# PulseRain_M10.net
KiCad netlist of a schematic drawn in EAGLE
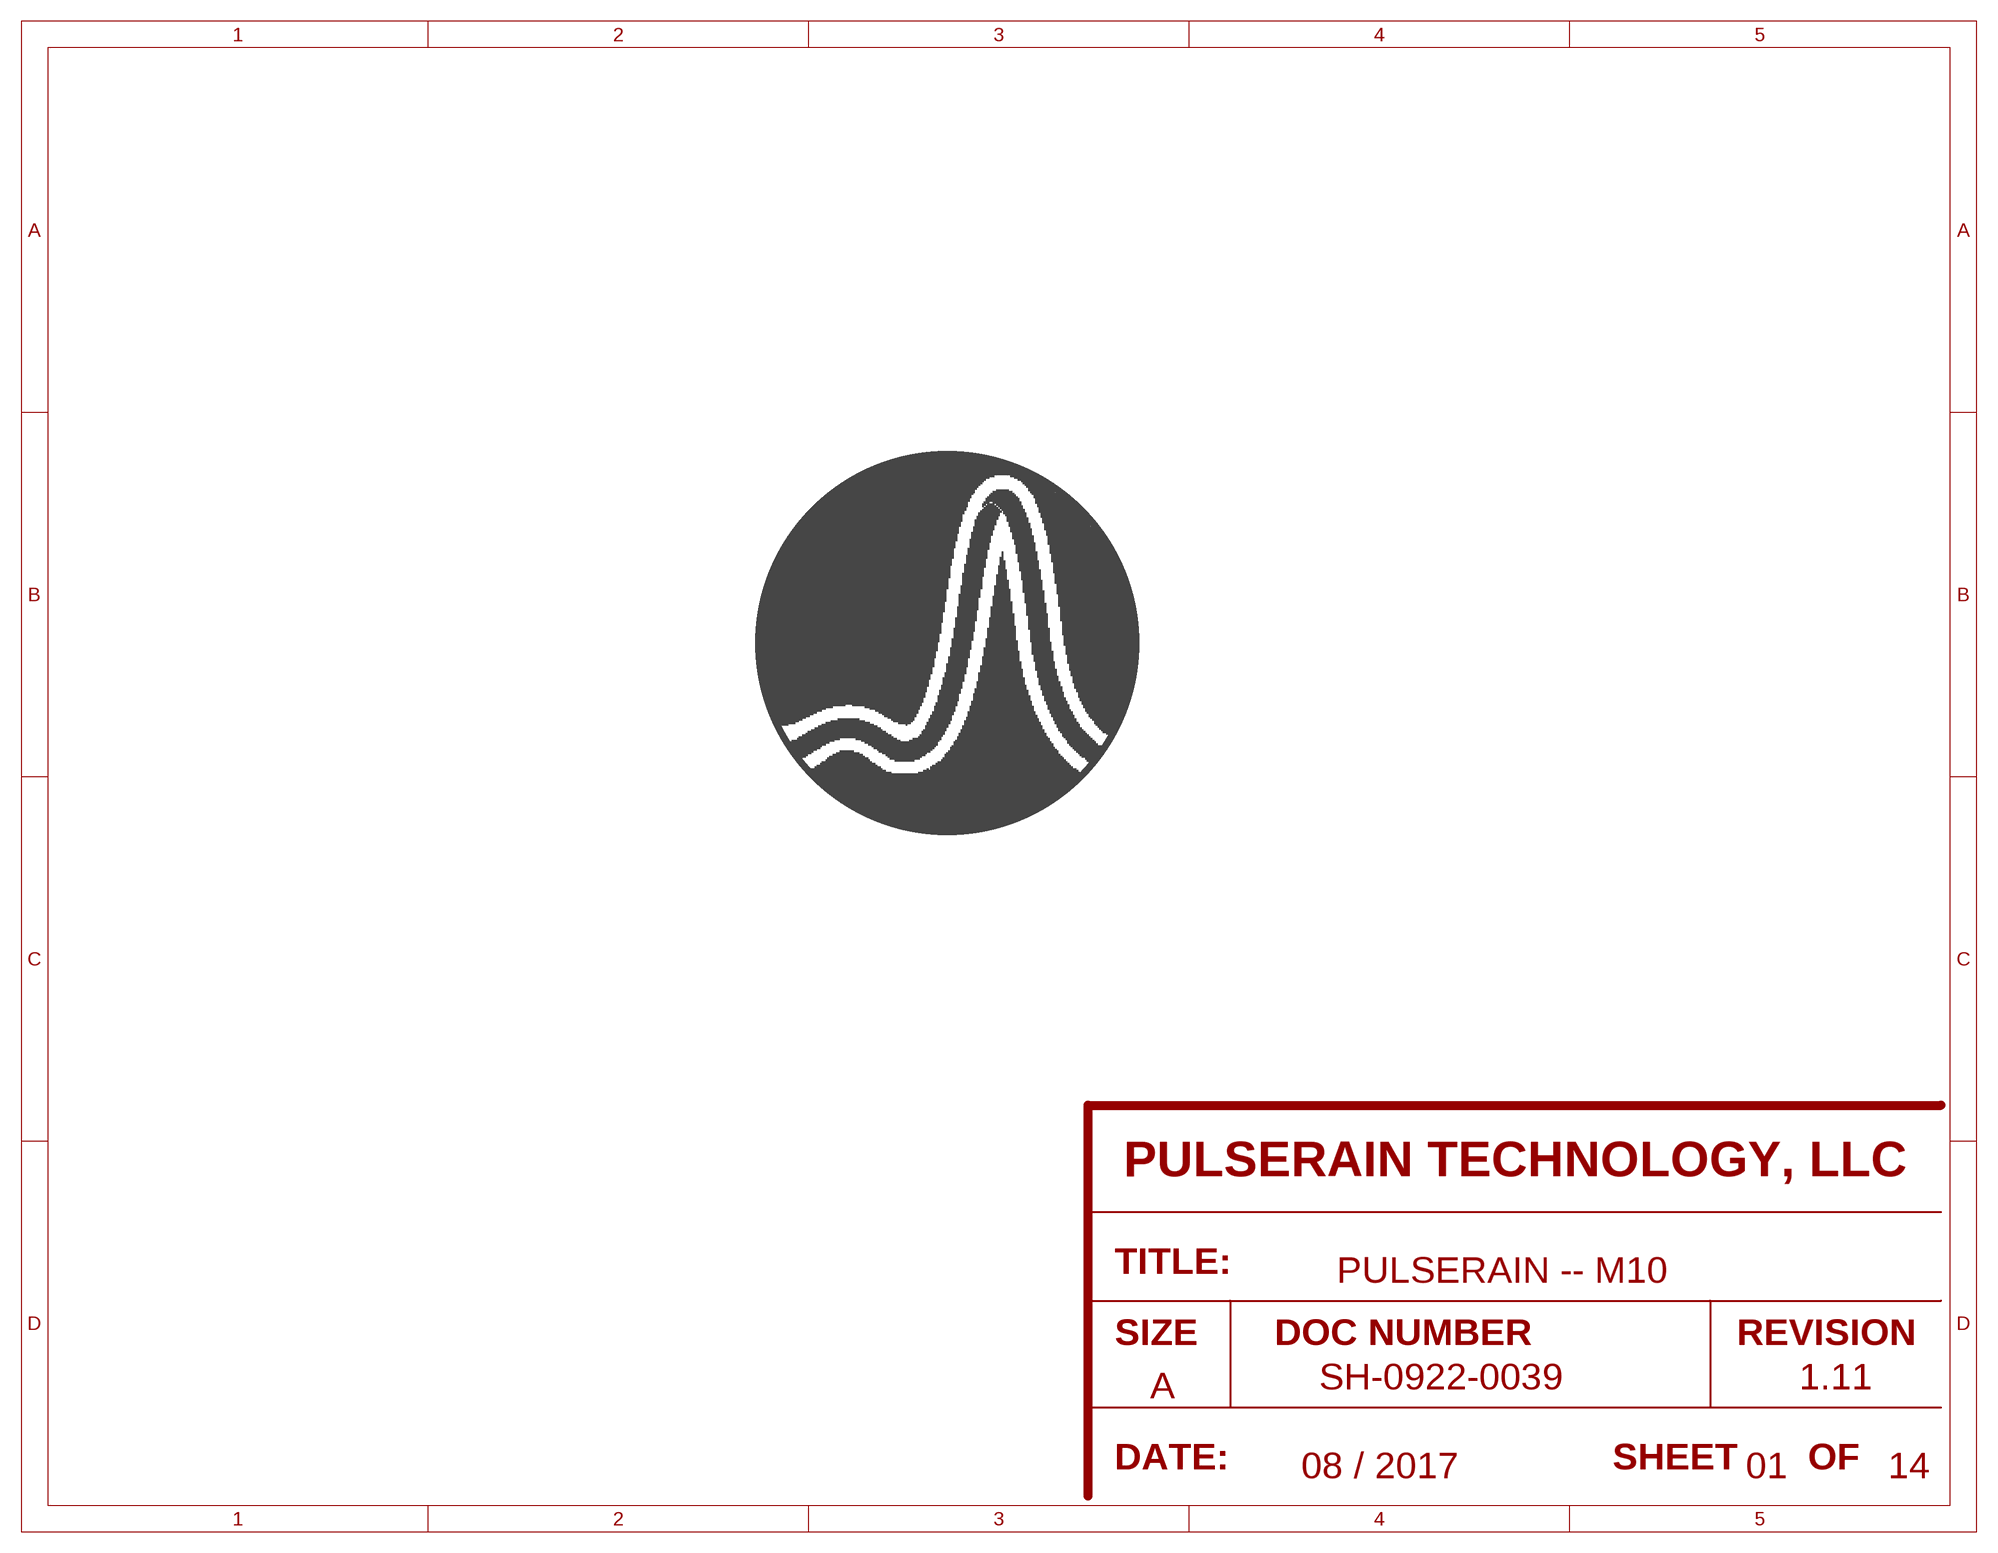
[diagram p0: schematic, sheet 1]
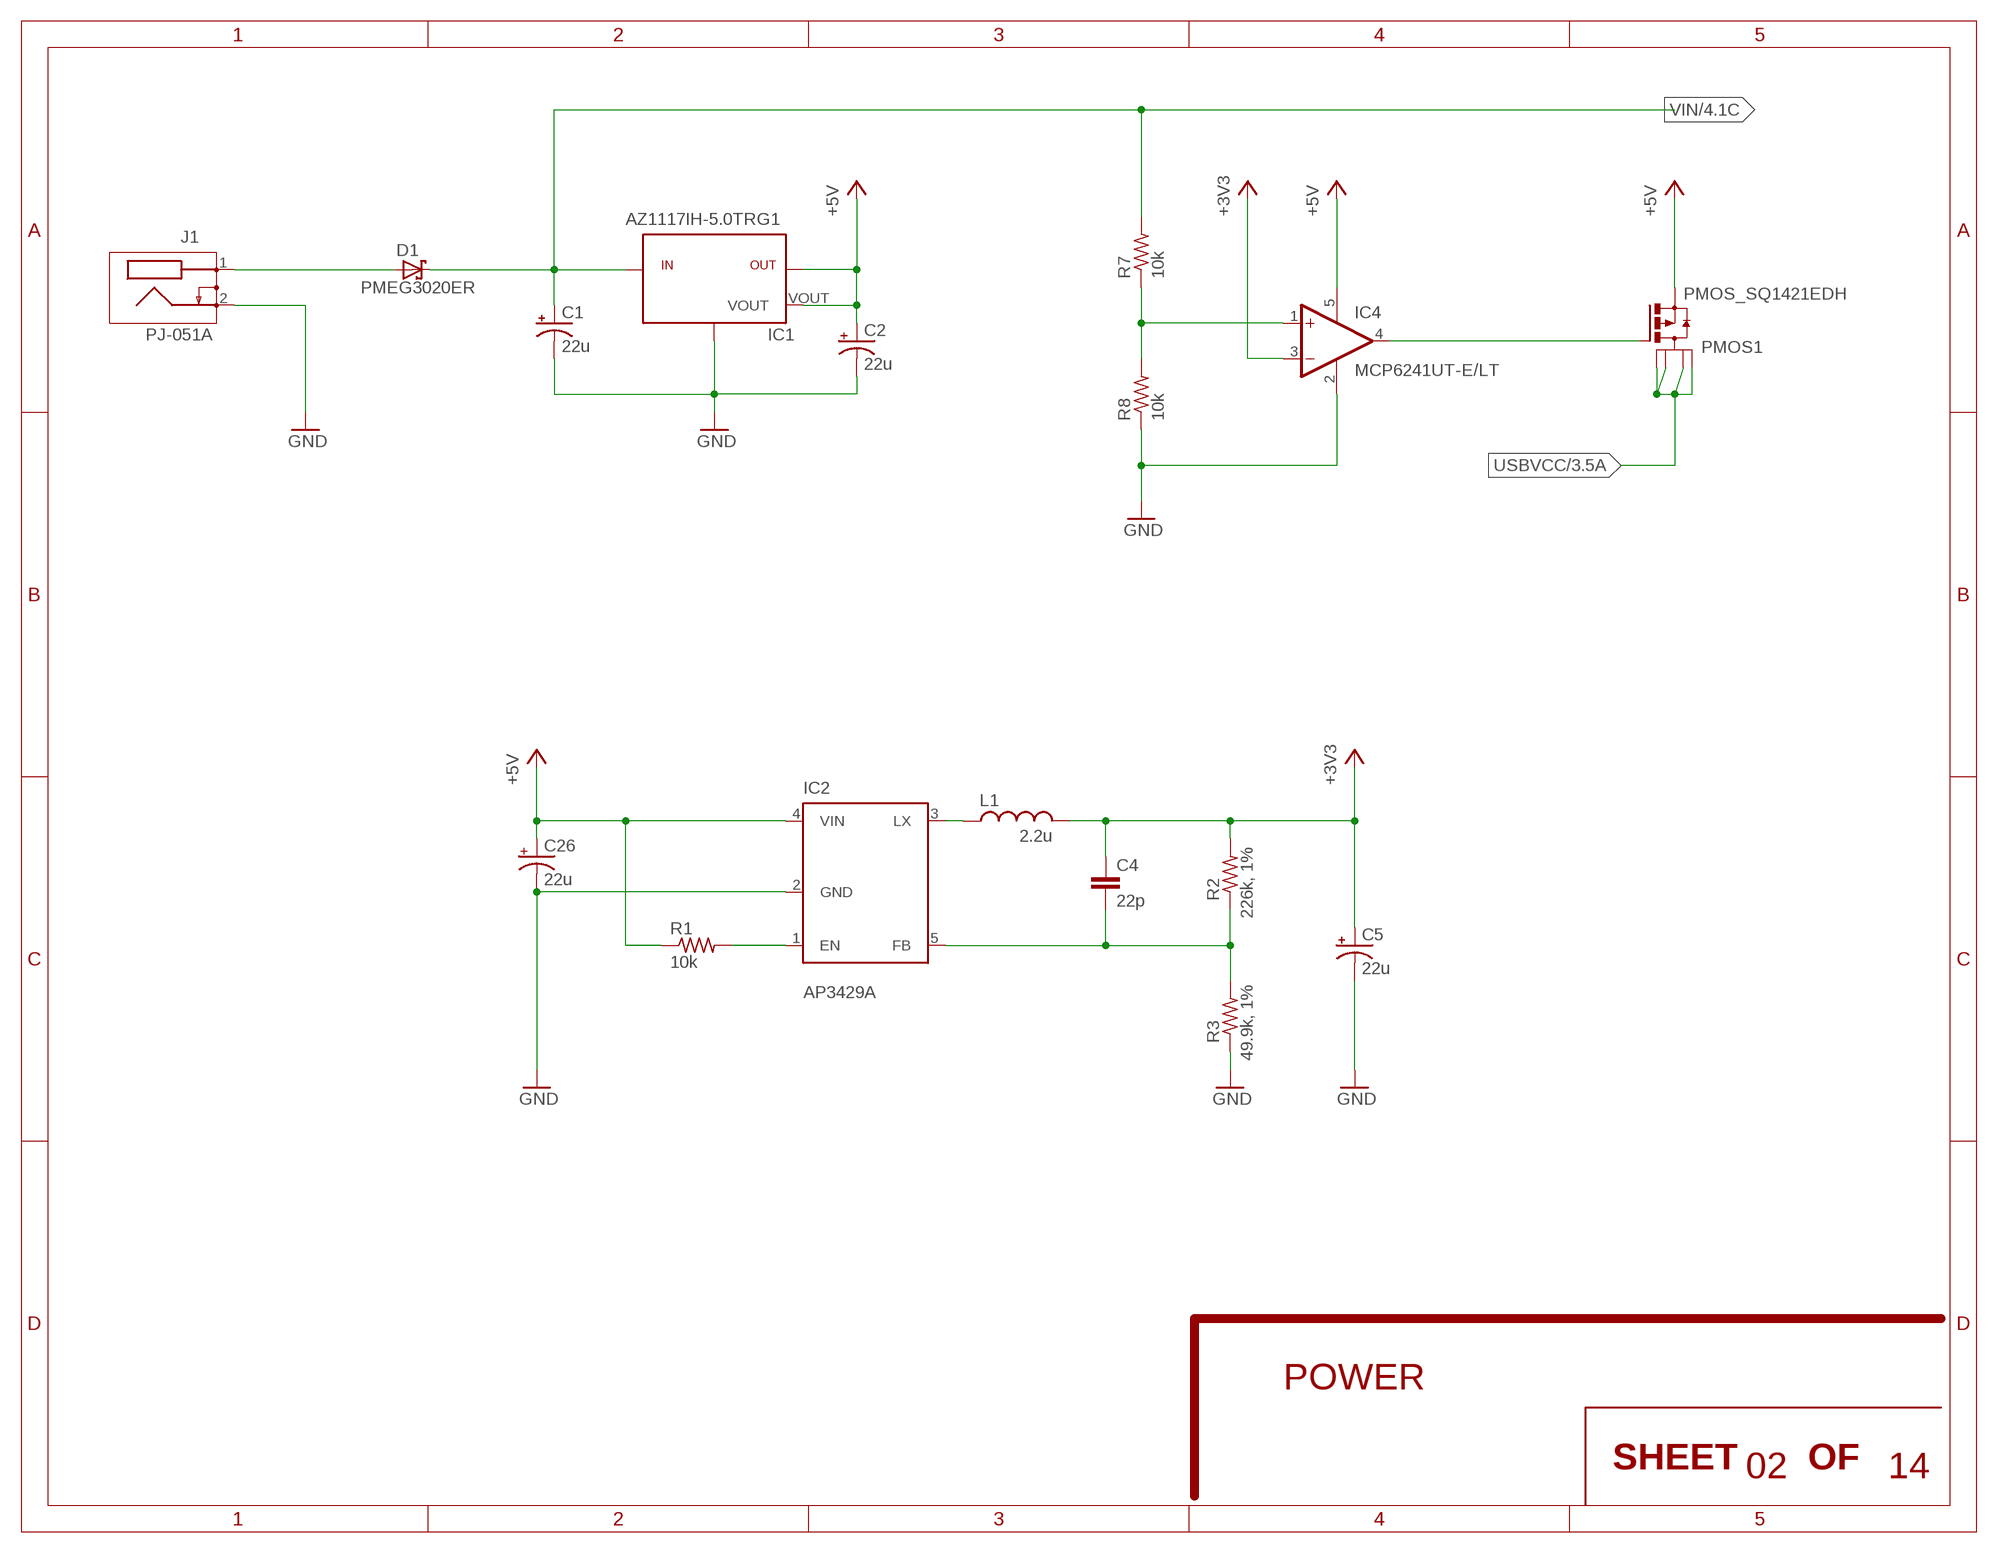
[diagram p1: schematic, sheet 2]
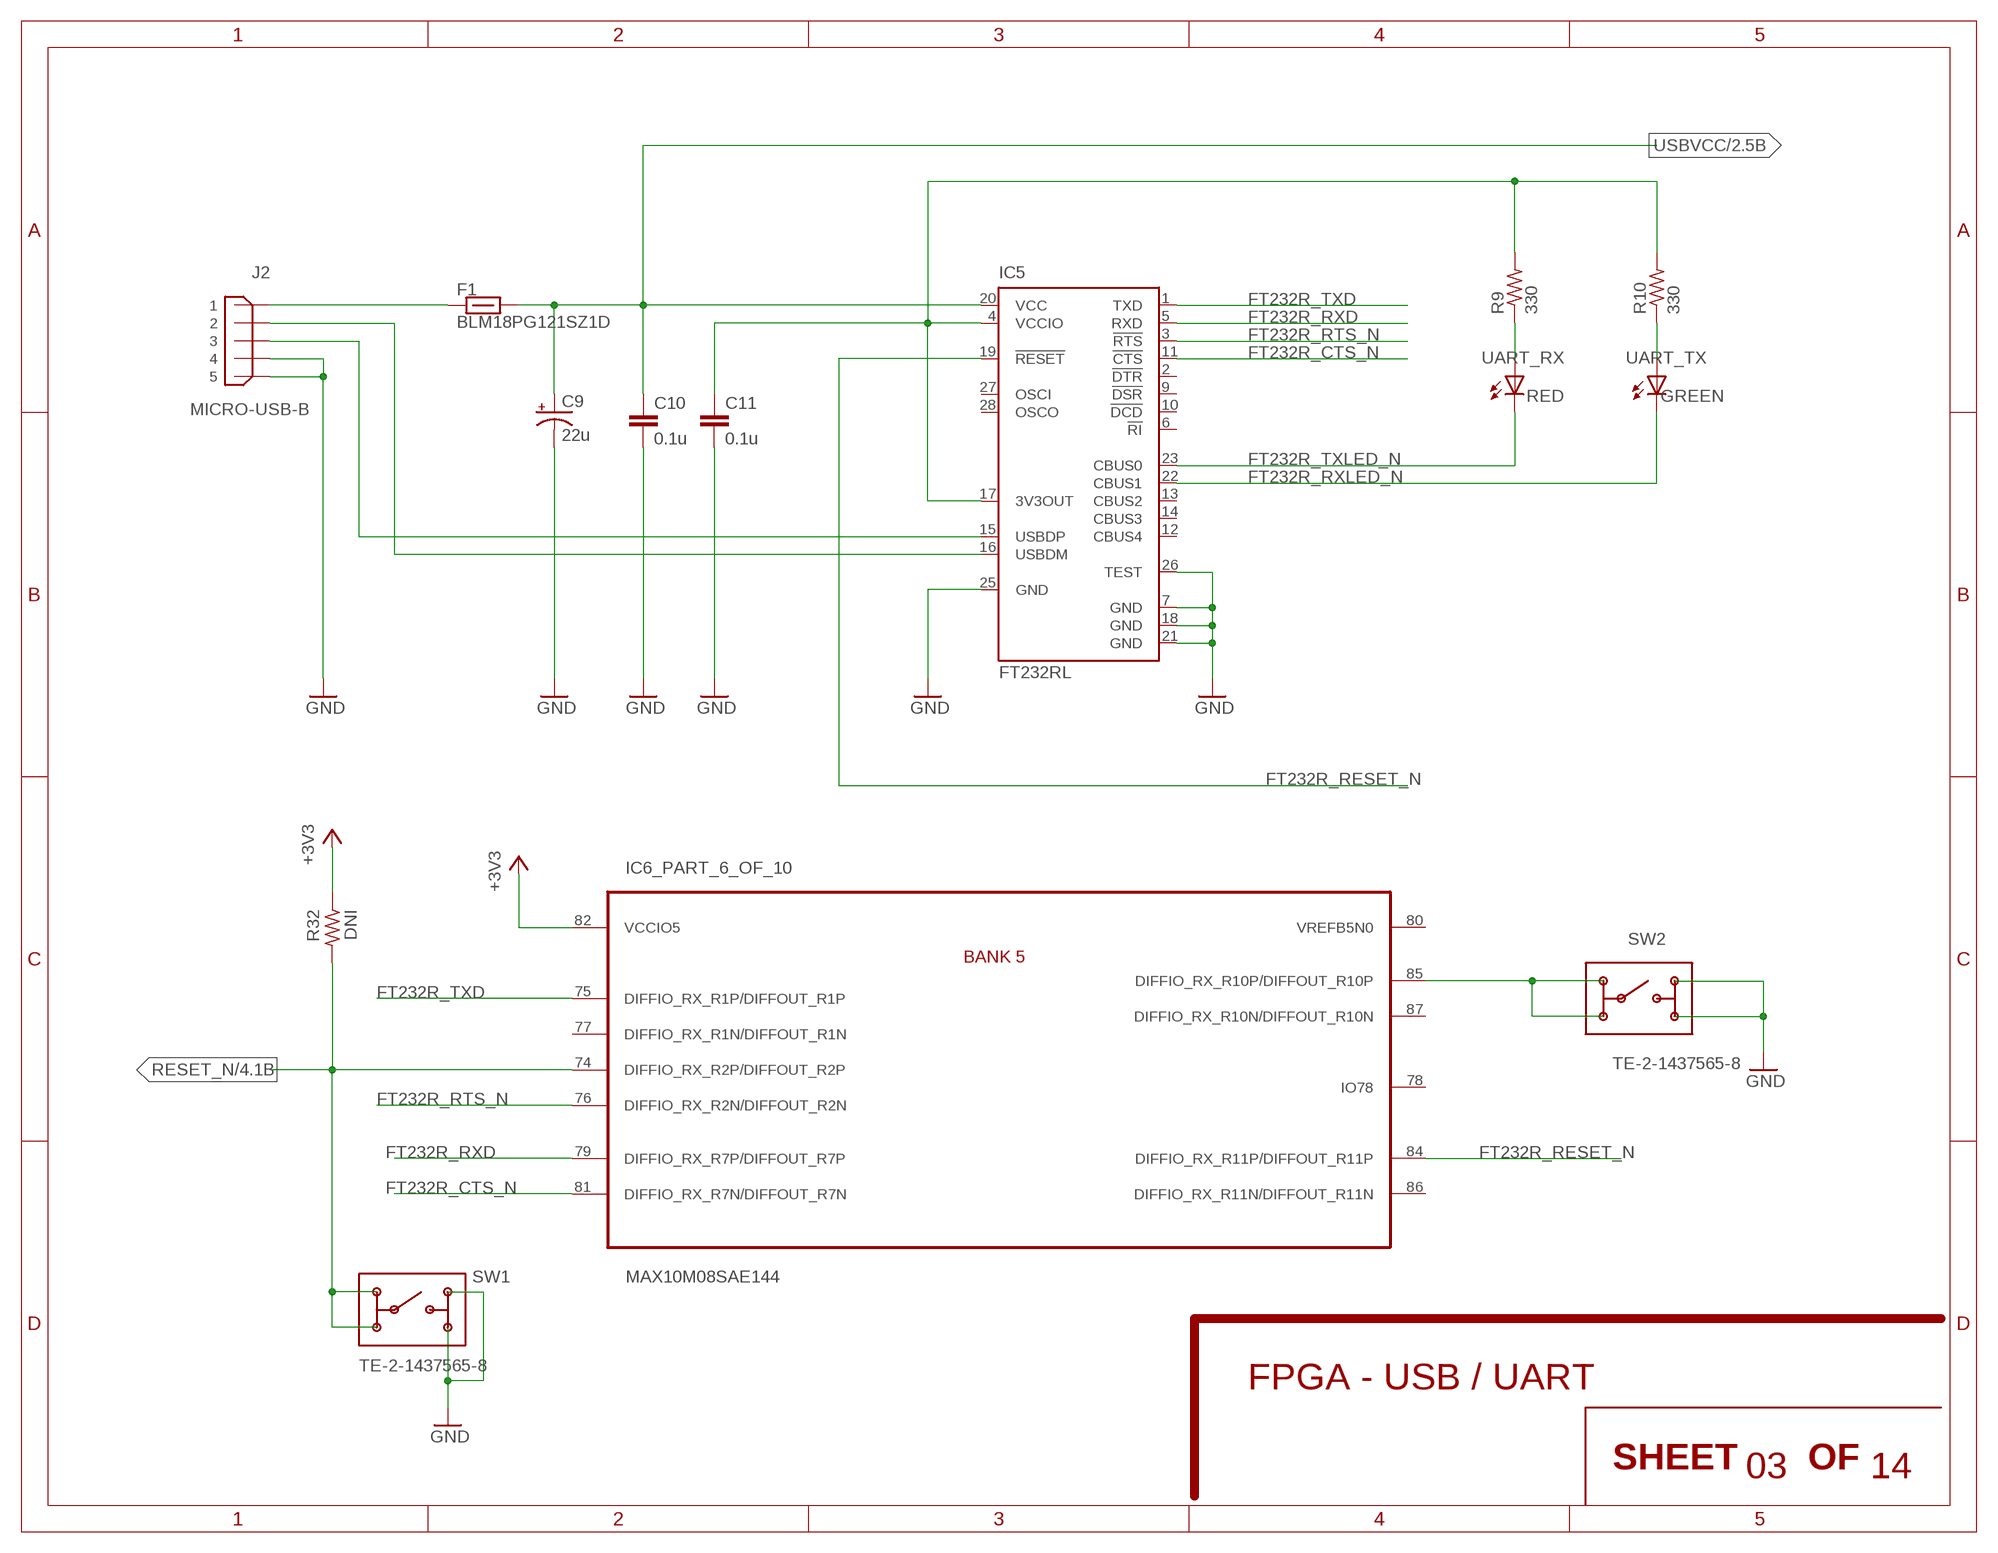
[diagram p2: schematic, sheet 3]
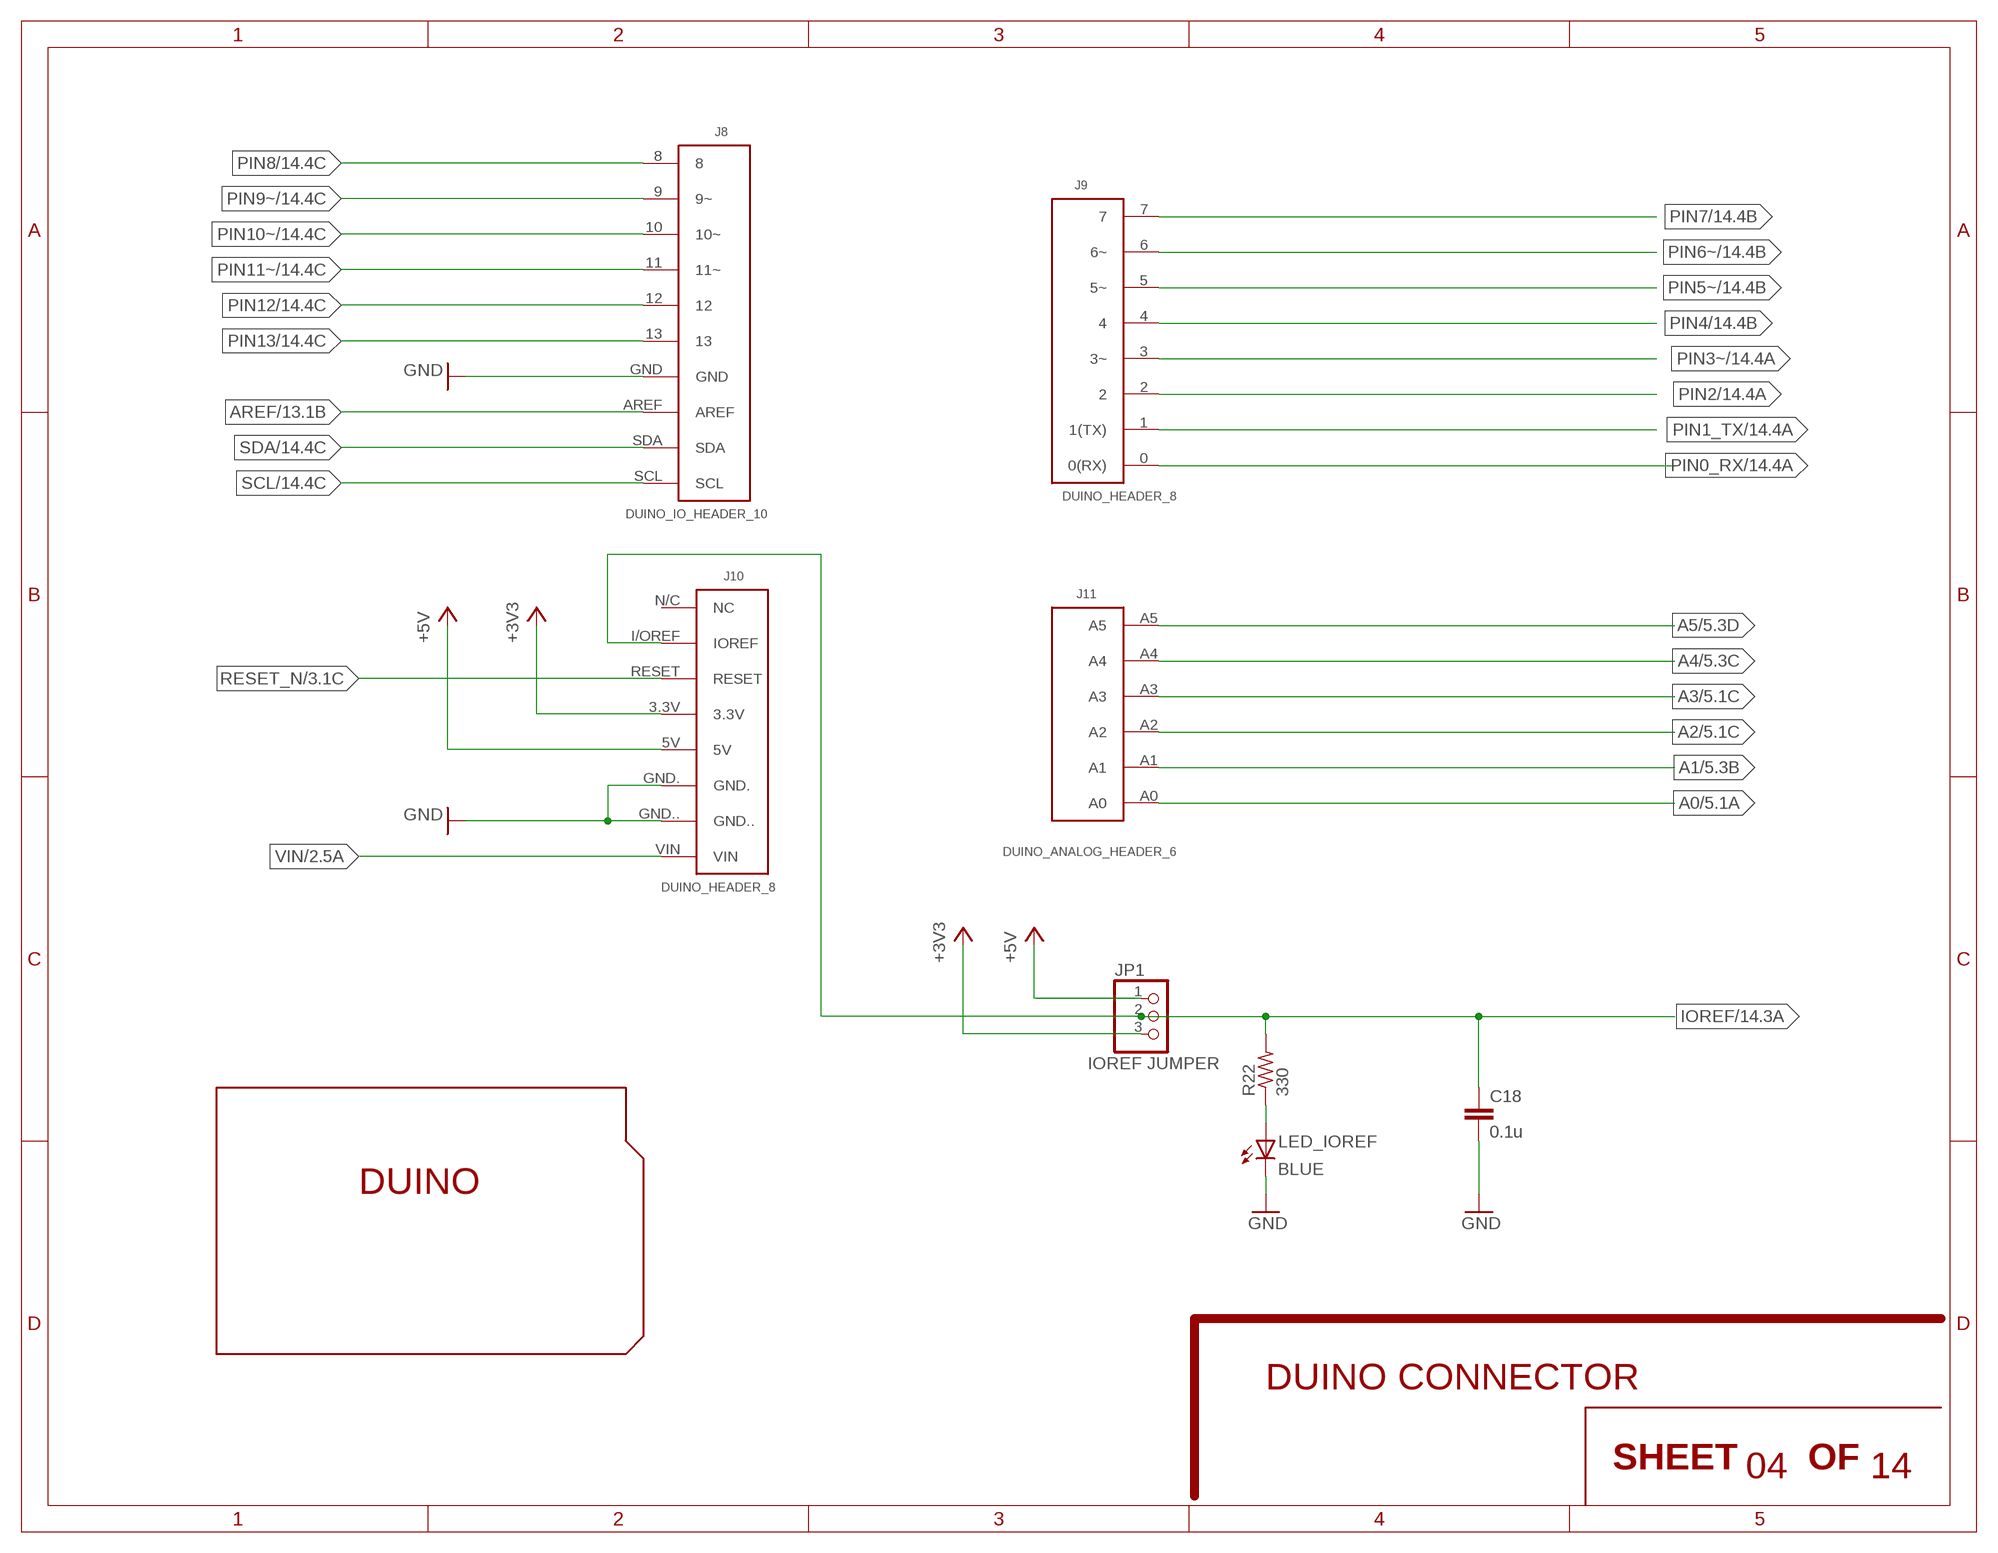
[diagram p3: schematic, sheet 4]
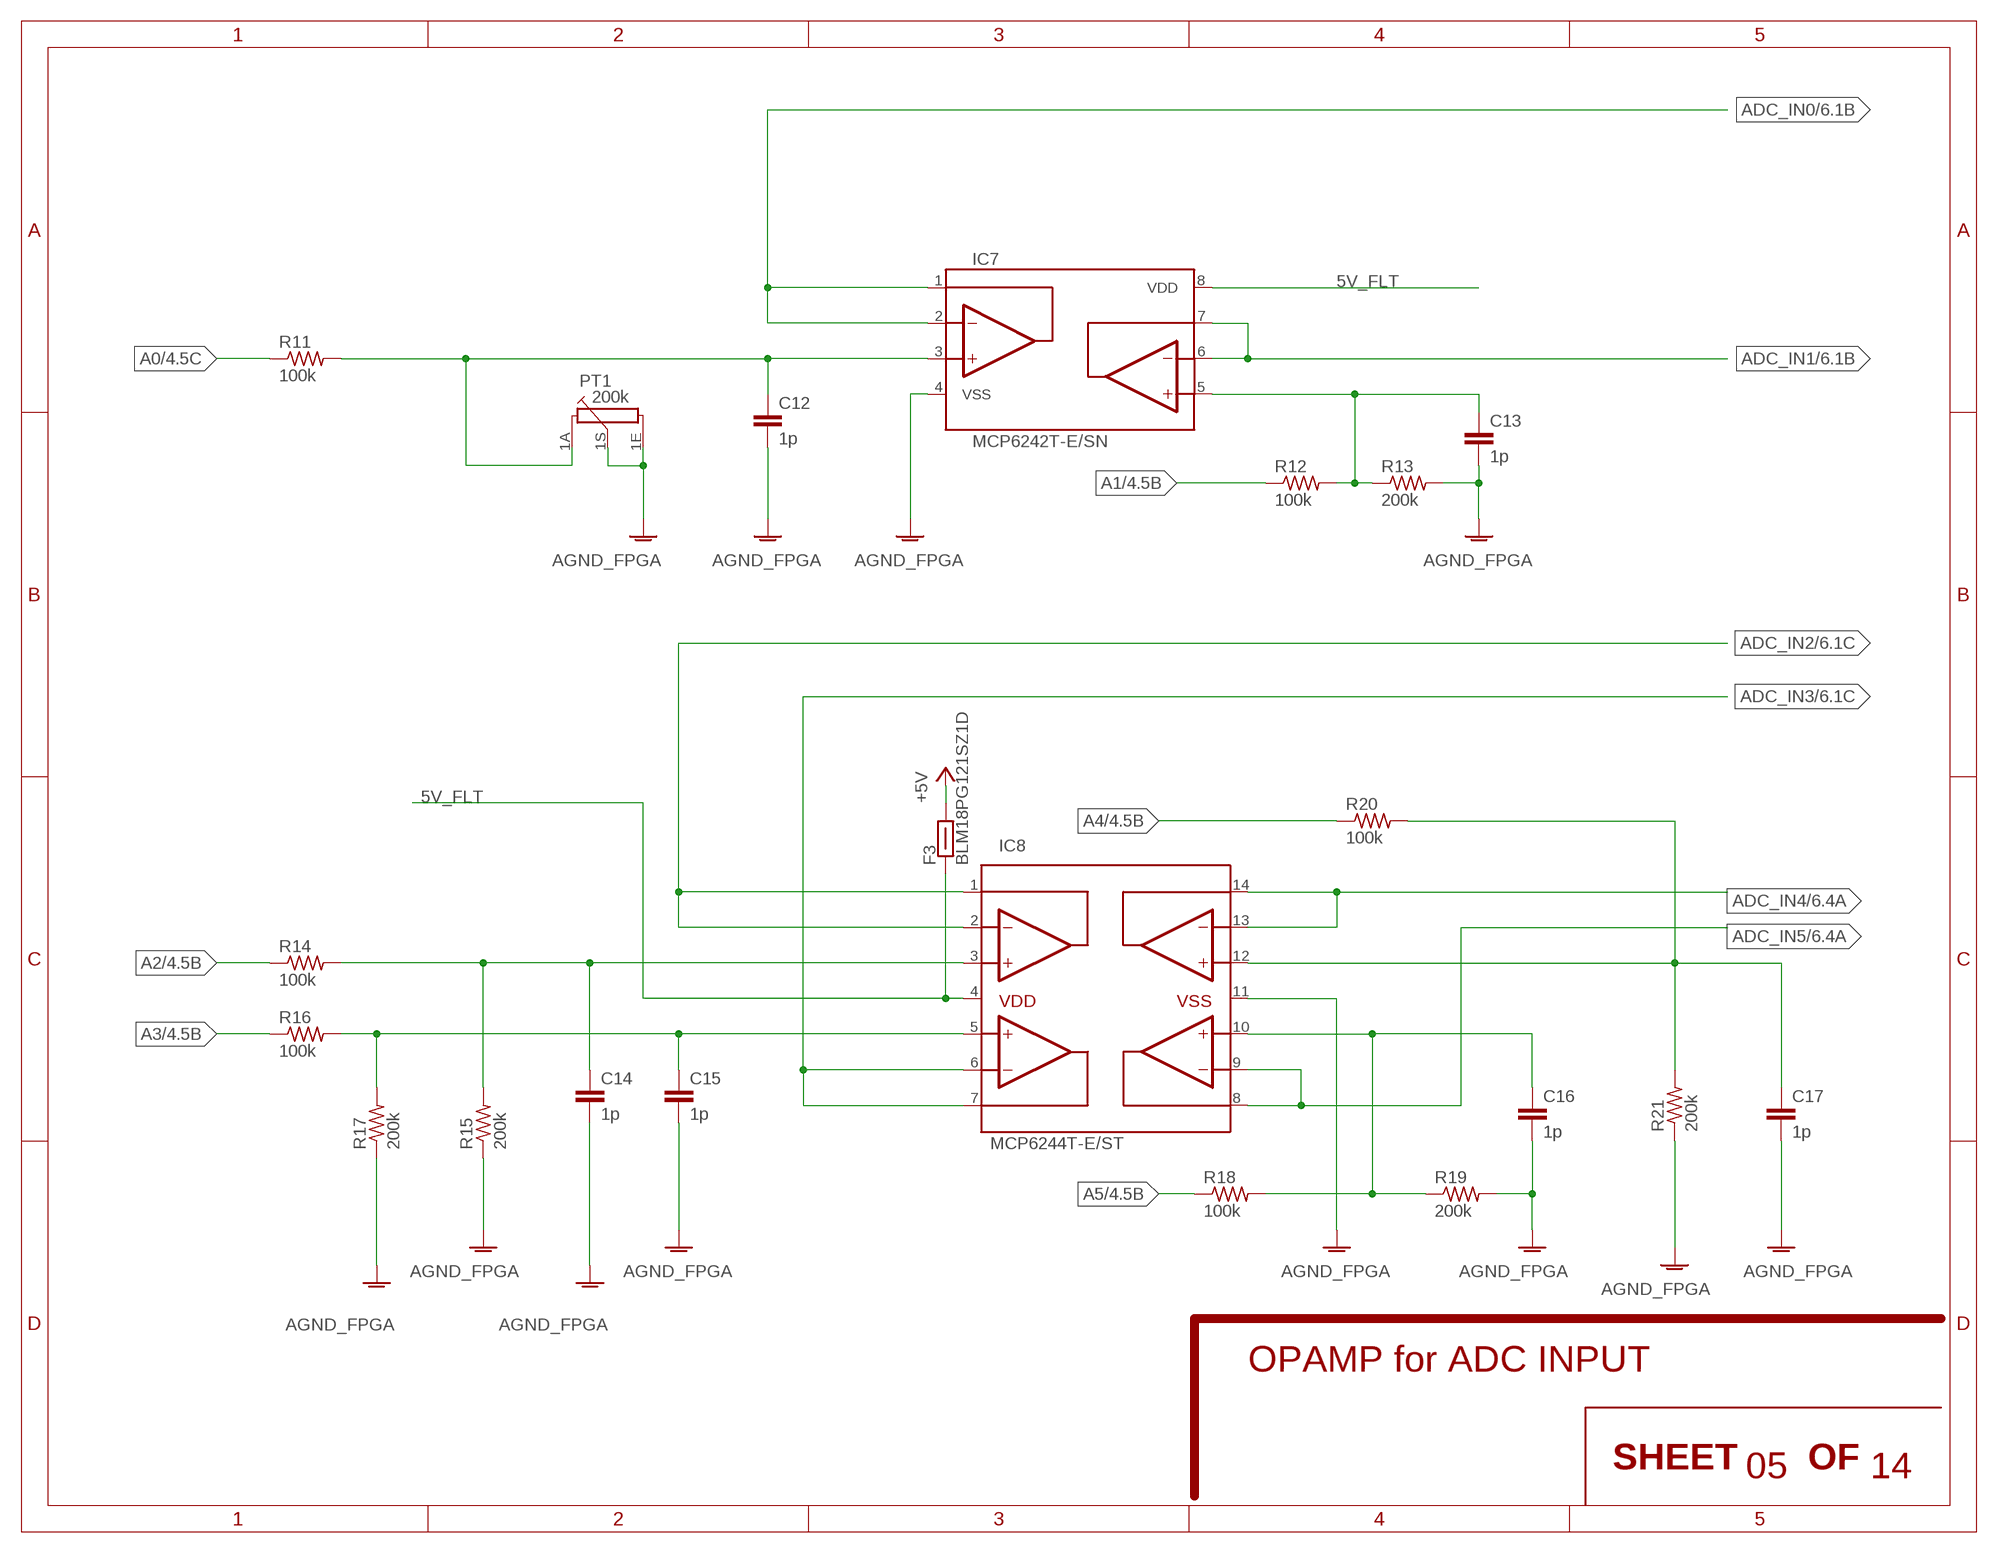
[diagram p4: schematic, sheet 5]
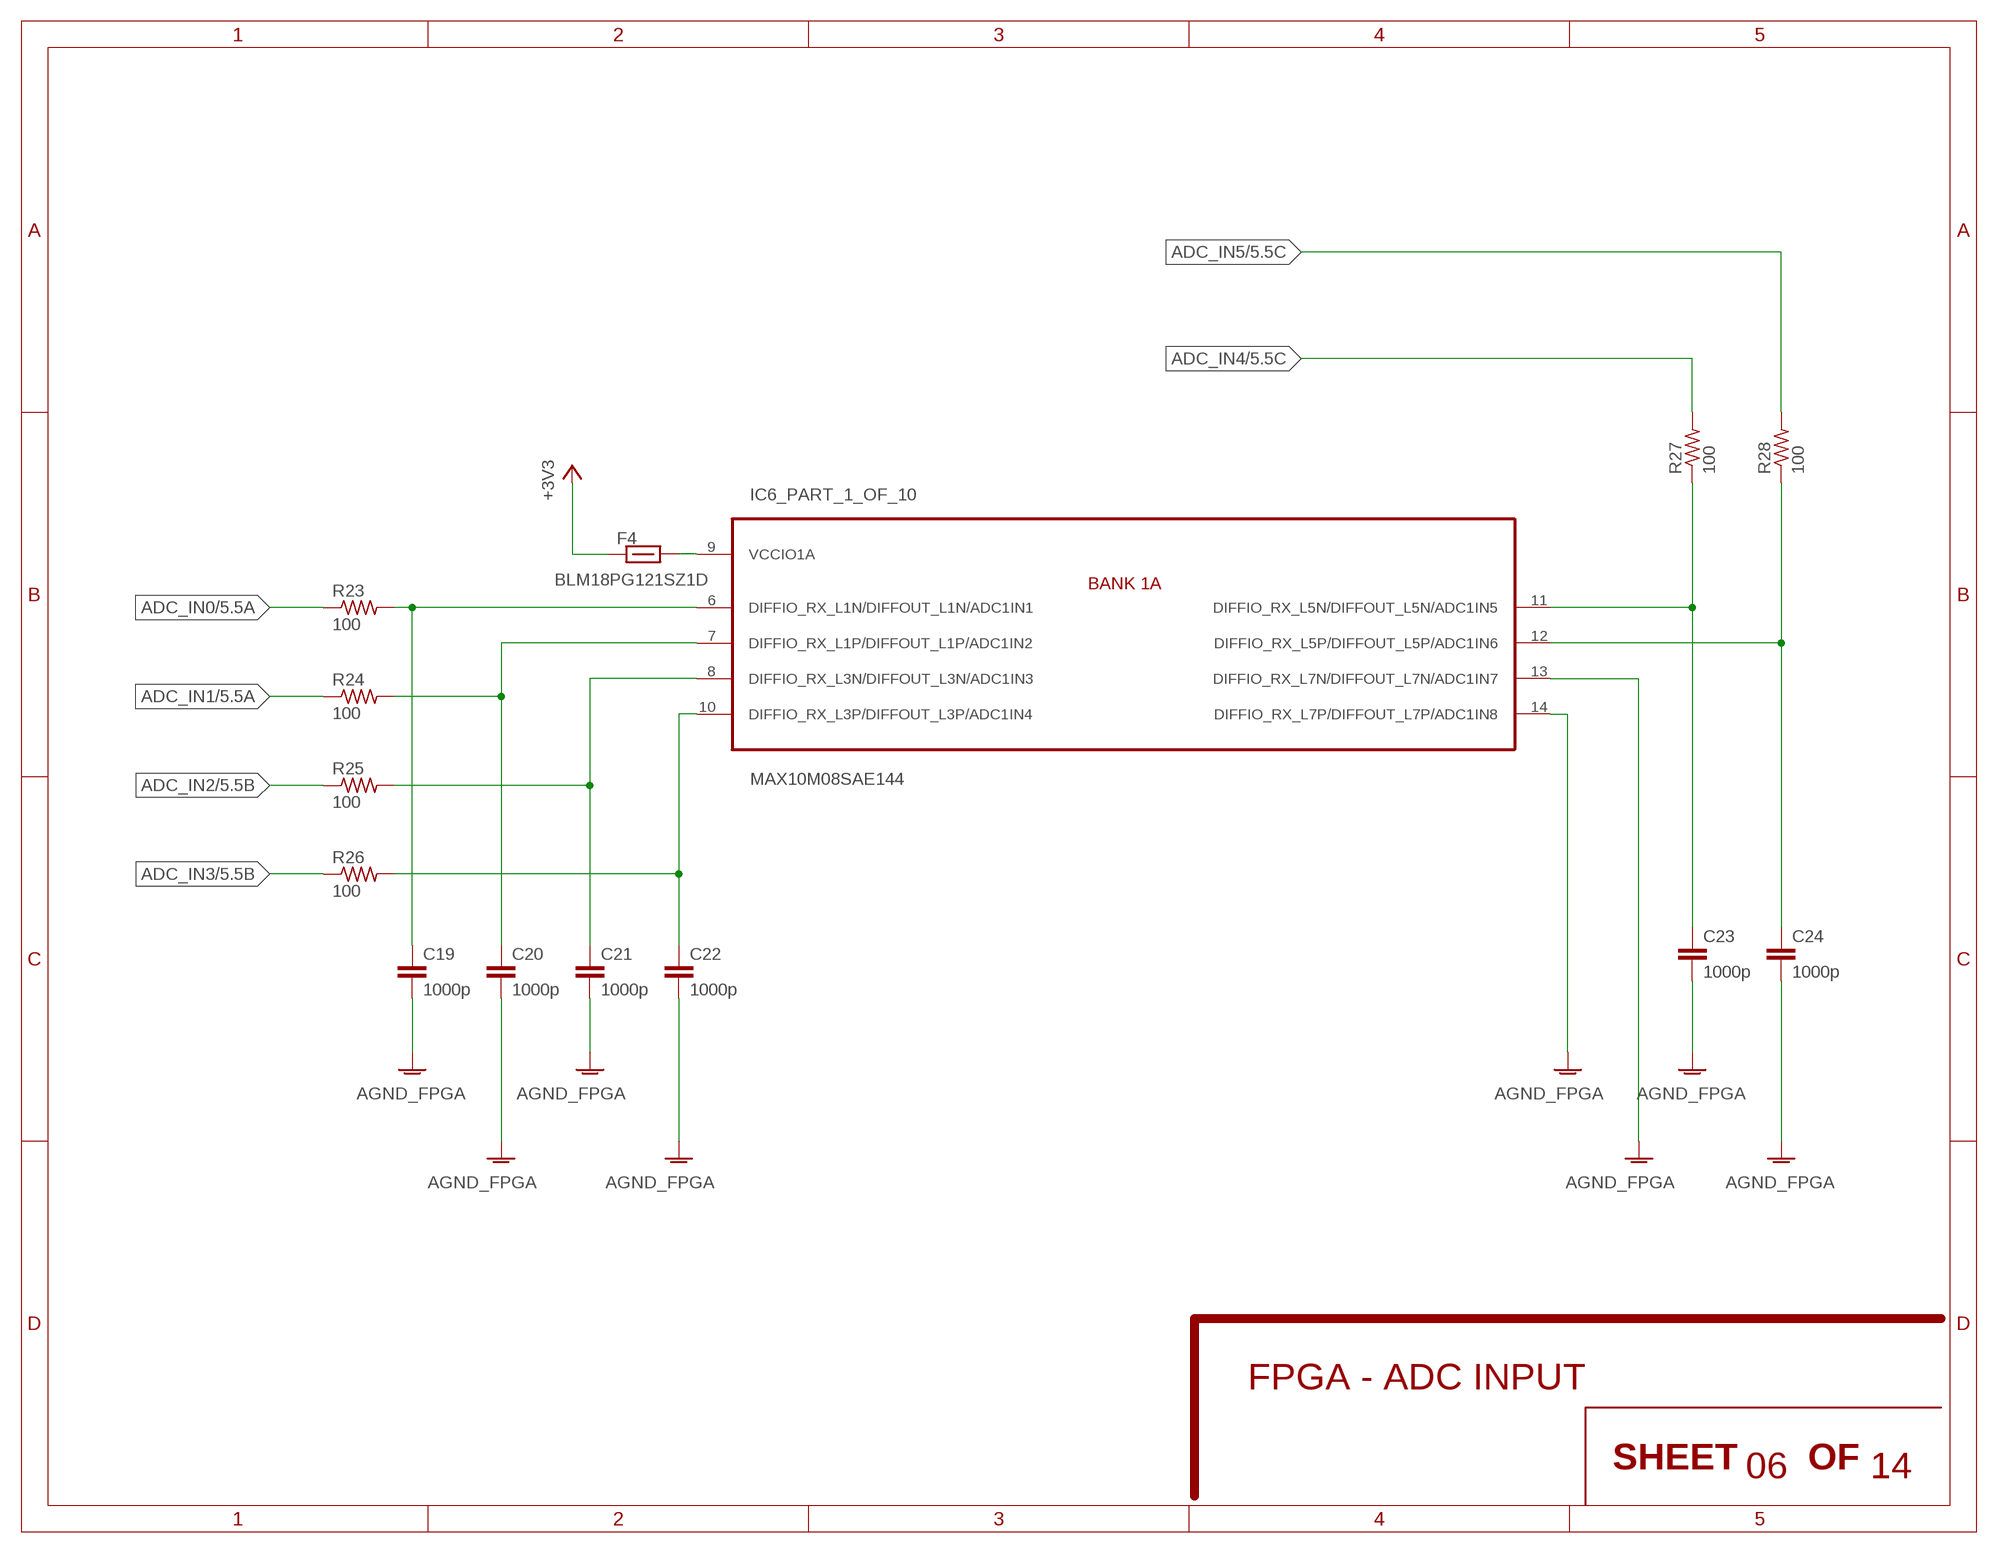
[diagram p5: schematic, sheet 6]
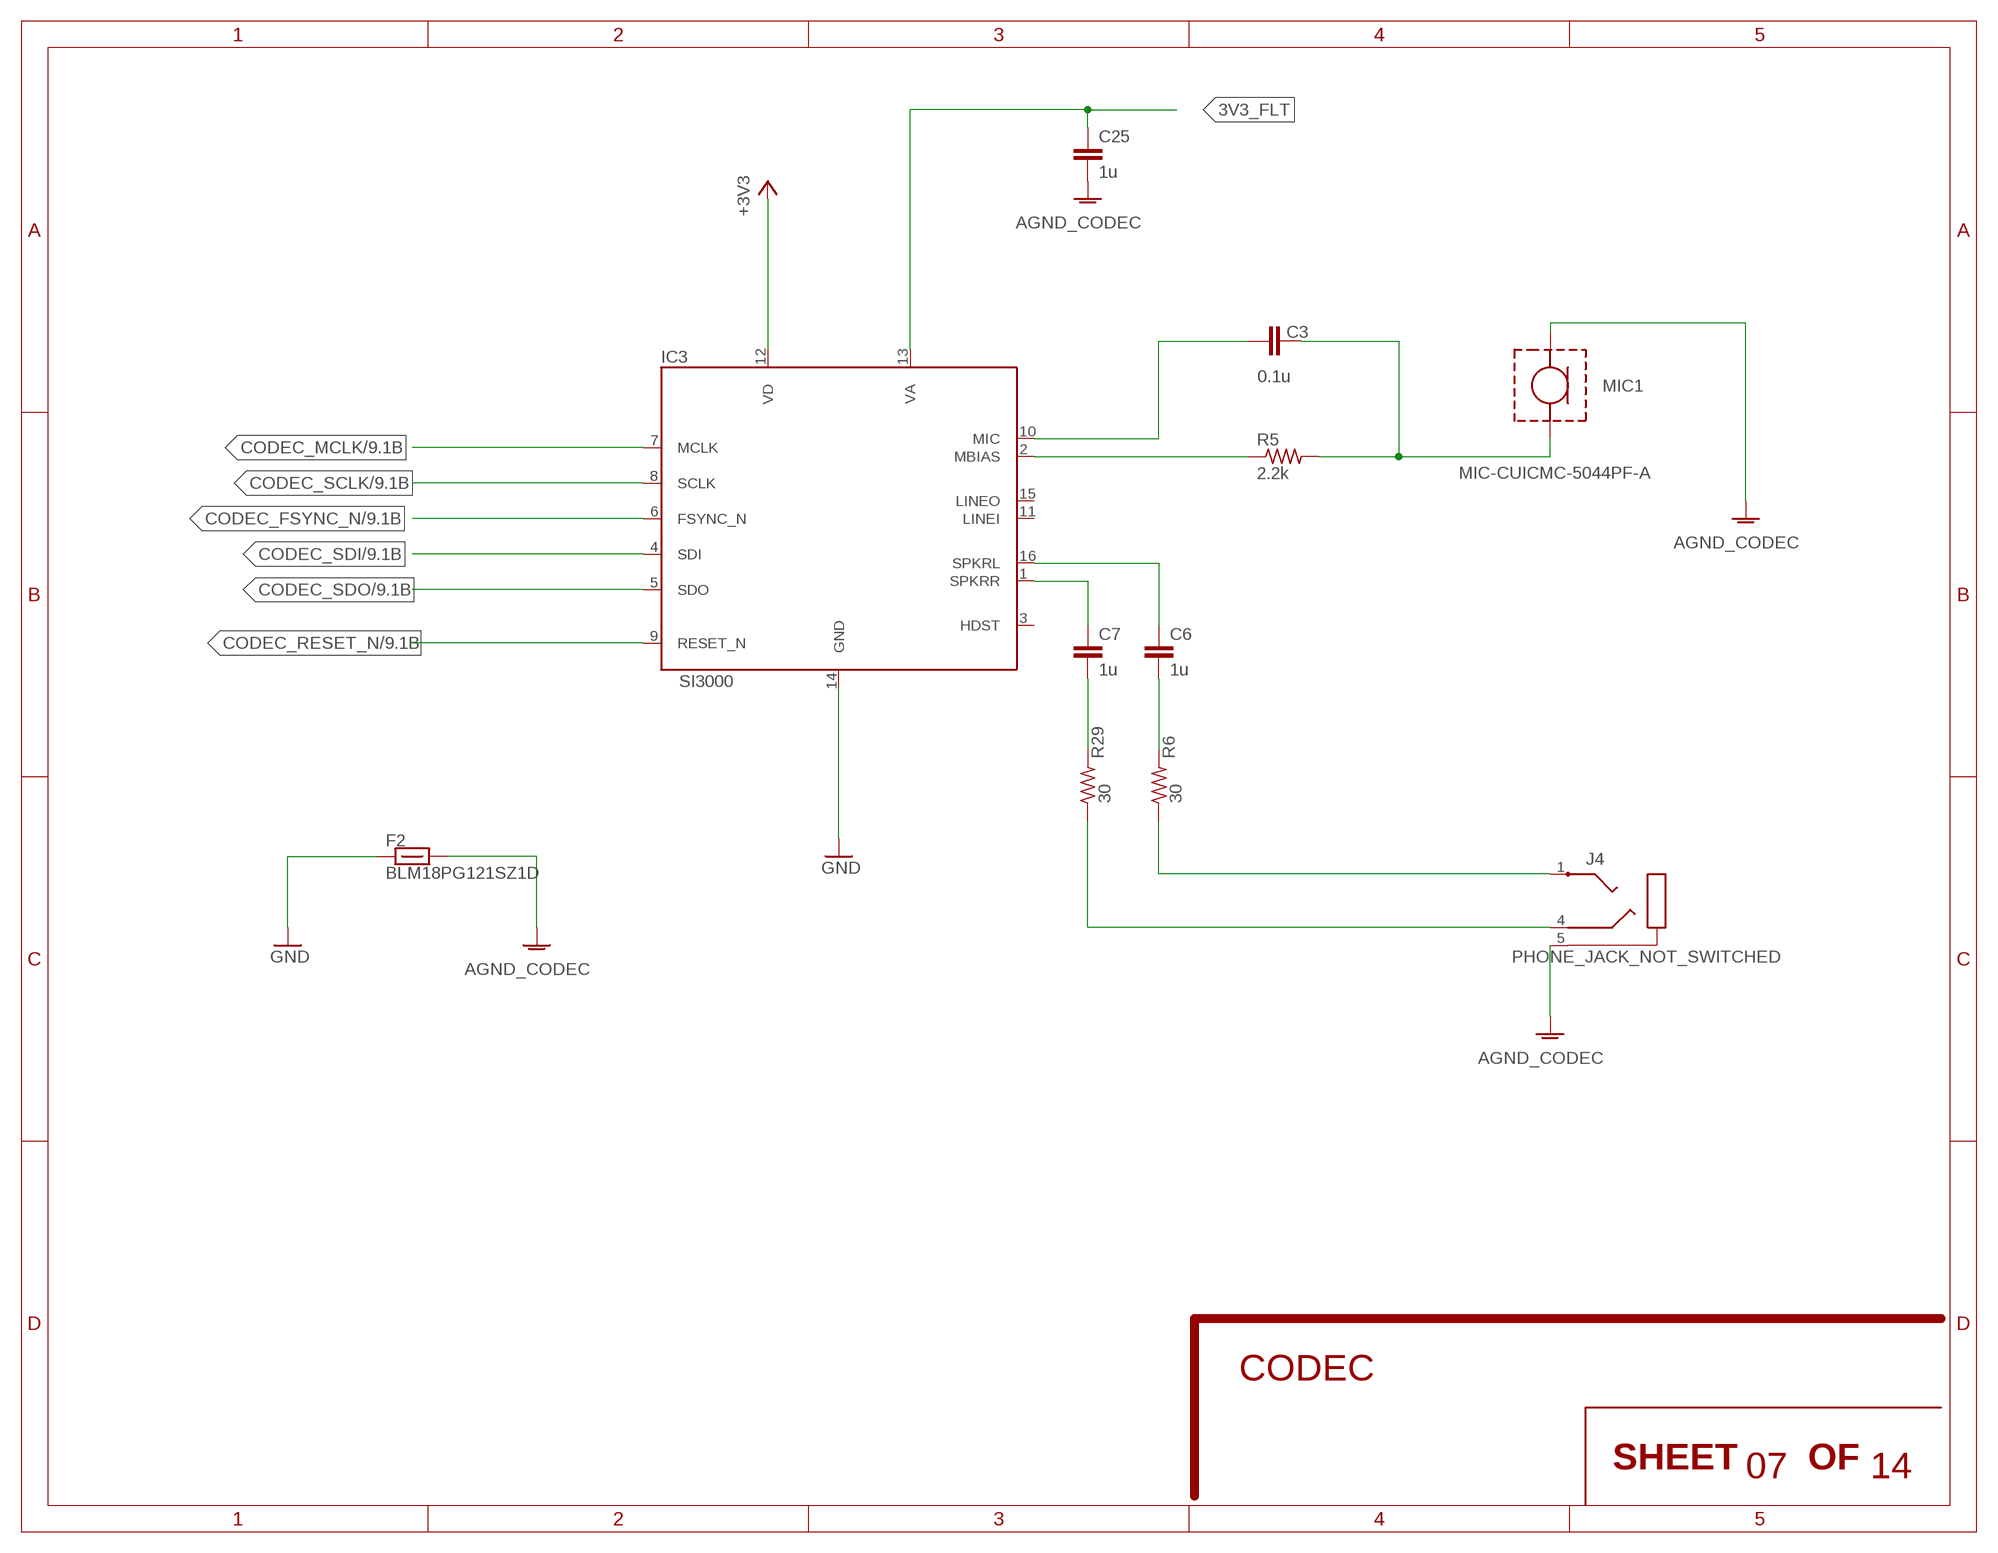
[diagram p6: schematic, sheet 7]
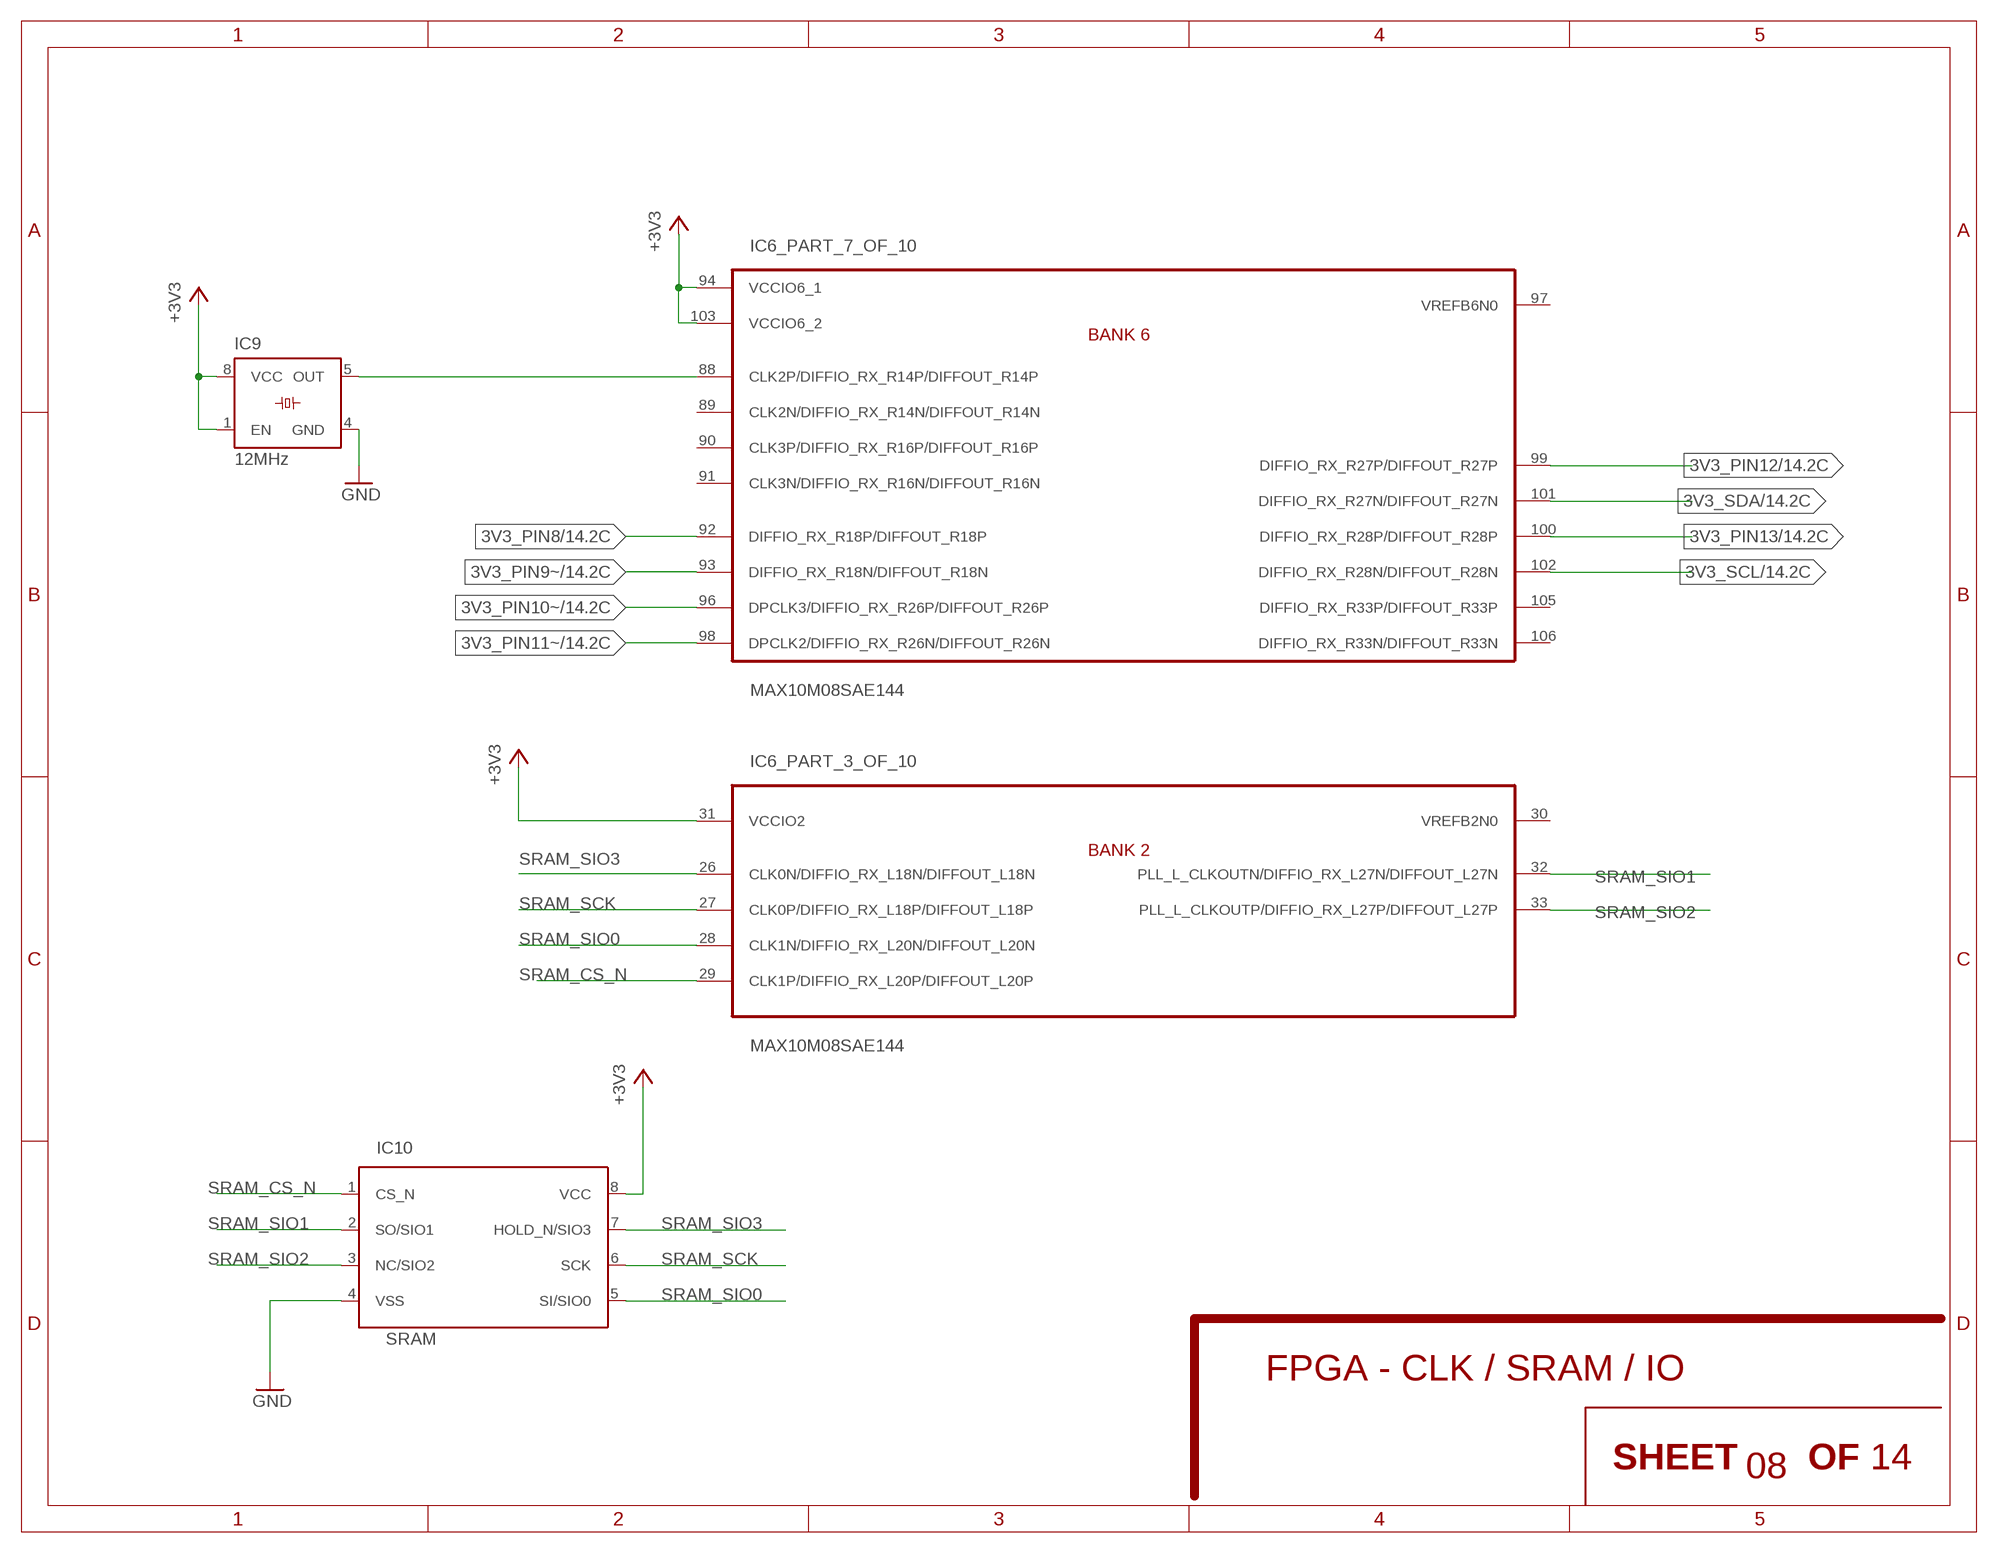
[diagram p7: schematic, sheet 8]
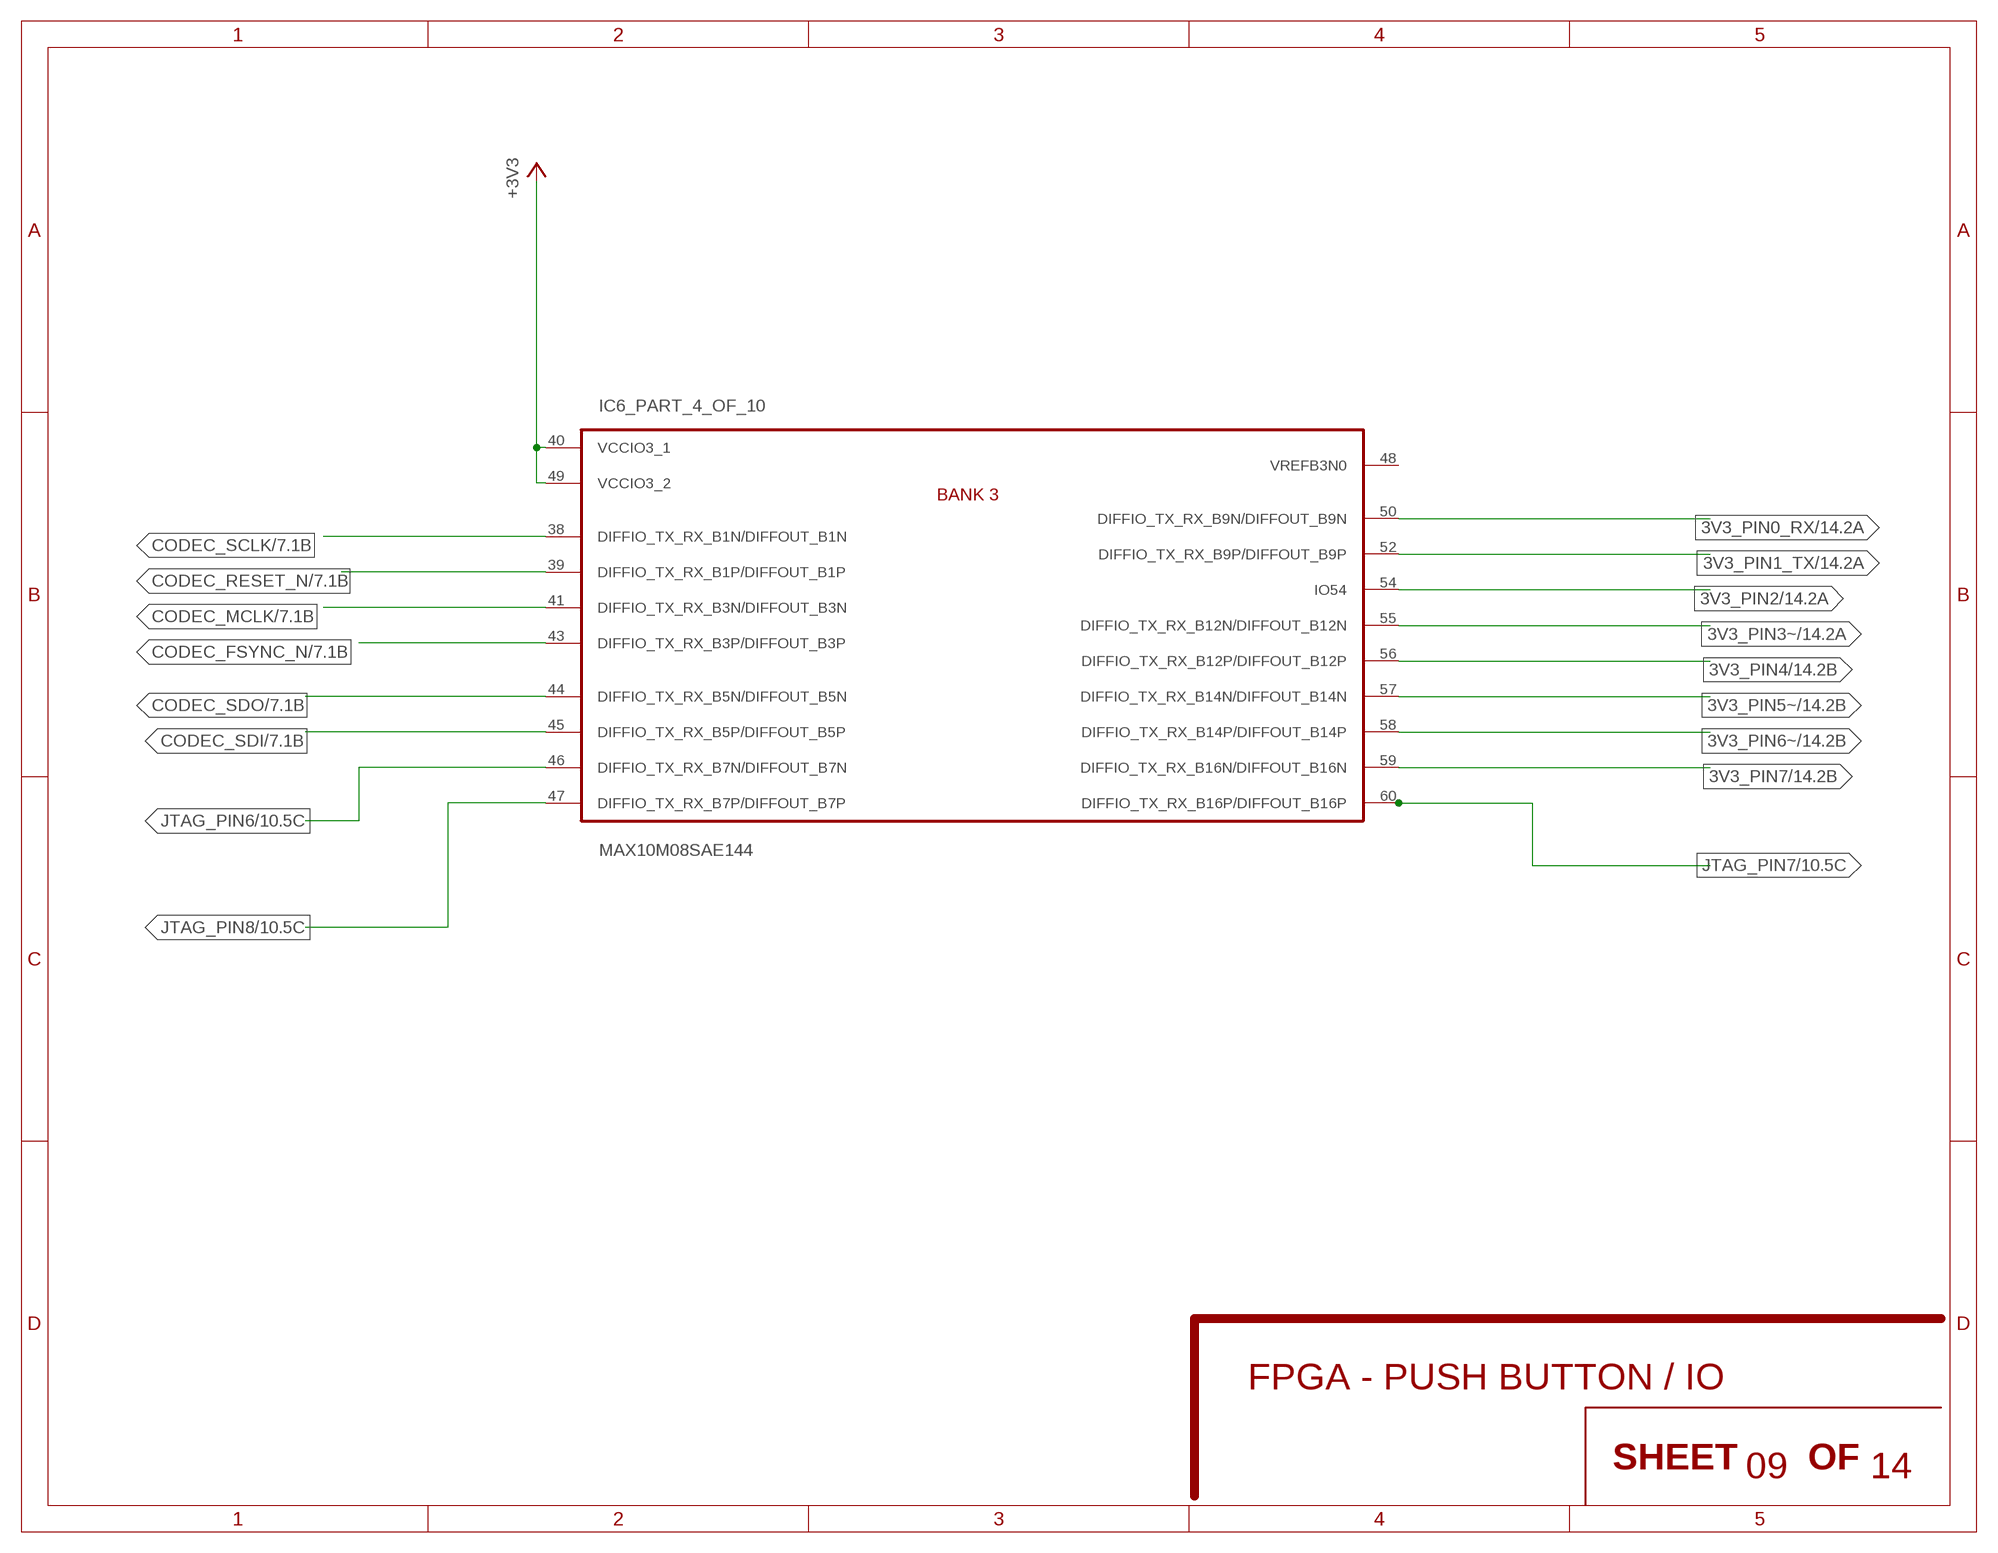
[diagram p8: schematic, sheet 9]
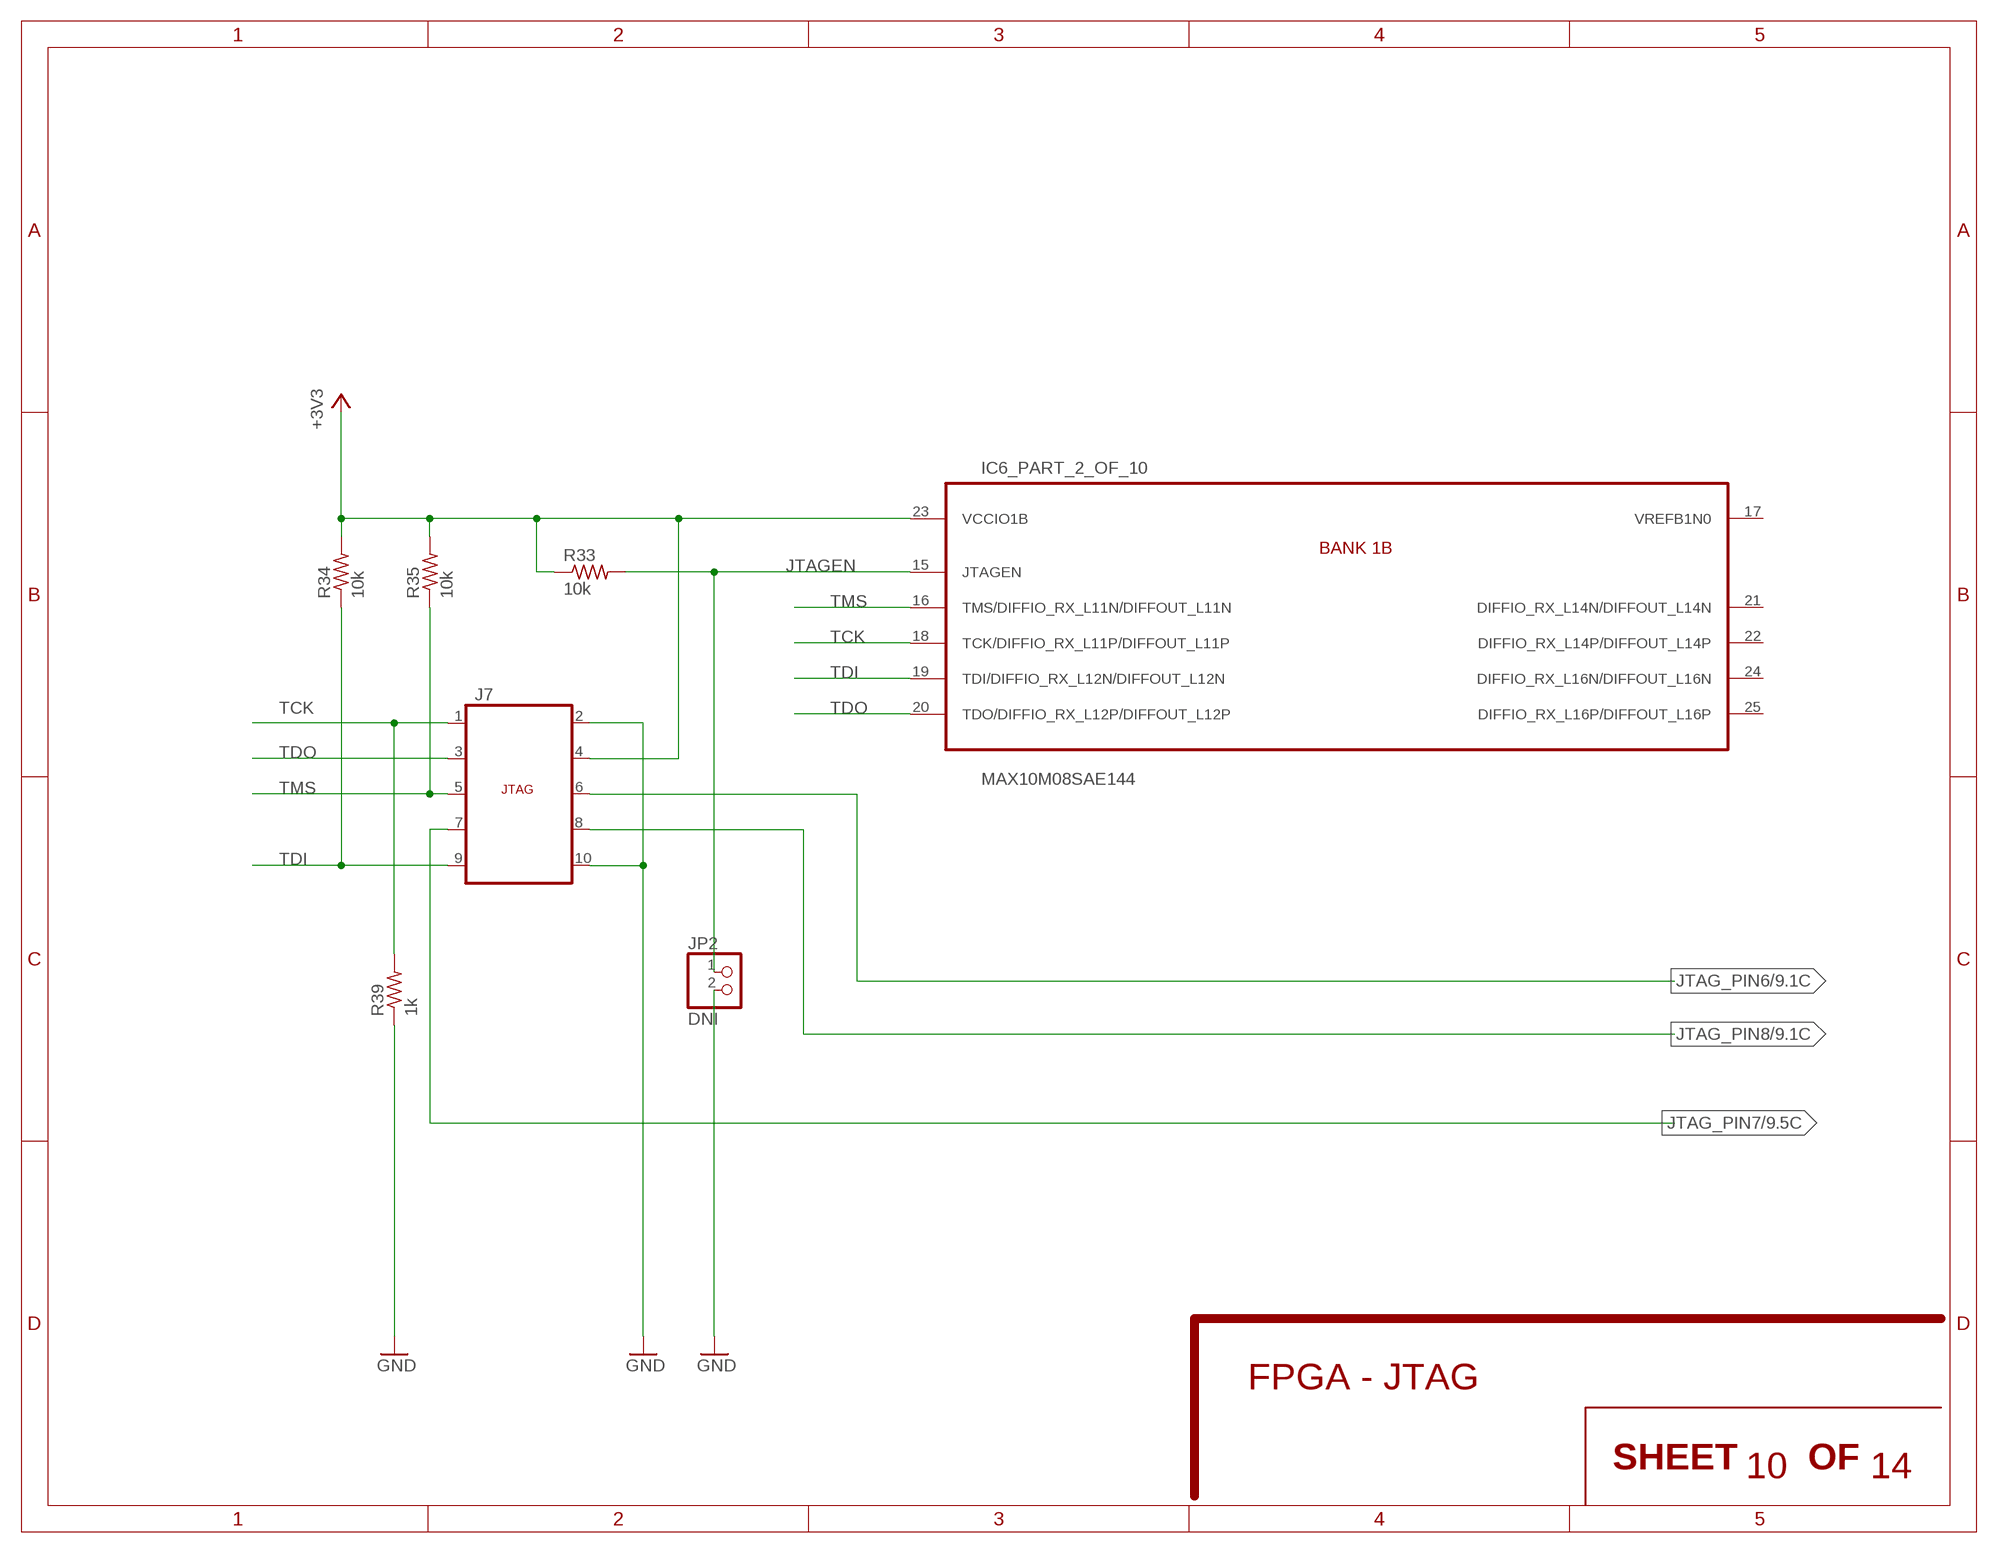
[diagram p9: schematic, sheet 10]
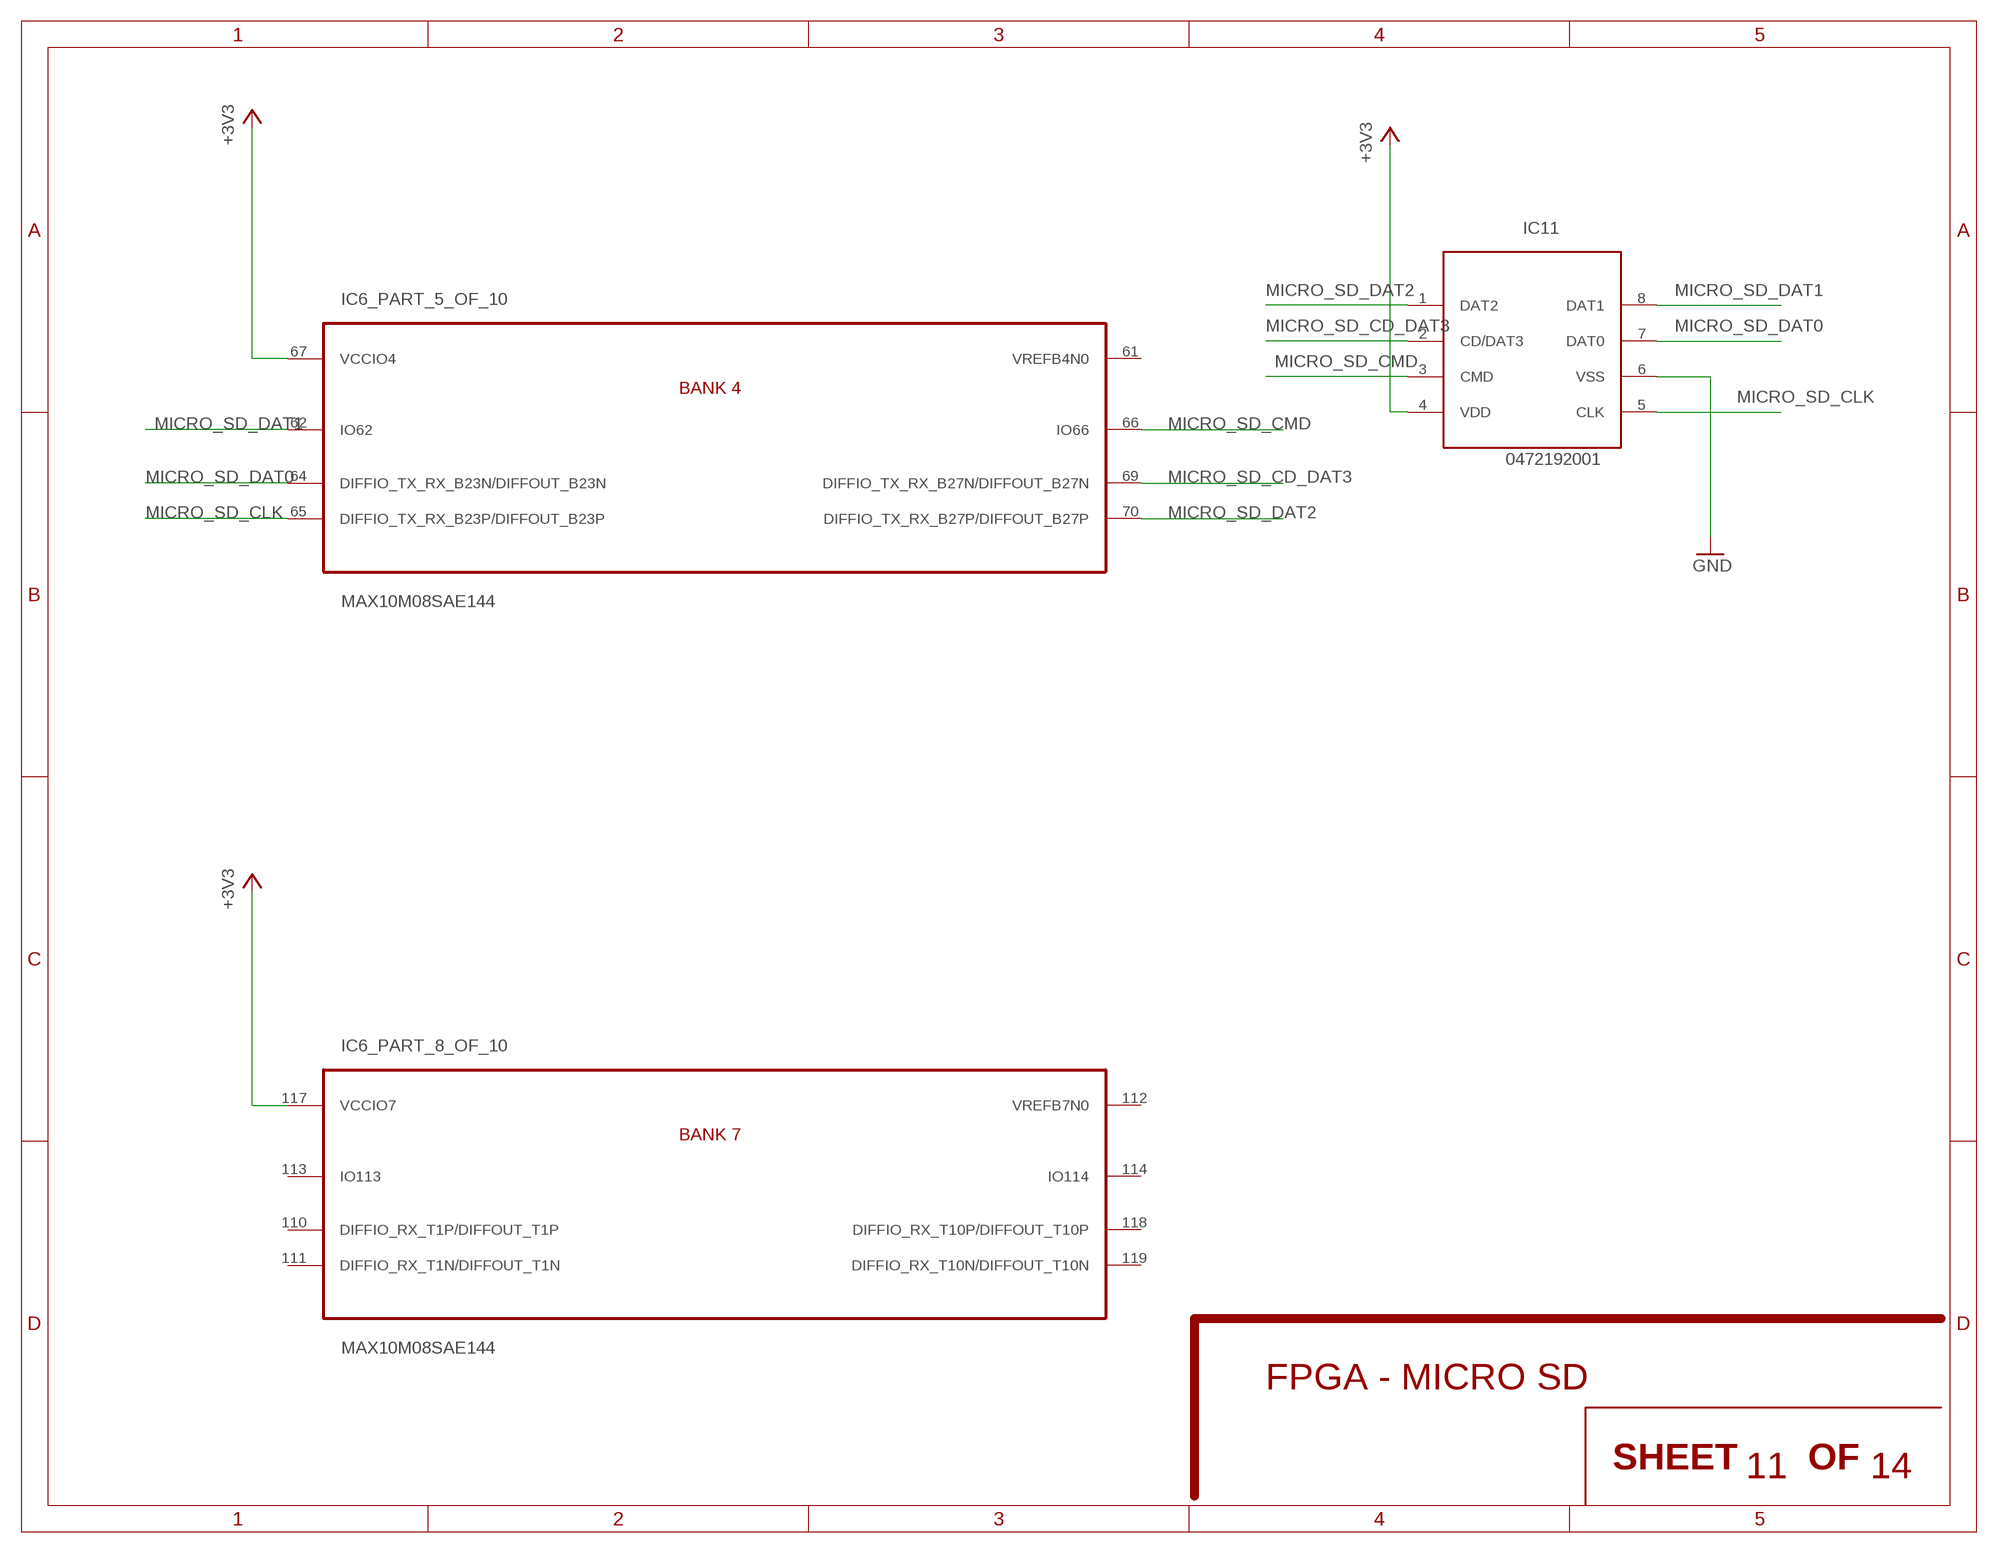
[diagram p10: schematic, sheet 11]
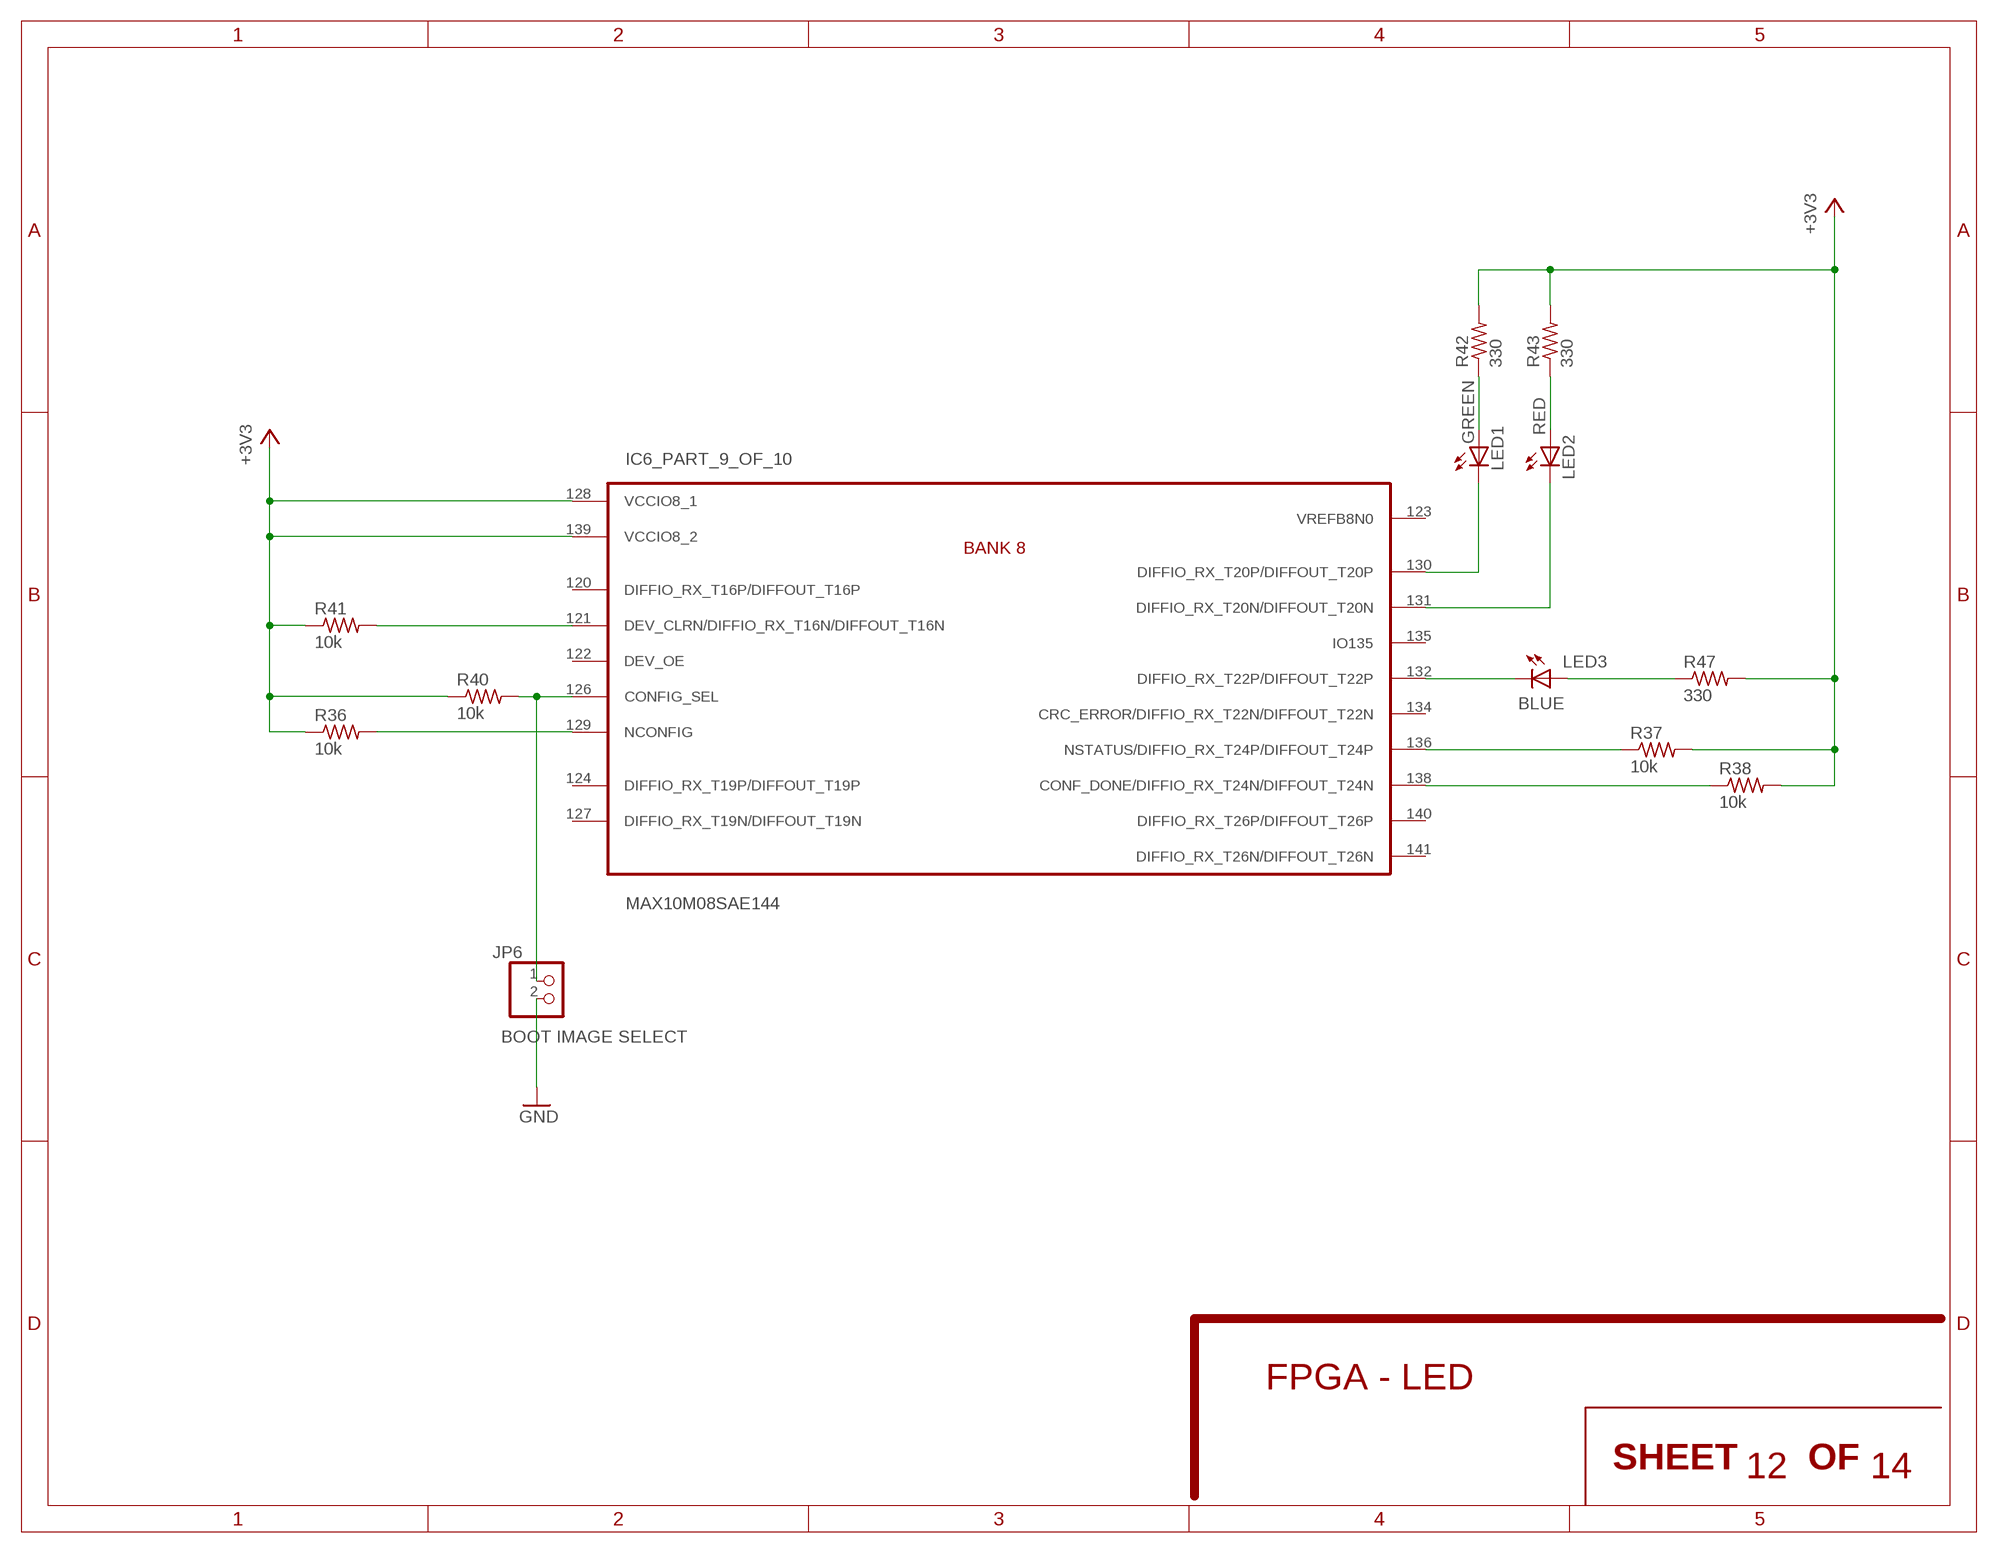
[diagram p11: schematic, sheet 12]
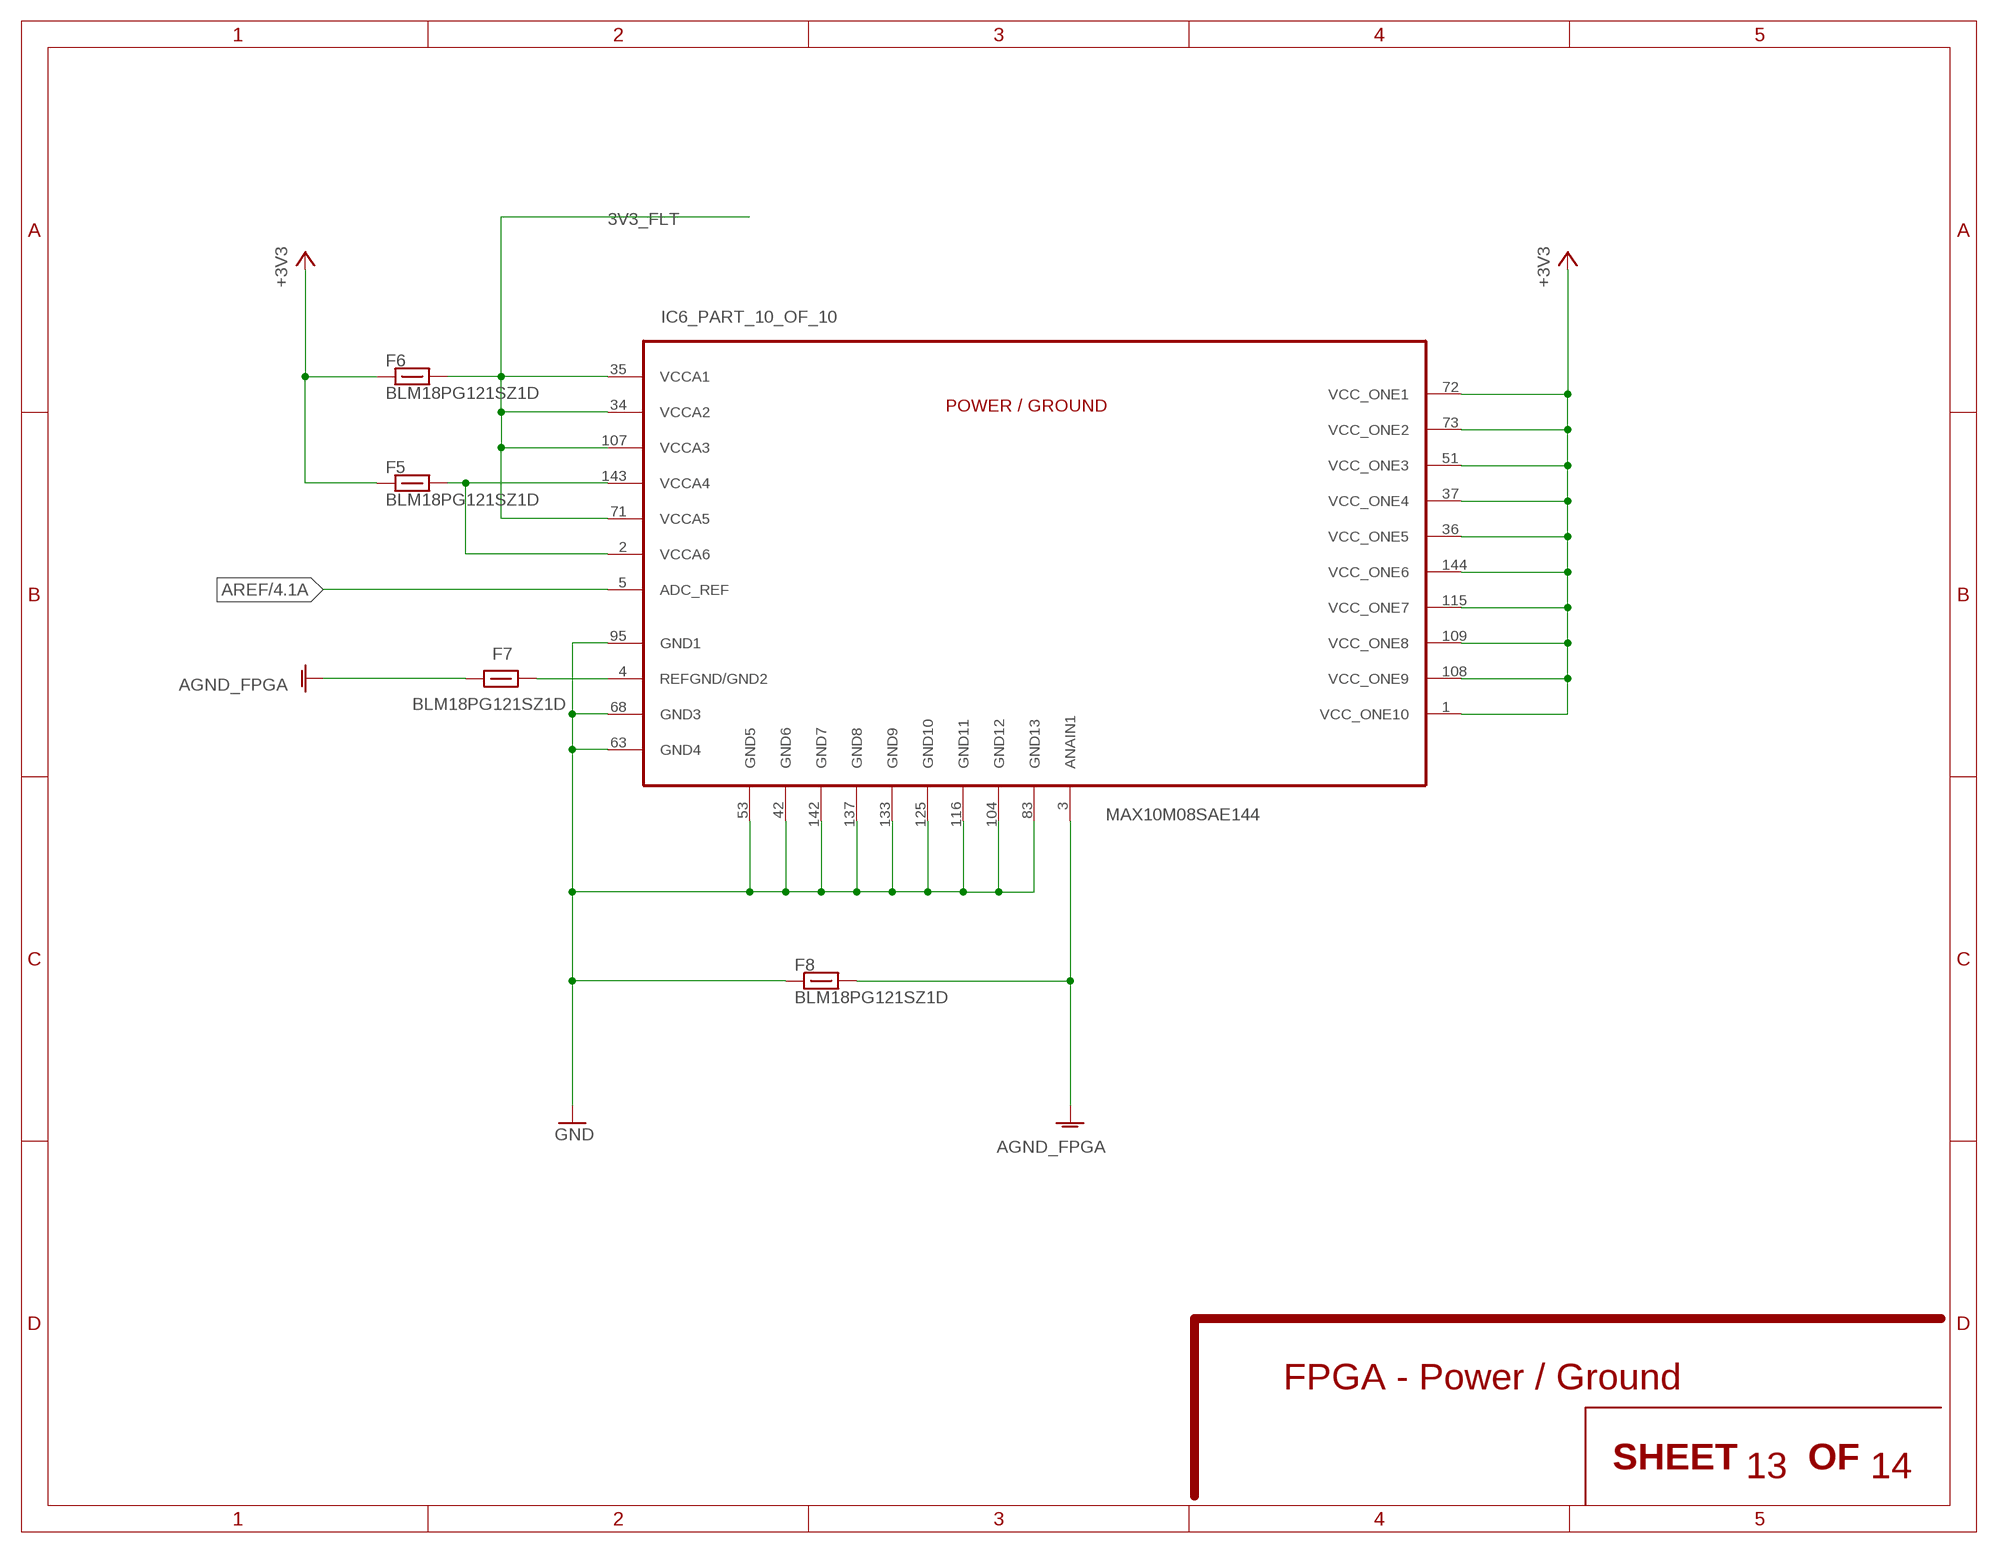
[diagram p12: schematic, sheet 13]
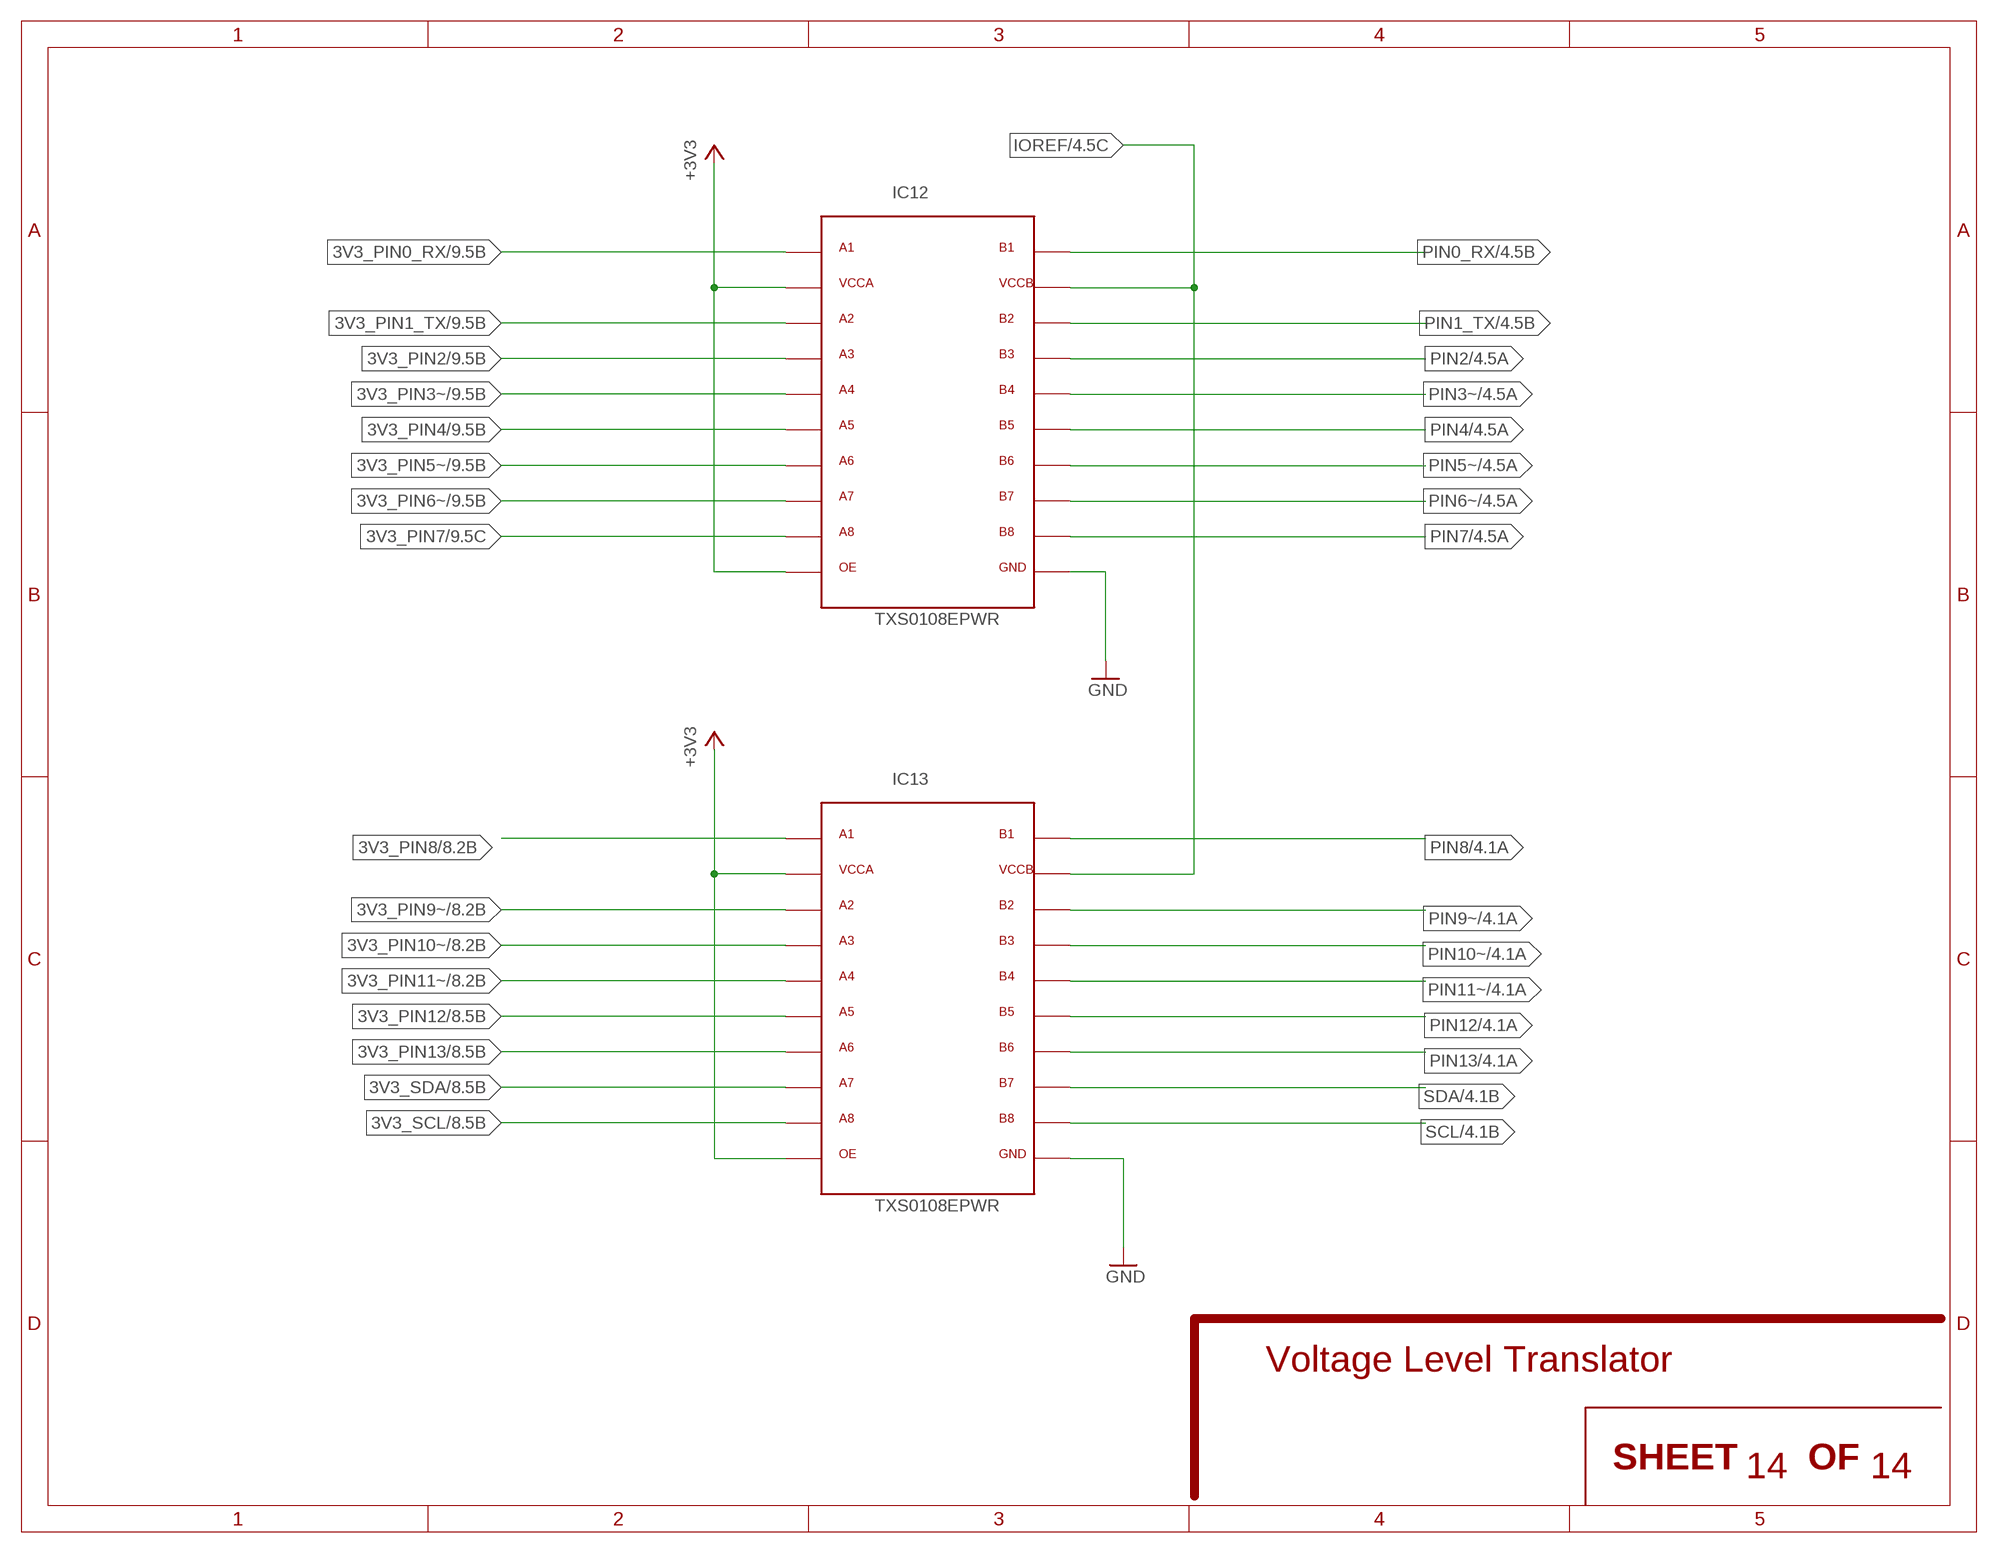
[diagram p13: schematic, sheet 14]

(export (version "E")
  (design (tool "Eeschema 10.0.6"))
  (components
    (comp (ref "GND")
      (value "PULSERAIN_LOGO_BIGGER")
      (footprint "eagle-import:PULSERAIN_LOGO_BIGGER")
      (libsource (lib "eagle-import") (part "PULSERAIN_LOGO_BIGGER"))
    )
    (comp (ref "C18")
      (value "0.1u")
      (footprint "eagle-import:0603-CAP")
      (fields (field (name "MF") "Vishay") (field (name "MPN") "VJ0603Y104JXJPW1BC"))
      (libsource (lib "eagle-import") (part "C-US_0.1U"))
    )
    (comp (ref "J8")
      (value "DUINO_IO_HEADER_10")
      (footprint "eagle-import:DUINO_IO_HEADER_10")
      (fields (field (name "MF") "Sullins Connector Solutions") (field (name "MPN") "PPTC101LFBN-RC"))
      (libsource (lib "eagle-import") (part "DUINO_IO_HEADER_10"))
    )
    (comp (ref "J9")
      (value "DUINO_HEADER_8")
      (footprint "eagle-import:DUINO_IO_HEADER_8")
      (fields (field (name "MF") "Sullins Connector Solutions") (field (name "MPN") "PPTC081LFBN-RC"))
      (libsource (lib "eagle-import") (part "DUINO_IO_HEADER_8"))
    )
    (comp (ref "J10")
      (value "DUINO_HEADER_8")
      (footprint "eagle-import:DUINO_PWR_HEADER_8")
      (fields (field (name "MF") "Sullins Connector Solutions") (field (name "MPN") "PPTC081LFBN-RC"))
      (libsource (lib "eagle-import") (part "DUINO_PWR_HEADER_8"))
    )
    (comp (ref "J11")
      (value "DUINO_ANALOG_HEADER_6")
      (footprint "eagle-import:DUINO_ANALOG_HEADER_6")
      (fields (field (name "MF") "Sullins Connector Solutions") (field (name "MPN") "PPTC061LFBN-RC"))
      (libsource (lib "eagle-import") (part "DUINO_ANALOG_HEADER_6"))
    )
    (comp (ref "JP1")
      (value "IOREF JUMPER")
      (footprint "eagle-import:1X03")
      (fields (field (name "MF") "Harwin") (field (name "MPN") "M20-9990346"))
      (libsource (lib "eagle-import") (part "PINHD-1X3"))
    )
    (comp (ref "LED_IOREF")
      (value "BLUE")
      (footprint "eagle-import:HARVATEK_0603")
      (fields (field (name "MF") "Inolux / Harvatek") (field (name "MPN") "HT-193NB-5589"))
      (libsource (lib "eagle-import") (part "HT--193NB-5589-BLUE"))
    )
    (comp (ref "R22")
      (value "330")
      (footprint "eagle-import:VISHAY-R-0603")
      (fields (field (name "MF") "YAGEO") (field (name "MPN") "RC0603FR-07330RL"))
      (libsource (lib "eagle-import") (part "R-US_330_YAGEO"))
    )
    (comp (ref "U$8")
      (value "DUINO")
      (footprint "eagle-import:DUINO")
      (libsource (lib "eagle-import") (part "DUINO"))
    )
    (comp (ref "C9")
      (value "22u")
      (footprint "eagle-import:PANASONIC_B")
      (fields (field (name "MF") "Panasonic") (field (name "MPN") "EEE-FK1A220AR"))
      (libsource (lib "eagle-import") (part "CPOL_USB22U"))
    )
    (comp (ref "C10")
      (value "0.1u")
      (footprint "eagle-import:0603-CAP")
      (fields (field (name "MF") "Vishay") (field (name "MPN") "VJ0603Y104JXJPW1BC"))
      (libsource (lib "eagle-import") (part "C-US_0.1U"))
    )
    (comp (ref "C11")
      (value "0.1u")
      (footprint "eagle-import:0603-CAP")
      (fields (field (name "MF") "Vishay") (field (name "MPN") "VJ0603Y104JXJPW1BC"))
      (libsource (lib "eagle-import") (part "C-US_0.1U"))
    )
    (comp (ref "F1")
      (value "BLM18PG121SZ1D")
      (footprint "eagle-import:0603-BEAD")
      (fields (field (name "MF") "muRata"))
      (libsource (lib "eagle-import") (part "BLM18PG"))
    )
    (comp (ref "IC5")
      (value "FT232RL")
      (footprint "eagle-import:SSOP28")
      (fields (field (name "MF") "FTDI"))
      (libsource (lib "eagle-import") (part "FT232RL"))
    )
    (comp (ref "IC6")
      (value "MAX10M08SAE144")
      (footprint "eagle-import:EQFP144")
      (fields (field (name "MF") "Altera") (field (name "MPN") "10M08SAE144C8G"))
      (libsource (lib "eagle-import") (part "MAX10M08SAE144"))
    )
    (comp (ref "J2")
      (value "MICRO-USB-B")
      (footprint "eagle-import:SD-47346-001")
      (fields (field (name "MF") "Molex") (field (name "MPN") "47346-1001"))
      (libsource (lib "eagle-import") (part "MICRO-USB-B-REC-47346-001"))
    )
    (comp (ref "R9")
      (value "330")
      (footprint "eagle-import:VISHAY-R-0603")
      (fields (field (name "MF") "YAGEO") (field (name "MPN") "RC0603FR-07330RL"))
      (libsource (lib "eagle-import") (part "R-US_330_YAGEO"))
    )
    (comp (ref "R10")
      (value "330")
      (footprint "eagle-import:VISHAY-R-0603")
      (fields (field (name "MF") "YAGEO") (field (name "MPN") "RC0603FR-07330RL"))
      (libsource (lib "eagle-import") (part "R-US_330_YAGEO"))
    )
    (comp (ref "R32")
      (value "DNI")
      (footprint "eagle-import:VISHAY-R-0603")
      (fields (field (name "MF") "Vishay") (field (name "MPN") "CRCW060310K0FKEA"))
      (libsource (lib "eagle-import") (part "R-US_10K"))
    )
    (comp (ref "SW1")
      (value "TE-2-1437565-8")
      (footprint "eagle-import:TE-2-1437565-8")
      (fields (field (name "MF") "TE Connectivity") (field (name "MPN") "2-1437565-8"))
      (libsource (lib "eagle-import") (part "PUSH_BUTTON"))
    )
    (comp (ref "SW2")
      (value "TE-2-1437565-8")
      (footprint "eagle-import:TE-2-1437565-8")
      (fields (field (name "MF") "TE Connectivity") (field (name "MPN") "2-1437565-8"))
      (libsource (lib "eagle-import") (part "PUSH_BUTTON"))
    )
    (comp (ref "UART_RX")
      (value "RED")
      (footprint "eagle-import:HARVATEK_0603")
      (fields (field (name "MF") "Inolux / Harvatek") (field (name "MPN") "HT-191URO-5502"))
      (libsource (lib "eagle-import") (part "HT--191URO-5502-RED"))
    )
    (comp (ref "UART_TX")
      (value "GREEN")
      (footprint "eagle-import:HARVATEK_0603")
      (fields (field (name "MF") "Inolux / Harvatek") (field (name "MPN") "HT-193UYG-5592"))
      (libsource (lib "eagle-import") (part "HT--193UYG-5592-GREEN"))
    )
    (comp (ref "IC9")
      (value "12MHz")
      (footprint "eagle-import:ACHL-DIP")
      (fields (field (name "MF") "ABRACON") (field (name "MPN") "ACHL-12.000MHZ-EK"))
      (libsource (lib "eagle-import") (part "ACHL-DIPACHL-12.000MHZ-EK"))
    )
    (comp (ref "IC10")
      (value "SRAM")
      (footprint "eagle-import:TSSOP-ST-8")
      (fields (field (name "MF") "Microchip Technology") (field (name "MPN") "23LC1024-I/ST"))
      (libsource (lib "eagle-import") (part "23LC1024"))
    )
    (comp (ref "C1")
      (value "22u")
      (footprint "eagle-import:PANASONIC_B")
      (fields (field (name "MF") "Panasonic") (field (name "MPN") "EEE-FK1A220AR"))
      (libsource (lib "eagle-import") (part "CPOL_USB22U"))
    )
    (comp (ref "C2")
      (value "22u")
      (footprint "eagle-import:PANASONIC_B")
      (fields (field (name "MF") "Panasonic") (field (name "MPN") "EEE-FK1A220AR"))
      (libsource (lib "eagle-import") (part "CPOL_USB22U"))
    )
    (comp (ref "C4")
      (value "22p")
      (footprint "eagle-import:0603-CAP")
      (fields (field (name "MF") "Vishay") (field (name "MPN") "VJ0603A220JXACW1BC"))
      (libsource (lib "eagle-import") (part "C-US_22P"))
    )
    (comp (ref "C5")
      (value "22u")
      (footprint "eagle-import:PANASONIC_B")
      (fields (field (name "MF") "Panasonic") (field (name "MPN") "EEE-FK1A220AR"))
      (libsource (lib "eagle-import") (part "CPOL_USB22U"))
    )
    (comp (ref "C26")
      (value "22u")
      (footprint "eagle-import:PANASONIC_B")
      (fields (field (name "MF") "Panasonic") (field (name "MPN") "EEE-FK1A220AR"))
      (libsource (lib "eagle-import") (part "CPOL_USB22U"))
    )
    (comp (ref "D1")
      (value "PMEG3020ER")
      (footprint "eagle-import:SOD123W")
      (fields (field (name "MF") "NXP"))
      (libsource (lib "eagle-import") (part "PMEG3020ER"))
    )
    (comp (ref "IC1")
      (value "AZ1117IH-5.0TRG1")
      (footprint "eagle-import:SOT223")
      (fields (field (name "MF") "Diodes Incorporated"))
      (libsource (lib "eagle-import") (part "AZ1117IH-5.0TRG1"))
    )
    (comp (ref "IC2")
      (value "AP3429A")
      (footprint "eagle-import:TSOT25")
      (fields (field (name "MF") "Diodes Incorporated") (field (name "MPN") "AP3429AKTTR-G1"))
      (libsource (lib "eagle-import") (part "AP3429A"))
    )
    (comp (ref "IC4")
      (value "MCP6241UT-E/LT")
      (footprint "eagle-import:SC-70-5")
      (fields (field (name "MF") "Microchip Technology"))
      (libsource (lib "eagle-import") (part "MCP6241UT-E/LT"))
    )
    (comp (ref "J1")
      (value "PJ-051A")
      (footprint "eagle-import:PJ-051A")
      (fields (field (name "MF") "CUI"))
      (libsource (lib "eagle-import") (part "PJ-051A"))
    )
    (comp (ref "L1")
      (value "2.2u")
      (footprint "eagle-import:DFE252012C")
      (fields (field (name "MF") "muRata") (field (name "MPN") "1239AS-H-2R2M=P2"))
      (libsource (lib "eagle-import") (part "L-US_2.2U"))
    )
    (comp (ref "PMOS1")
      (value "PMOS_SQ1421EDH")
      (footprint "eagle-import:SC70-6L")
      (fields (field (name "MF") "Vishay") (field (name "MPN") " SQ1421EDH-T1_GE3 "))
      (libsource (lib "eagle-import") (part "PMOS_SQ1421EDH"))
    )
    (comp (ref "R1")
      (value "10k")
      (footprint "eagle-import:VISHAY-R-0603")
      (fields (field (name "MF") "YAGEO") (field (name "MPN") "RC0603FR-0710KL"))
      (libsource (lib "eagle-import") (part "R-US_10K_YAGEO"))
    )
    (comp (ref "R2")
      (value "226k, 1%")
      (footprint "eagle-import:VISHAY-R-0603")
      (fields (field (name "MF") "Vishay") (field (name "MPN") "CRCW0603226KFKEA"))
      (libsource (lib "eagle-import") (part "R-US_226K"))
    )
    (comp (ref "R3")
      (value "49.9k, 1%")
      (footprint "eagle-import:VISHAY-R-0603")
      (fields (field (name "MF") "Vishay") (field (name "MPN") "CRCW060349K9FKEA"))
      (libsource (lib "eagle-import") (part "R-US_49K9"))
    )
    (comp (ref "R7")
      (value "10k")
      (footprint "eagle-import:VISHAY-R-0603")
      (fields (field (name "MF") "YAGEO") (field (name "MPN") "RC0603FR-0710KL"))
      (libsource (lib "eagle-import") (part "R-US_10K_YAGEO"))
    )
    (comp (ref "R8")
      (value "10k")
      (footprint "eagle-import:VISHAY-R-0603")
      (fields (field (name "MF") "YAGEO") (field (name "MPN") "RC0603FR-0710KL"))
      (libsource (lib "eagle-import") (part "R-US_10K_YAGEO"))
    )
    (comp (ref "JP6")
      (value "BOOT IMAGE SELECT")
      (footprint "eagle-import:1X02")
      (fields (field (name "MF") "Harwin") (field (name "MPN") "M20-9990246"))
      (libsource (lib "eagle-import") (part "PINHD-1X2"))
    )
    (comp (ref "LED1")
      (value "GREEN")
      (footprint "eagle-import:HARVATEK_0603")
      (fields (field (name "MF") "Inolux / Harvatek") (field (name "MPN") "HT-193UYG-5592"))
      (libsource (lib "eagle-import") (part "HT--193UYG-5592-GREEN"))
    )
    (comp (ref "LED2")
      (value "RED")
      (footprint "eagle-import:HARVATEK_0603")
      (fields (field (name "MF") "Inolux / Harvatek") (field (name "MPN") "HT-191URO-5502"))
      (libsource (lib "eagle-import") (part "HT--191URO-5502-RED"))
    )
    (comp (ref "LED3")
      (value "BLUE")
      (footprint "eagle-import:HARVATEK_0603")
      (fields (field (name "MF") "Inolux / Harvatek") (field (name "MPN") "HT-193NB-5589"))
      (libsource (lib "eagle-import") (part "HT--193NB-5589-BLUE"))
    )
    (comp (ref "R36")
      (value "10k")
      (footprint "eagle-import:VISHAY-R-0603")
      (fields (field (name "MF") "YAGEO") (field (name "MPN") "RC0603FR-0710KL"))
      (libsource (lib "eagle-import") (part "R-US_10K_YAGEO"))
    )
    (comp (ref "R37")
      (value "10k")
      (footprint "eagle-import:VISHAY-R-0603")
      (fields (field (name "MF") "YAGEO") (field (name "MPN") "RC0603FR-0710KL"))
      (libsource (lib "eagle-import") (part "R-US_10K_YAGEO"))
    )
    (comp (ref "R38")
      (value "10k")
      (footprint "eagle-import:VISHAY-R-0603")
      (fields (field (name "MF") "YAGEO") (field (name "MPN") "RC0603FR-0710KL"))
      (libsource (lib "eagle-import") (part "R-US_10K_YAGEO"))
    )
    (comp (ref "R40")
      (value "10k")
      (footprint "eagle-import:VISHAY-R-0603")
      (fields (field (name "MF") "YAGEO") (field (name "MPN") "RC0603FR-0710KL"))
      (libsource (lib "eagle-import") (part "R-US_10K_YAGEO"))
    )
    (comp (ref "R41")
      (value "10k")
      (footprint "eagle-import:VISHAY-R-0603")
      (fields (field (name "MF") "YAGEO") (field (name "MPN") "RC0603FR-0710KL"))
      (libsource (lib "eagle-import") (part "R-US_10K_YAGEO"))
    )
    (comp (ref "R42")
      (value "330")
      (footprint "eagle-import:VISHAY-R-0603")
      (fields (field (name "MF") "YAGEO") (field (name "MPN") "RC0603FR-07330RL"))
      (libsource (lib "eagle-import") (part "R-US_330_YAGEO"))
    )
    (comp (ref "R43")
      (value "330")
      (footprint "eagle-import:VISHAY-R-0603")
      (fields (field (name "MF") "YAGEO") (field (name "MPN") "RC0603FR-07330RL"))
      (libsource (lib "eagle-import") (part "R-US_330_YAGEO"))
    )
    (comp (ref "R47")
      (value "330")
      (footprint "eagle-import:VISHAY-R-0603")
      (fields (field (name "MF") "YAGEO") (field (name "MPN") "RC0603FR-07330RL"))
      (libsource (lib "eagle-import") (part "R-US_330_YAGEO"))
    )
    (comp (ref "IC12")
      (value "TXS0108EPWR")
      (footprint "eagle-import:TSSOP8")
      (fields (field (name "MF") "Texas Instruments"))
      (libsource (lib "eagle-import") (part "TXS0108E"))
    )
    (comp (ref "IC13")
      (value "TXS0108EPWR")
      (footprint "eagle-import:TSSOP8")
      (fields (field (name "MF") "Texas Instruments"))
      (libsource (lib "eagle-import") (part "TXS0108E"))
    )
    (comp (ref "J7")
      (value "ALTERA_JTAG")
      (footprint "eagle-import:2X05")
      (fields (field (name "MF") "Harwin") (field (name "MPN") "M20-9760546 "))
      (libsource (lib "eagle-import") (part "ALTERA_JTAG"))
    )
    (comp (ref "JP2")
      (value "DNI")
      (footprint "eagle-import:1X02")
      (fields (field (name "MF") "Harwin") (field (name "MPN") "M20-9990246"))
      (libsource (lib "eagle-import") (part "PINHD-1X2"))
    )
    (comp (ref "R33")
      (value "10k")
      (footprint "eagle-import:VISHAY-R-0603")
      (fields (field (name "MF") "YAGEO") (field (name "MPN") "RC0603FR-0710KL"))
      (libsource (lib "eagle-import") (part "R-US_10K_YAGEO"))
    )
    (comp (ref "R34")
      (value "10k")
      (footprint "eagle-import:VISHAY-R-0603")
      (fields (field (name "MF") "YAGEO") (field (name "MPN") "RC0603FR-0710KL"))
      (libsource (lib "eagle-import") (part "R-US_10K_YAGEO"))
    )
    (comp (ref "R35")
      (value "10k")
      (footprint "eagle-import:VISHAY-R-0603")
      (fields (field (name "MF") "YAGEO") (field (name "MPN") "RC0603FR-0710KL"))
      (libsource (lib "eagle-import") (part "R-US_10K_YAGEO"))
    )
    (comp (ref "R39")
      (value "1k")
      (footprint "eagle-import:VISHAY-R-0603")
      (fields (field (name "MF") "Vishay") (field (name "MPN") "CRCW06031K00FKEA"))
      (libsource (lib "eagle-import") (part "R-US_1K"))
    )
    (comp (ref "C19")
      (value "1000p")
      (footprint "eagle-import:VISHAY-R-0603")
      (fields (field (name "MF") "Vishay") (field (name "MPN") "VJ0603Y102JXJPW1BC"))
      (libsource (lib "eagle-import") (part "C-US_1000P"))
    )
    (comp (ref "C20")
      (value "1000p")
      (footprint "eagle-import:VISHAY-R-0603")
      (fields (field (name "MF") "Vishay") (field (name "MPN") "VJ0603Y102JXJPW1BC"))
      (libsource (lib "eagle-import") (part "C-US_1000P"))
    )
    (comp (ref "C21")
      (value "1000p")
      (footprint "eagle-import:VISHAY-R-0603")
      (fields (field (name "MF") "Vishay") (field (name "MPN") "VJ0603Y102JXJPW1BC"))
      (libsource (lib "eagle-import") (part "C-US_1000P"))
    )
    (comp (ref "C22")
      (value "1000p")
      (footprint "eagle-import:VISHAY-R-0603")
      (fields (field (name "MF") "Vishay") (field (name "MPN") "VJ0603Y102JXJPW1BC"))
      (libsource (lib "eagle-import") (part "C-US_1000P"))
    )
    (comp (ref "C23")
      (value "1000p")
      (footprint "eagle-import:VISHAY-R-0603")
      (fields (field (name "MF") "Vishay") (field (name "MPN") "VJ0603Y102JXJPW1BC"))
      (libsource (lib "eagle-import") (part "C-US_1000P"))
    )
    (comp (ref "C24")
      (value "1000p")
      (footprint "eagle-import:VISHAY-R-0603")
      (fields (field (name "MF") "Vishay") (field (name "MPN") "VJ0603Y102JXJPW1BC"))
      (libsource (lib "eagle-import") (part "C-US_1000P"))
    )
    (comp (ref "F4")
      (value "BLM18PG121SZ1D")
      (footprint "eagle-import:0603-BEAD")
      (fields (field (name "MF") "muRata"))
      (libsource (lib "eagle-import") (part "BLM18PG"))
    )
    (comp (ref "R23")
      (value "100")
      (footprint "eagle-import:VISHAY-R-0603")
      (fields (field (name "MF") "Vishay") (field (name "MPN") "CRCW0603100RFKEA"))
      (libsource (lib "eagle-import") (part "R-US_100"))
    )
    (comp (ref "R24")
      (value "100")
      (footprint "eagle-import:VISHAY-R-0603")
      (fields (field (name "MF") "Vishay") (field (name "MPN") "CRCW0603100RFKEA"))
      (libsource (lib "eagle-import") (part "R-US_100"))
    )
    (comp (ref "R25")
      (value "100")
      (footprint "eagle-import:VISHAY-R-0603")
      (fields (field (name "MF") "Vishay") (field (name "MPN") "CRCW0603100RFKEA"))
      (libsource (lib "eagle-import") (part "R-US_100"))
    )
    (comp (ref "R26")
      (value "100")
      (footprint "eagle-import:VISHAY-R-0603")
      (fields (field (name "MF") "Vishay") (field (name "MPN") "CRCW0603100RFKEA"))
      (libsource (lib "eagle-import") (part "R-US_100"))
    )
    (comp (ref "R27")
      (value "100")
      (footprint "eagle-import:VISHAY-R-0603")
      (fields (field (name "MF") "Vishay") (field (name "MPN") "CRCW0603100RFKEA"))
      (libsource (lib "eagle-import") (part "R-US_100"))
    )
    (comp (ref "R28")
      (value "100")
      (footprint "eagle-import:VISHAY-R-0603")
      (fields (field (name "MF") "Vishay") (field (name "MPN") "CRCW0603100RFKEA"))
      (libsource (lib "eagle-import") (part "R-US_100"))
    )
    (comp (ref "C3")
      (value "0.1u")
      (footprint "eagle-import:0603-CAP")
      (fields (field (name "MF") "Vishay") (field (name "MPN") "VJ0603Y104JXJPW1BC"))
      (libsource (lib "eagle-import") (part "C-US_0.1U"))
    )
    (comp (ref "C6")
      (value "1u")
      (footprint "eagle-import:VISHAY-R-0603")
      (fields (field (name "MF") "Vishay") (field (name "MPN") "VJ0603V105MXQPW1BC"))
      (libsource (lib "eagle-import") (part "C-US_1U"))
    )
    (comp (ref "C7")
      (value "1u")
      (footprint "eagle-import:VISHAY-R-0603")
      (fields (field (name "MF") "Vishay") (field (name "MPN") "VJ0603V105MXQPW1BC"))
      (libsource (lib "eagle-import") (part "C-US_1U"))
    )
    (comp (ref "C25")
      (value "1u")
      (footprint "eagle-import:VISHAY-R-0603")
      (fields (field (name "MF") "Vishay") (field (name "MPN") "VJ0603V105MXQPW1BC"))
      (libsource (lib "eagle-import") (part "C-US_1U"))
    )
    (comp (ref "F2")
      (value "BLM18PG121SZ1D")
      (footprint "eagle-import:0603-BEAD")
      (fields (field (name "MF") "muRata"))
      (libsource (lib "eagle-import") (part "BLM18PG"))
    )
    (comp (ref "IC3")
      (value "SI3000")
      (footprint "eagle-import:SOIC-16")
      (fields (field (name "MF") "Silicon Labs") (field (name "MPN") "Si3000-C-FS"))
      (libsource (lib "eagle-import") (part "SI3000-C-FS"))
    )
    (comp (ref "J4")
      (value "PHONE_JACK_NOT_SWITCHED")
      (footprint "eagle-import:PHONE_JACK_NOT_SWITCHED")
      (fields (field (name "MF") "Switchcraft") (field (name "MPN") "35RASMT2BHNTRX"))
      (libsource (lib "eagle-import") (part "PHONE_JACK_NOT_SWITCHED"))
    )
    (comp (ref "MIC1")
      (value "MIC-CUICMC-5044PF-A")
      (footprint "eagle-import:CMC-5044PF-A")
      (fields (field (name "MF") "CUI") (field (name "MPN") "CMC-5044PF-A"))
      (libsource (lib "eagle-import") (part "MIC-CUICMC-5044PF-A"))
    )
    (comp (ref "R5")
      (value "2.2k")
      (footprint "eagle-import:VISHAY-R-0603")
      (fields (field (name "MF") "Vishay") (field (name "MPN") "CRCW06032K20FKEA"))
      (libsource (lib "eagle-import") (part "R-US_2.2K"))
    )
    (comp (ref "R6")
      (value "30")
      (footprint "eagle-import:VISHAY-R-0603")
      (fields (field (name "MF") "Vishay") (field (name "MPN") "CRCW060330R0FKEA"))
      (libsource (lib "eagle-import") (part "R-US_30"))
    )
    (comp (ref "R29")
      (value "30")
      (footprint "eagle-import:VISHAY-R-0603")
      (fields (field (name "MF") "Vishay") (field (name "MPN") "CRCW060330R0FKEA"))
      (libsource (lib "eagle-import") (part "R-US_30"))
    )
    (comp (ref "IC11")
      (value "0472192001")
      (footprint "eagle-import:MOLEX-0472192001")
      (fields (field (name "MF") "Molex"))
      (libsource (lib "eagle-import") (part "MOLEX-0472192001"))
    )
    (comp (ref "C12")
      (value "1p")
      (footprint "eagle-import:0603-CAP")
      (fields (field (name "MF") "Vishay") (field (name "MPN") "VJ0603A1R0BXACW1BC"))
      (libsource (lib "eagle-import") (part "C-US_1P"))
    )
    (comp (ref "C13")
      (value "1p")
      (footprint "eagle-import:0603-CAP")
      (fields (field (name "MF") "Vishay") (field (name "MPN") "VJ0603A1R0BXACW1BC"))
      (libsource (lib "eagle-import") (part "C-US_1P"))
    )
    (comp (ref "C14")
      (value "1p")
      (footprint "eagle-import:0603-CAP")
      (fields (field (name "MF") "Vishay") (field (name "MPN") "VJ0603A1R0BXACW1BC"))
      (libsource (lib "eagle-import") (part "C-US_1P"))
    )
    (comp (ref "C15")
      (value "1p")
      (footprint "eagle-import:0603-CAP")
      (fields (field (name "MF") "Vishay") (field (name "MPN") "VJ0603A1R0BXACW1BC"))
      (libsource (lib "eagle-import") (part "C-US_1P"))
    )
    (comp (ref "C16")
      (value "1p")
      (footprint "eagle-import:0603-CAP")
      (fields (field (name "MF") "Vishay") (field (name "MPN") "VJ0603A1R0BXACW1BC"))
      (libsource (lib "eagle-import") (part "C-US_1P"))
    )
    (comp (ref "C17")
      (value "1p")
      (footprint "eagle-import:0603-CAP")
      (fields (field (name "MF") "Vishay") (field (name "MPN") "VJ0603A1R0BXACW1BC"))
      (libsource (lib "eagle-import") (part "C-US_1P"))
    )
    (comp (ref "F3")
      (value "BLM18PG121SZ1D")
      (footprint "eagle-import:0603-BEAD")
      (fields (field (name "MF") "muRata"))
      (libsource (lib "eagle-import") (part "BLM18PG"))
    )
    (comp (ref "IC7")
      (value "MCP6242T-E/SN")
      (footprint "eagle-import:SOIC-SN-8")
      (fields (field (name "MF") "Microchip Technology"))
      (libsource (lib "eagle-import") (part "MCP6242T-E/SN"))
    )
    (comp (ref "IC8")
      (value "MCP6244T-E/ST")
      (footprint "eagle-import:TSSOP-ST-14")
      (fields (field (name "MF") "Microchip Technology"))
      (libsource (lib "eagle-import") (part "MCP6244T-E/ST"))
    )
    (comp (ref "PT1")
      (value "200k")
      (footprint "eagle-import:PT10LV10")
      (fields (field (name "MF") "Piher") (field (name "MPN") "PT10LV10-204A2020"))
      (libsource (lib "eagle-import") (part "PT10LV10"))
    )
    (comp (ref "R11")
      (value "100k")
      (footprint "eagle-import:VISHAY-R-0603")
      (fields (field (name "MF") "YAGEO") (field (name "MPN") "RC0603FR-07100KL"))
      (libsource (lib "eagle-import") (part "R-US_100K_YAGEO"))
    )
    (comp (ref "R12")
      (value "100k")
      (footprint "eagle-import:VISHAY-R-0603")
      (fields (field (name "MF") "YAGEO") (field (name "MPN") "RC0603FR-07100KL"))
      (libsource (lib "eagle-import") (part "R-US_100K_YAGEO"))
    )
    (comp (ref "R13")
      (value "200k")
      (footprint "eagle-import:VISHAY-R-0603")
      (fields (field (name "MF") "Vishay") (field (name "MPN") "CRCW0603200KFKEA"))
      (libsource (lib "eagle-import") (part "R-US_200K"))
    )
    (comp (ref "R14")
      (value "100k")
      (footprint "eagle-import:VISHAY-R-0603")
      (fields (field (name "MF") "YAGEO") (field (name "MPN") "RC0603FR-07100KL"))
      (libsource (lib "eagle-import") (part "R-US_100K_YAGEO"))
    )
    (comp (ref "R15")
      (value "200k")
      (footprint "eagle-import:VISHAY-R-0603")
      (fields (field (name "MF") "Vishay") (field (name "MPN") "CRCW0603200KFKEA"))
      (libsource (lib "eagle-import") (part "R-US_200K"))
    )
    (comp (ref "R16")
      (value "100k")
      (footprint "eagle-import:VISHAY-R-0603")
      (fields (field (name "MF") "YAGEO") (field (name "MPN") "RC0603FR-07100KL"))
      (libsource (lib "eagle-import") (part "R-US_100K_YAGEO"))
    )
    (comp (ref "R17")
      (value "200k")
      (footprint "eagle-import:VISHAY-R-0603")
      (fields (field (name "MF") "Vishay") (field (name "MPN") "CRCW0603200KFKEA"))
      (libsource (lib "eagle-import") (part "R-US_200K"))
    )
    (comp (ref "R18")
      (value "100k")
      (footprint "eagle-import:VISHAY-R-0603")
      (fields (field (name "MF") "YAGEO") (field (name "MPN") "RC0603FR-07100KL"))
      (libsource (lib "eagle-import") (part "R-US_100K_YAGEO"))
    )
    (comp (ref "R19")
      (value "200k")
      (footprint "eagle-import:VISHAY-R-0603")
      (fields (field (name "MF") "Vishay") (field (name "MPN") "CRCW0603200KFKEA"))
      (libsource (lib "eagle-import") (part "R-US_200K"))
    )
    (comp (ref "R20")
      (value "100k")
      (footprint "eagle-import:VISHAY-R-0603")
      (fields (field (name "MF") "YAGEO") (field (name "MPN") "RC0603FR-07100KL"))
      (libsource (lib "eagle-import") (part "R-US_100K_YAGEO"))
    )
    (comp (ref "R21")
      (value "200k")
      (footprint "eagle-import:VISHAY-R-0603")
      (fields (field (name "MF") "Vishay") (field (name "MPN") "CRCW0603200KFKEA"))
      (libsource (lib "eagle-import") (part "R-US_200K"))
    )
    (comp (ref "F5")
      (value "BLM18PG121SZ1D")
      (footprint "eagle-import:0603-BEAD")
      (fields (field (name "MF") "muRata"))
      (libsource (lib "eagle-import") (part "BLM18PG"))
    )
    (comp (ref "F6")
      (value "BLM18PG121SZ1D")
      (footprint "eagle-import:0603-BEAD")
      (fields (field (name "MF") "muRata"))
      (libsource (lib "eagle-import") (part "BLM18PG"))
    )
    (comp (ref "F7")
      (value "BLM18PG121SZ1D")
      (footprint "eagle-import:0603-BEAD")
      (fields (field (name "MF") "muRata"))
      (libsource (lib "eagle-import") (part "BLM18PG"))
    )
    (comp (ref "F8")
      (value "BLM18PG121SZ1D")
      (footprint "eagle-import:0603-BEAD")
      (fields (field (name "MF") "muRata"))
      (libsource (lib "eagle-import") (part "BLM18PG"))
    )
  )
  (nets
    (net (code "1") (name "+3V3") (class "Default")
      (node (ref "C4") (pin "1") (pinfunction "1_1") (pintype "passive"))
      (node (ref "C5") (pin "+") (pinfunction "+_+") (pintype "passive"))
      (node (ref "F4") (pin "1") (pinfunction "1_1") (pintype "passive"))
      (node (ref "F5") (pin "1") (pinfunction "1_1") (pintype "passive"))
      (node (ref "F6") (pin "1") (pinfunction "1_1") (pintype "passive"))
      (node (ref "IC10") (pin "8") (pinfunction "VCC_8") (pintype "input"))
      (node (ref "IC11") (pin "4") (pinfunction "VDD_4") (pintype "input"))
      (node (ref "IC12") (pin "10") (pinfunction "10_10") (pintype "bidirectional"))
      (node (ref "IC12") (pin "2") (pinfunction "2_2") (pintype "input"))
      (node (ref "IC13") (pin "10") (pinfunction "10_10") (pintype "bidirectional"))
      (node (ref "IC13") (pin "2") (pinfunction "2_2") (pintype "input"))
      (node (ref "IC3") (pin "12") (pinfunction "VD_12") (pintype "input"))
      (node (ref "IC4") (pin "3") (pinfunction "-IN_3") (pintype "input"))
      (node (ref "IC6") (pin "1") (pinfunction "VCC_ONE10_1") (pintype "input"))
      (node (ref "IC6") (pin "103") (pinfunction "VCCIO6_2_103") (pintype "input"))
      (node (ref "IC6") (pin "108") (pinfunction "VCC_ONE9_108") (pintype "input"))
      (node (ref "IC6") (pin "109") (pinfunction "VCC_ONE8_109") (pintype "input"))
      (node (ref "IC6") (pin "115") (pinfunction "VCC_ONE7_115") (pintype "input"))
      (node (ref "IC6") (pin "117") (pinfunction "VCCIO7_117") (pintype "input"))
      (node (ref "IC6") (pin "128") (pinfunction "VCCIO8_1_128") (pintype "input"))
      (node (ref "IC6") (pin "139") (pinfunction "VCCIO8_2_139") (pintype "input"))
      (node (ref "IC6") (pin "144") (pinfunction "VCC_ONE6_144") (pintype "input"))
      (node (ref "IC6") (pin "23") (pinfunction "VCCIO1B_23") (pintype "input"))
      (node (ref "IC6") (pin "31") (pinfunction "VCCIO2_31") (pintype "input"))
      (node (ref "IC6") (pin "36") (pinfunction "VCC_ONE5_36") (pintype "input"))
      (node (ref "IC6") (pin "37") (pinfunction "VCC_ONE4_37") (pintype "input"))
      (node (ref "IC6") (pin "40") (pinfunction "VCCIO3_1_40") (pintype "input"))
      (node (ref "IC6") (pin "49") (pinfunction "VCCIO3_2_49") (pintype "input"))
      (node (ref "IC6") (pin "51") (pinfunction "VCC_ONE3_51") (pintype "input"))
      (node (ref "IC6") (pin "67") (pinfunction "VCCIO4_67") (pintype "input"))
      (node (ref "IC6") (pin "72") (pinfunction "VCC_ONE1_72") (pintype "input"))
      (node (ref "IC6") (pin "73") (pinfunction "VCC_ONE2_73") (pintype "input"))
      (node (ref "IC6") (pin "82") (pinfunction "VCCIO5_82") (pintype "input"))
      (node (ref "IC6") (pin "94") (pinfunction "VCCIO6_1_94") (pintype "input"))
      (node (ref "IC9") (pin "1") (pinfunction "EN_1") (pintype "input"))
      (node (ref "IC9") (pin "8") (pinfunction "VCC_8") (pintype "input"))
      (node (ref "J10") (pin "3.3V") (pinfunction "3.3V_3.3V") (pintype "bidirectional"))
      (node (ref "J7") (pin "4") (pinfunction "4_4") (pintype "passive"))
      (node (ref "JP1") (pin "3") (pinfunction "3_3") (pintype "passive"))
      (node (ref "L1") (pin "2") (pinfunction "2_2") (pintype "passive"))
      (node (ref "R2") (pin "P$2") (pinfunction "2_P$2") (pintype "passive"))
      (node (ref "R32") (pin "P$1") (pinfunction "1_P$1") (pintype "passive"))
      (node (ref "R33") (pin "P$1") (pinfunction "1_P$1") (pintype "passive"))
      (node (ref "R34") (pin "P$2") (pinfunction "2_P$2") (pintype "passive"))
      (node (ref "R35") (pin "P$2") (pinfunction "2_P$2") (pintype "passive"))
      (node (ref "R36") (pin "P$1") (pinfunction "1_P$1") (pintype "passive"))
      (node (ref "R37") (pin "P$2") (pinfunction "2_P$2") (pintype "passive"))
      (node (ref "R38") (pin "P$2") (pinfunction "2_P$2") (pintype "passive"))
      (node (ref "R40") (pin "P$1") (pinfunction "1_P$1") (pintype "passive"))
      (node (ref "R41") (pin "P$1") (pinfunction "1_P$1") (pintype "passive"))
      (node (ref "R42") (pin "P$2") (pinfunction "2_P$2") (pintype "passive"))
      (node (ref "R43") (pin "P$2") (pinfunction "2_P$2") (pintype "passive"))
      (node (ref "R47") (pin "P$2") (pinfunction "2_P$2") (pintype "passive"))
    )
    (net (code "2") (name "+5V") (class "Default")
      (node (ref "C2") (pin "+") (pinfunction "+_+") (pintype "passive"))
      (node (ref "C26") (pin "+") (pinfunction "+_+") (pintype "passive"))
      (node (ref "F3") (pin "2") (pinfunction "2_2") (pintype "passive"))
      (node (ref "IC1") (pin "2") (pinfunction "2_2") (pintype "input"))
      (node (ref "IC1") (pin "VOUT") (pinfunction "VOUT_VOUT") (pintype "input"))
      (node (ref "IC2") (pin "4") (pinfunction "VIN_4") (pintype "input"))
      (node (ref "IC4") (pin "5") (pinfunction "V+_5") (pintype "input"))
      (node (ref "J10") (pin "5V") (pinfunction "5V_5V") (pintype "bidirectional"))
      (node (ref "JP1") (pin "1") (pinfunction "1_1") (pintype "passive"))
      (node (ref "PMOS1") (pin "4") (pinfunction "S_4") (pintype "passive"))
      (node (ref "R1") (pin "P$1") (pinfunction "1_P$1") (pintype "passive"))
    )
    (net (code "3") (name "3V3_FLT") (class "Default")
      (node (ref "C25") (pin "P$1") (pinfunction "1_P$1") (pintype "passive"))
      (node (ref "F6") (pin "2") (pinfunction "2_2") (pintype "passive"))
      (node (ref "IC3") (pin "13") (pinfunction "VA_13") (pintype "input"))
      (node (ref "IC6") (pin "107") (pinfunction "VCCA3_107") (pintype "input"))
      (node (ref "IC6") (pin "34") (pinfunction "VCCA2_34") (pintype "input"))
      (node (ref "IC6") (pin "35") (pinfunction "VCCA1_35") (pintype "input"))
      (node (ref "IC6") (pin "71") (pinfunction "VCCA5_71") (pintype "input"))
    )
    (net (code "4") (name "3V3_PIN0_RX") (class "Default")
      (node (ref "IC12") (pin "1") (pinfunction "1_1") (pintype "bidirectional"))
      (node (ref "IC6") (pin "50") (pinfunction "DIFFIO_TX_RX_B9N/DIFFOUT_B9N_50") (pintype "bidirectional"))
    )
    (net (code "5") (name "3V3_PIN1_TX") (class "Default")
      (node (ref "IC12") (pin "3") (pinfunction "3_3") (pintype "bidirectional"))
      (node (ref "IC6") (pin "52") (pinfunction "DIFFIO_TX_RX_B9P/DIFFOUT_B9P_52") (pintype "bidirectional"))
    )
    (net (code "6") (name "3V3_PIN2") (class "Default")
      (node (ref "IC12") (pin "4") (pinfunction "4_4") (pintype "bidirectional"))
      (node (ref "IC6") (pin "54") (pinfunction "IO54_54") (pintype "bidirectional"))
    )
    (net (code "7") (name "3V3_PIN3~{}") (class "Default")
      (node (ref "IC12") (pin "5") (pinfunction "5_5") (pintype "bidirectional"))
      (node (ref "IC6") (pin "55") (pinfunction "DIFFIO_TX_RX_B12N/DIFFOUT_B12N_55") (pintype "bidirectional"))
    )
    (net (code "8") (name "3V3_PIN4") (class "Default")
      (node (ref "IC12") (pin "6") (pinfunction "6_6") (pintype "bidirectional"))
      (node (ref "IC6") (pin "56") (pinfunction "DIFFIO_TX_RX_B12P/DIFFOUT_B12P_56") (pintype "bidirectional"))
    )
    (net (code "9") (name "3V3_PIN5~{}") (class "Default")
      (node (ref "IC12") (pin "7") (pinfunction "7_7") (pintype "bidirectional"))
      (node (ref "IC6") (pin "57") (pinfunction "DIFFIO_TX_RX_B14N/DIFFOUT_B14N_57") (pintype "bidirectional"))
    )
    (net (code "10") (name "3V3_PIN6~{}") (class "Default")
      (node (ref "IC12") (pin "8") (pinfunction "8_8") (pintype "bidirectional"))
      (node (ref "IC6") (pin "58") (pinfunction "DIFFIO_TX_RX_B14P/DIFFOUT_B14P_58") (pintype "bidirectional"))
    )
    (net (code "11") (name "3V3_PIN7") (class "Default")
      (node (ref "IC12") (pin "9") (pinfunction "9_9") (pintype "bidirectional"))
      (node (ref "IC6") (pin "59") (pinfunction "DIFFIO_TX_RX_B16N/DIFFOUT_B16N_59") (pintype "bidirectional"))
    )
    (net (code "12") (name "3V3_PIN8") (class "Default")
      (node (ref "IC13") (pin "1") (pinfunction "1_1") (pintype "bidirectional"))
      (node (ref "IC6") (pin "92") (pinfunction "DIFFIO_RX_R18P/DIFFOUT_R18P_92") (pintype "bidirectional"))
    )
    (net (code "13") (name "3V3_PIN9~{}") (class "Default")
      (node (ref "IC13") (pin "3") (pinfunction "3_3") (pintype "bidirectional"))
      (node (ref "IC6") (pin "93") (pinfunction "DIFFIO_RX_R18N/DIFFOUT_R18N_93") (pintype "bidirectional"))
    )
    (net (code "14") (name "3V3_PIN10~{}") (class "Default")
      (node (ref "IC13") (pin "4") (pinfunction "4_4") (pintype "bidirectional"))
      (node (ref "IC6") (pin "96") (pinfunction "DPCLK3/DIFFIO_RX_R26P/DIFFOUT_R26P_96") (pintype "bidirectional"))
    )
    (net (code "15") (name "3V3_PIN11~{}") (class "Default")
      (node (ref "IC13") (pin "5") (pinfunction "5_5") (pintype "bidirectional"))
      (node (ref "IC6") (pin "98") (pinfunction "DPCLK2/DIFFIO_RX_R26N/DIFFOUT_R26N_98") (pintype "bidirectional"))
    )
    (net (code "16") (name "3V3_PIN12") (class "Default")
      (node (ref "IC13") (pin "6") (pinfunction "6_6") (pintype "bidirectional"))
      (node (ref "IC6") (pin "99") (pinfunction "DIFFIO_RX_R27P/DIFFOUT_R27P_99") (pintype "bidirectional"))
    )
    (net (code "17") (name "3V3_PIN13") (class "Default")
      (node (ref "IC13") (pin "7") (pinfunction "7_7") (pintype "bidirectional"))
      (node (ref "IC6") (pin "100") (pinfunction "DIFFIO_RX_R28P/DIFFOUT_R28P_100") (pintype "bidirectional"))
    )
    (net (code "18") (name "3V3_SCL") (class "Default")
      (node (ref "IC13") (pin "9") (pinfunction "9_9") (pintype "bidirectional"))
      (node (ref "IC6") (pin "102") (pinfunction "DIFFIO_RX_R28N/DIFFOUT_R28N_102") (pintype "bidirectional"))
    )
    (net (code "19") (name "3V3_SDA") (class "Default")
      (node (ref "IC13") (pin "8") (pinfunction "8_8") (pintype "bidirectional"))
      (node (ref "IC6") (pin "101") (pinfunction "DIFFIO_RX_R27N/DIFFOUT_R27N_101") (pintype "bidirectional"))
    )
    (net (code "20") (name "5V_FLT") (class "Default")
      (node (ref "F3") (pin "1") (pinfunction "1_1") (pintype "passive"))
      (node (ref "IC7") (pin "8") (pinfunction "VDD_8") (pintype "input"))
      (node (ref "IC8") (pin "4") (pinfunction "4_4") (pintype "input"))
    )
    (net (code "21") (name "A0") (class "Default")
      (node (ref "J11") (pin "A0") (pinfunction "A0_A0") (pintype "bidirectional"))
      (node (ref "R11") (pin "P$1") (pinfunction "1_P$1") (pintype "passive"))
    )
    (net (code "22") (name "A1") (class "Default")
      (node (ref "J11") (pin "A1") (pinfunction "A1_A1") (pintype "bidirectional"))
      (node (ref "R12") (pin "P$1") (pinfunction "1_P$1") (pintype "passive"))
    )
    (net (code "23") (name "A2") (class "Default")
      (node (ref "J11") (pin "A2") (pinfunction "A2_A2") (pintype "bidirectional"))
      (node (ref "R14") (pin "P$1") (pinfunction "1_P$1") (pintype "passive"))
    )
    (net (code "24") (name "A3") (class "Default")
      (node (ref "J11") (pin "A3") (pinfunction "A3_A3") (pintype "bidirectional"))
      (node (ref "R16") (pin "P$1") (pinfunction "1_P$1") (pintype "passive"))
    )
    (net (code "25") (name "A4") (class "Default")
      (node (ref "J11") (pin "A4") (pinfunction "A4_A4") (pintype "bidirectional"))
      (node (ref "R20") (pin "P$1") (pinfunction "1_P$1") (pintype "passive"))
    )
    (net (code "26") (name "A5") (class "Default")
      (node (ref "J11") (pin "A5") (pinfunction "A5_A5") (pintype "bidirectional"))
      (node (ref "R18") (pin "P$1") (pinfunction "1_P$1") (pintype "passive"))
    )
    (net (code "27") (name "ADC_IN0") (class "Default")
      (node (ref "IC7") (pin "1") (pinfunction "1_1") (pintype "output"))
      (node (ref "IC7") (pin "2") (pinfunction "2_2") (pintype "input"))
      (node (ref "R23") (pin "P$1") (pinfunction "1_P$1") (pintype "passive"))
    )
    (net (code "28") (name "ADC_IN1") (class "Default")
      (node (ref "IC7") (pin "6") (pinfunction "6_6") (pintype "input"))
      (node (ref "IC7") (pin "7") (pinfunction "7_7") (pintype "output"))
      (node (ref "R24") (pin "P$1") (pinfunction "1_P$1") (pintype "passive"))
    )
    (net (code "29") (name "ADC_IN2") (class "Default")
      (node (ref "IC8") (pin "1") (pinfunction "1_1") (pintype "output"))
      (node (ref "IC8") (pin "2") (pinfunction "2_2") (pintype "input"))
      (node (ref "R25") (pin "P$1") (pinfunction "1_P$1") (pintype "passive"))
    )
    (net (code "30") (name "ADC_IN3") (class "Default")
      (node (ref "IC8") (pin "6") (pinfunction "6_6") (pintype "input"))
      (node (ref "IC8") (pin "7") (pinfunction "7_7") (pintype "output"))
      (node (ref "R26") (pin "P$1") (pinfunction "1_P$1") (pintype "passive"))
    )
    (net (code "31") (name "ADC_IN4") (class "Default")
      (node (ref "IC8") (pin "13") (pinfunction "13_13") (pintype "input"))
      (node (ref "IC8") (pin "14") (pinfunction "14_14") (pintype "output"))
      (node (ref "R27") (pin "P$2") (pinfunction "2_P$2") (pintype "passive"))
    )
    (net (code "32") (name "ADC_IN5") (class "Default")
      (node (ref "IC8") (pin "8") (pinfunction "8_8") (pintype "output"))
      (node (ref "IC8") (pin "9") (pinfunction "9_9") (pintype "input"))
      (node (ref "R28") (pin "P$2") (pinfunction "2_P$2") (pintype "passive"))
    )
    (net (code "33") (name "AGND_CODEC") (class "Default")
      (node (ref "C25") (pin "P$2") (pinfunction "2_P$2") (pintype "passive"))
      (node (ref "F2") (pin "2") (pinfunction "2_2") (pintype "passive"))
      (node (ref "J4") (pin "5") (pinfunction "5_5") (pintype "passive"))
      (node (ref "MIC1") (pin "1") (pinfunction "2_1") (pintype "input"))
    )
    (net (code "34") (name "AGND_FPGA") (class "Default")
      (node (ref "C12") (pin "2") (pinfunction "2_2") (pintype "passive"))
      (node (ref "C13") (pin "2") (pinfunction "2_2") (pintype "passive"))
      (node (ref "C14") (pin "2") (pinfunction "2_2") (pintype "passive"))
      (node (ref "C15") (pin "2") (pinfunction "2_2") (pintype "passive"))
      (node (ref "C16") (pin "2") (pinfunction "2_2") (pintype "passive"))
      (node (ref "C17") (pin "2") (pinfunction "2_2") (pintype "passive"))
      (node (ref "C19") (pin "P$2") (pinfunction "2_P$2") (pintype "passive"))
      (node (ref "C20") (pin "P$2") (pinfunction "2_P$2") (pintype "passive"))
      (node (ref "C21") (pin "P$2") (pinfunction "2_P$2") (pintype "passive"))
      (node (ref "C22") (pin "P$2") (pinfunction "2_P$2") (pintype "passive"))
      (node (ref "C23") (pin "P$2") (pinfunction "2_P$2") (pintype "passive"))
      (node (ref "C24") (pin "P$2") (pinfunction "2_P$2") (pintype "passive"))
      (node (ref "F7") (pin "1") (pinfunction "1_1") (pintype "passive"))
      (node (ref "F8") (pin "2") (pinfunction "2_2") (pintype "passive"))
      (node (ref "IC6") (pin "13") (pinfunction "DIFFIO_RX_L7N/DIFFOUT_L7N/ADC1IN7_13") (pintype "bidirectional"))
      (node (ref "IC6") (pin "14") (pinfunction "DIFFIO_RX_L7P/DIFFOUT_L7P/ADC1IN8_14") (pintype "bidirectional"))
      (node (ref "IC6") (pin "3") (pinfunction "ANAIN1_3") (pintype "input"))
      (node (ref "IC7") (pin "4") (pinfunction "VSS_4") (pintype "input"))
      (node (ref "IC8") (pin "11") (pinfunction "11_11") (pintype "input"))
      (node (ref "PT1") (pin "1E") (pinfunction "1E_1E") (pintype "passive"))
      (node (ref "PT1") (pin "1S") (pinfunction "1S_1S") (pintype "passive"))
      (node (ref "R13") (pin "P$2") (pinfunction "2_P$2") (pintype "passive"))
      (node (ref "R15") (pin "P$1") (pinfunction "1_P$1") (pintype "passive"))
      (node (ref "R17") (pin "P$1") (pinfunction "1_P$1") (pintype "passive"))
      (node (ref "R19") (pin "P$2") (pinfunction "2_P$2") (pintype "passive"))
      (node (ref "R21") (pin "P$1") (pinfunction "1_P$1") (pintype "passive"))
    )
    (net (code "35") (name "AREF") (class "Default")
      (node (ref "IC6") (pin "5") (pinfunction "ADC_REF_5") (pintype "input"))
      (node (ref "J8") (pin "AREF") (pinfunction "AREF_AREF") (pintype "bidirectional"))
    )
    (net (code "36") (name "CODEC_FSYNC_N") (class "Default")
      (node (ref "IC3") (pin "6") (pinfunction "FSYNC_N_6") (pintype "bidirectional"))
      (node (ref "IC6") (pin "43") (pinfunction "DIFFIO_TX_RX_B3P/DIFFOUT_B3P_43") (pintype "bidirectional"))
    )
    (net (code "37") (name "CODEC_MCLK") (class "Default")
      (node (ref "IC3") (pin "7") (pinfunction "MCLK_7") (pintype "input"))
      (node (ref "IC6") (pin "41") (pinfunction "DIFFIO_TX_RX_B3N/DIFFOUT_B3N_41") (pintype "bidirectional"))
    )
    (net (code "38") (name "CODEC_RESET_N") (class "Default")
      (node (ref "IC3") (pin "9") (pinfunction "RESET_N_9") (pintype "input"))
      (node (ref "IC6") (pin "39") (pinfunction "DIFFIO_TX_RX_B1P/DIFFOUT_B1P_39") (pintype "bidirectional"))
    )
    (net (code "39") (name "CODEC_SCLK") (class "Default")
      (node (ref "IC3") (pin "8") (pinfunction "SCLK_8") (pintype "bidirectional"))
      (node (ref "IC6") (pin "38") (pinfunction "DIFFIO_TX_RX_B1N/DIFFOUT_B1N_38") (pintype "bidirectional"))
    )
    (net (code "40") (name "CODEC_SDI") (class "Default")
      (node (ref "IC3") (pin "4") (pinfunction "SDI_4") (pintype "input"))
      (node (ref "IC6") (pin "45") (pinfunction "DIFFIO_TX_RX_B5P/DIFFOUT_B5P_45") (pintype "bidirectional"))
    )
    (net (code "41") (name "CODEC_SDO") (class "Default")
      (node (ref "IC3") (pin "5") (pinfunction "SDO_5") (pintype "output"))
      (node (ref "IC6") (pin "44") (pinfunction "DIFFIO_TX_RX_B5N/DIFFOUT_B5N_44") (pintype "bidirectional"))
    )
    (net (code "42") (name "FT232R_CTS_N") (class "Default")
      (node (ref "IC5") (pin "11") (pinfunction "~{CTS}_11") (pintype "input"))
      (node (ref "IC6") (pin "81") (pinfunction "DIFFIO_RX_R7N/DIFFOUT_R7N_81") (pintype "bidirectional"))
    )
    (net (code "43") (name "FT232R_RESET_N") (class "Default")
      (node (ref "IC5") (pin "19") (pinfunction "~{RESET}_19") (pintype "input"))
      (node (ref "IC6") (pin "84") (pinfunction "DIFFIO_RX_R11P/DIFFOUT_R11P_84") (pintype "bidirectional"))
    )
    (net (code "44") (name "FT232R_RTS_N") (class "Default")
      (node (ref "IC5") (pin "3") (pinfunction "~{RTS}_3") (pintype "output"))
      (node (ref "IC6") (pin "76") (pinfunction "DIFFIO_RX_R2N/DIFFOUT_R2N_76") (pintype "bidirectional"))
    )
    (net (code "45") (name "FT232R_RXD") (class "Default")
      (node (ref "IC5") (pin "5") (pinfunction "RXD_5") (pintype "input"))
      (node (ref "IC6") (pin "79") (pinfunction "DIFFIO_RX_R7P/DIFFOUT_R7P_79") (pintype "bidirectional"))
    )
    (net (code "46") (name "FT232R_RXLED_N") (class "Default")
      (node (ref "IC5") (pin "22") (pinfunction "CBUS1_22") (pintype "bidirectional"))
      (node (ref "UART_TX") (pin "C") (pinfunction "C_C") (pintype "passive"))
    )
    (net (code "47") (name "FT232R_TXD") (class "Default")
      (node (ref "IC5") (pin "1") (pinfunction "TXD_1") (pintype "output"))
      (node (ref "IC6") (pin "75") (pinfunction "DIFFIO_RX_R1P/DIFFOUT_R1P_75") (pintype "bidirectional"))
    )
    (net (code "48") (name "FT232R_TXLED_N") (class "Default")
      (node (ref "IC5") (pin "23") (pinfunction "CBUS0_23") (pintype "bidirectional"))
      (node (ref "UART_RX") (pin "C") (pinfunction "C_C") (pintype "passive"))
    )
    (net (code "49") (name "GND") (class "Default")
      (node (ref "C1") (pin "-") (pinfunction "-_-") (pintype "passive"))
      (node (ref "C10") (pin "2") (pinfunction "2_2") (pintype "passive"))
      (node (ref "C11") (pin "2") (pinfunction "2_2") (pintype "passive"))
      (node (ref "C18") (pin "2") (pinfunction "2_2") (pintype "passive"))
      (node (ref "C2") (pin "-") (pinfunction "-_-") (pintype "passive"))
      (node (ref "C26") (pin "-") (pinfunction "-_-") (pintype "passive"))
      (node (ref "C5") (pin "-") (pinfunction "-_-") (pintype "passive"))
      (node (ref "C9") (pin "-") (pinfunction "-_-") (pintype "passive"))
      (node (ref "F2") (pin "1") (pinfunction "1_1") (pintype "passive"))
      (node (ref "F8") (pin "1") (pinfunction "1_1") (pintype "passive"))
      (node (ref "IC1") (pin "1") (pinfunction "1_1") (pintype "input"))
      (node (ref "IC10") (pin "4") (pinfunction "VSS_4") (pintype "input"))
      (node (ref "IC11") (pin "6") (pinfunction "VSS_6") (pintype "input"))
      (node (ref "IC12") (pin "11") (pinfunction "11_11") (pintype "input"))
      (node (ref "IC13") (pin "11") (pinfunction "11_11") (pintype "input"))
      (node (ref "IC2") (pin "2") (pinfunction "GND_2") (pintype "input"))
      (node (ref "IC3") (pin "14") (pinfunction "GND_14") (pintype "input"))
      (node (ref "IC4") (pin "2") (pinfunction "V-_2") (pintype "input"))
      (node (ref "IC5") (pin "18") (pinfunction "GND_18") (pintype "power_in"))
      (node (ref "IC5") (pin "21") (pinfunction "GND_21") (pintype "power_in"))
      (node (ref "IC5") (pin "25") (pinfunction "GND_25") (pintype "power_in"))
      (node (ref "IC5") (pin "26") (pinfunction "TEST_26") (pintype "input"))
      (node (ref "IC5") (pin "7") (pinfunction "GND_7") (pintype "power_in"))
      (node (ref "IC6") (pin "104") (pinfunction "GND12_104") (pintype "input"))
      (node (ref "IC6") (pin "116") (pinfunction "GND11_116") (pintype "input"))
      (node (ref "IC6") (pin "125") (pinfunction "GND10_125") (pintype "input"))
      (node (ref "IC6") (pin "133") (pinfunction "GND9_133") (pintype "input"))
      (node (ref "IC6") (pin "137") (pinfunction "GND8_137") (pintype "input"))
      (node (ref "IC6") (pin "142") (pinfunction "GND7_142") (pintype "input"))
      (node (ref "IC6") (pin "42") (pinfunction "GND6_42") (pintype "input"))
      (node (ref "IC6") (pin "53") (pinfunction "GND5_53") (pintype "input"))
      (node (ref "IC6") (pin "63") (pinfunction "GND4_63") (pintype "input"))
      (node (ref "IC6") (pin "68") (pinfunction "GND3_68") (pintype "input"))
      (node (ref "IC6") (pin "83") (pinfunction "GND13_83") (pintype "input"))
      (node (ref "IC6") (pin "95") (pinfunction "GND1_95") (pintype "input"))
      (node (ref "IC9") (pin "4") (pinfunction "GND_4") (pintype "input"))
      (node (ref "J1") (pin "2") (pinfunction "2_2") (pintype "passive"))
      (node (ref "J10") (pin "GND.") (pinfunction "GND._GND.") (pintype "bidirectional"))
      (node (ref "J10") (pin "GND..") (pinfunction "GND.._GND..") (pintype "bidirectional"))
      (node (ref "J2") (pin "4") (pinfunction "4_4") (pintype "passive"))
      (node (ref "J2") (pin "5") (pinfunction "5_5") (pintype "passive"))
      (node (ref "J7") (pin "10") (pinfunction "10_10") (pintype "passive"))
      (node (ref "J7") (pin "2") (pinfunction "2_2") (pintype "passive"))
      (node (ref "J8") (pin "GND") (pinfunction "GND_GND") (pintype "bidirectional"))
      (node (ref "JP2") (pin "2") (pinfunction "2_2") (pintype "passive"))
      (node (ref "JP6") (pin "2") (pinfunction "2_2") (pintype "passive"))
      (node (ref "LED_IOREF") (pin "C") (pinfunction "C_C") (pintype "passive"))
      (node (ref "R3") (pin "P$1") (pinfunction "1_P$1") (pintype "passive"))
      (node (ref "R39") (pin "P$1") (pinfunction "1_P$1") (pintype "passive"))
      (node (ref "R8") (pin "P$1") (pinfunction "1_P$1") (pintype "passive"))
      (node (ref "SW1") (pin "3") (pinfunction "3_3") (pintype "bidirectional"))
      (node (ref "SW1") (pin "4") (pinfunction "4_4") (pintype "bidirectional"))
      (node (ref "SW2") (pin "3") (pinfunction "3_3") (pintype "bidirectional"))
      (node (ref "SW2") (pin "4") (pinfunction "4_4") (pintype "bidirectional"))
    )
    (net (code "50") (name "IOREF") (class "Default")
      (node (ref "C18") (pin "1") (pinfunction "1_1") (pintype "passive"))
      (node (ref "IC12") (pin "19") (pinfunction "19_19") (pintype "input"))
      (node (ref "IC13") (pin "19") (pinfunction "19_19") (pintype "input"))
      (node (ref "J10") (pin "I/OREF") (pinfunction "IOREF_I/OREF") (pintype "bidirectional"))
      (node (ref "JP1") (pin "2") (pinfunction "2_2") (pintype "passive"))
      (node (ref "R22") (pin "P$2") (pinfunction "2_P$2") (pintype "passive"))
    )
    (net (code "51") (name "JTAGEN") (class "Default")
      (node (ref "IC6") (pin "15") (pinfunction "JTAGEN_15") (pintype "bidirectional"))
      (node (ref "JP2") (pin "1") (pinfunction "1_1") (pintype "passive"))
      (node (ref "R33") (pin "P$2") (pinfunction "2_P$2") (pintype "passive"))
    )
    (net (code "52") (name "JTAG_PIN6") (class "Default")
      (node (ref "IC6") (pin "46") (pinfunction "DIFFIO_TX_RX_B7N/DIFFOUT_B7N_46") (pintype "bidirectional"))
      (node (ref "J7") (pin "6") (pinfunction "6_6") (pintype "passive"))
    )
    (net (code "53") (name "JTAG_PIN7") (class "Default")
      (node (ref "IC6") (pin "60") (pinfunction "DIFFIO_TX_RX_B16P/DIFFOUT_B16P_60") (pintype "bidirectional"))
      (node (ref "J7") (pin "7") (pinfunction "7_7") (pintype "passive"))
    )
    (net (code "54") (name "JTAG_PIN8") (class "Default")
      (node (ref "IC6") (pin "47") (pinfunction "DIFFIO_TX_RX_B7P/DIFFOUT_B7P_47") (pintype "bidirectional"))
      (node (ref "J7") (pin "8") (pinfunction "8_8") (pintype "passive"))
    )
    (net (code "55") (name "MICRO_SD_CD_DAT3") (class "Default")
      (node (ref "IC11") (pin "2") (pinfunction "CD/DAT3_2") (pintype "bidirectional"))
      (node (ref "IC6") (pin "69") (pinfunction "DIFFIO_TX_RX_B27N/DIFFOUT_B27N_69") (pintype "bidirectional"))
    )
    (net (code "56") (name "MICRO_SD_CLK") (class "Default")
      (node (ref "IC11") (pin "5") (pinfunction "CLK_5") (pintype "bidirectional"))
      (node (ref "IC6") (pin "65") (pinfunction "DIFFIO_TX_RX_B23P/DIFFOUT_B23P_65") (pintype "bidirectional"))
    )
    (net (code "57") (name "MICRO_SD_CMD") (class "Default")
      (node (ref "IC11") (pin "3") (pinfunction "CMD_3") (pintype "bidirectional"))
      (node (ref "IC6") (pin "66") (pinfunction "IO66_66") (pintype "bidirectional"))
    )
    (net (code "58") (name "MICRO_SD_DAT0") (class "Default")
      (node (ref "IC11") (pin "7") (pinfunction "DAT0_7") (pintype "bidirectional"))
      (node (ref "IC6") (pin "64") (pinfunction "DIFFIO_TX_RX_B23N/DIFFOUT_B23N_64") (pintype "bidirectional"))
    )
    (net (code "59") (name "MICRO_SD_DAT1") (class "Default")
      (node (ref "IC11") (pin "8") (pinfunction "DAT1_8") (pintype "bidirectional"))
      (node (ref "IC6") (pin "62") (pinfunction "IO62_62") (pintype "bidirectional"))
    )
    (net (code "60") (name "MICRO_SD_DAT2") (class "Default")
      (node (ref "IC11") (pin "1") (pinfunction "DAT2_1") (pintype "bidirectional"))
      (node (ref "IC6") (pin "70") (pinfunction "DIFFIO_TX_RX_B27P/DIFFOUT_B27P_70") (pintype "bidirectional"))
    )
    (net (code "61") (name "Net-(C6-1)") (class "Default")
      (node (ref "C6") (pin "P$1") (pinfunction "1_P$1") (pintype "passive"))
      (node (ref "IC3") (pin "16") (pinfunction "SPKRL_16") (pintype "output"))
    )
    (net (code "62") (name "Net-(C6-2)") (class "Default")
      (node (ref "C6") (pin "P$2") (pinfunction "2_P$2") (pintype "passive"))
      (node (ref "R6") (pin "P$2") (pinfunction "2_P$2") (pintype "passive"))
    )
    (net (code "63") (name "Net-(C7-1)") (class "Default")
      (node (ref "C7") (pin "P$1") (pinfunction "1_P$1") (pintype "passive"))
      (node (ref "IC3") (pin "1") (pinfunction "SPKRR_1") (pintype "output"))
    )
    (net (code "64") (name "Net-(C7-2)") (class "Default")
      (node (ref "C7") (pin "P$2") (pinfunction "2_P$2") (pintype "passive"))
      (node (ref "R29") (pin "P$2") (pinfunction "2_P$2") (pintype "passive"))
    )
    (net (code "65") (name "Net-(C19-1)") (class "Default")
      (node (ref "C19") (pin "P$1") (pinfunction "1_P$1") (pintype "passive"))
      (node (ref "IC6") (pin "6") (pinfunction "DIFFIO_RX_L1N/DIFFOUT_L1N/ADC1IN1_6") (pintype "bidirectional"))
      (node (ref "R23") (pin "P$2") (pinfunction "2_P$2") (pintype "passive"))
    )
    (net (code "66") (name "Net-(C20-1)") (class "Default")
      (node (ref "C20") (pin "P$1") (pinfunction "1_P$1") (pintype "passive"))
      (node (ref "IC6") (pin "7") (pinfunction "DIFFIO_RX_L1P/DIFFOUT_L1P/ADC1IN2_7") (pintype "bidirectional"))
      (node (ref "R24") (pin "P$2") (pinfunction "2_P$2") (pintype "passive"))
    )
    (net (code "67") (name "Net-(C21-1)") (class "Default")
      (node (ref "C21") (pin "P$1") (pinfunction "1_P$1") (pintype "passive"))
      (node (ref "IC6") (pin "8") (pinfunction "DIFFIO_RX_L3N/DIFFOUT_L3N/ADC1IN3_8") (pintype "bidirectional"))
      (node (ref "R25") (pin "P$2") (pinfunction "2_P$2") (pintype "passive"))
    )
    (net (code "68") (name "Net-(C22-1)") (class "Default")
      (node (ref "C22") (pin "P$1") (pinfunction "1_P$1") (pintype "passive"))
      (node (ref "IC6") (pin "10") (pinfunction "DIFFIO_RX_L3P/DIFFOUT_L3P/ADC1IN4_10") (pintype "bidirectional"))
      (node (ref "R26") (pin "P$2") (pinfunction "2_P$2") (pintype "passive"))
    )
    (net (code "69") (name "Net-(C23-1)") (class "Default")
      (node (ref "C23") (pin "P$1") (pinfunction "1_P$1") (pintype "passive"))
      (node (ref "IC6") (pin "11") (pinfunction "DIFFIO_RX_L5N/DIFFOUT_L5N/ADC1IN5_11") (pintype "bidirectional"))
      (node (ref "R27") (pin "P$1") (pinfunction "1_P$1") (pintype "passive"))
    )
    (net (code "70") (name "Net-(C24-1)") (class "Default")
      (node (ref "C24") (pin "P$1") (pinfunction "1_P$1") (pintype "passive"))
      (node (ref "IC6") (pin "12") (pinfunction "DIFFIO_RX_L5P/DIFFOUT_L5P/ADC1IN6_12") (pintype "bidirectional"))
      (node (ref "R28") (pin "P$1") (pinfunction "1_P$1") (pintype "passive"))
    )
    (net (code "71") (name "Net-(D1-Pad2)") (class "Default")
      (node (ref "D1") (pin "2") (pinfunction "2_2") (pintype "passive"))
      (node (ref "J1") (pin "1") (pinfunction "1_1") (pintype "passive"))
    )
    (net (code "72") (name "Net-(F1-Pad1)") (class "Default")
      (node (ref "F1") (pin "1") (pinfunction "1_1") (pintype "passive"))
      (node (ref "J2") (pin "1") (pinfunction "1_1") (pintype "passive"))
    )
    (net (code "73") (name "Net-(IC2-EN)") (class "Default")
      (node (ref "IC2") (pin "1") (pinfunction "EN_1") (pintype "input"))
      (node (ref "R1") (pin "P$2") (pinfunction "2_P$2") (pintype "passive"))
    )
    (net (code "74") (name "Net-(IC2-FB)") (class "Default")
      (node (ref "C4") (pin "2") (pinfunction "2_2") (pintype "passive"))
      (node (ref "IC2") (pin "5") (pinfunction "FB_5") (pintype "passive"))
      (node (ref "R2") (pin "P$1") (pinfunction "1_P$1") (pintype "passive"))
      (node (ref "R3") (pin "P$2") (pinfunction "2_P$2") (pintype "passive"))
    )
    (net (code "75") (name "Net-(IC2-LX)") (class "Default")
      (node (ref "IC2") (pin "3") (pinfunction "LX_3") (pintype "input"))
      (node (ref "L1") (pin "1") (pinfunction "1_1") (pintype "passive"))
    )
    (net (code "76") (name "Net-(IC3-MBIAS)") (class "Default")
      (node (ref "IC3") (pin "2") (pinfunction "MBIAS_2") (pintype "output"))
      (node (ref "R5") (pin "P$1") (pinfunction "1_P$1") (pintype "passive"))
    )
    (net (code "77") (name "Net-(IC3-MIC)") (class "Default")
      (node (ref "C3") (pin "1") (pinfunction "1_1") (pintype "passive"))
      (node (ref "IC3") (pin "10") (pinfunction "MIC_10") (pintype "input"))
    )
    (net (code "78") (name "Net-(IC4-+IN)") (class "Default")
      (node (ref "IC4") (pin "1") (pinfunction "+IN_1") (pintype "input"))
      (node (ref "R7") (pin "P$1") (pinfunction "1_P$1") (pintype "passive"))
      (node (ref "R8") (pin "P$2") (pinfunction "2_P$2") (pintype "passive"))
    )
    (net (code "79") (name "Net-(IC4-OUT)") (class "Default")
      (node (ref "IC4") (pin "4") (pinfunction "OUT_4") (pintype "output"))
      (node (ref "PMOS1") (pin "3") (pinfunction "G_3") (pintype "passive"))
    )
    (net (code "80") (name "Net-(IC5-3V3OUT)") (class "Default")
      (node (ref "C11") (pin "1") (pinfunction "1_1") (pintype "passive"))
      (node (ref "IC5") (pin "17") (pinfunction "3V3OUT_17") (pintype "output"))
      (node (ref "IC5") (pin "4") (pinfunction "VCCIO_4") (pintype "power_in"))
      (node (ref "R10") (pin "P$2") (pinfunction "2_P$2") (pintype "passive"))
      (node (ref "R9") (pin "P$2") (pinfunction "2_P$2") (pintype "passive"))
    )
    (net (code "81") (name "Net-(IC5-USBDM)") (class "Default")
      (node (ref "IC5") (pin "16") (pinfunction "USBDM_16") (pintype "bidirectional"))
      (node (ref "J2") (pin "2") (pinfunction "2_2") (pintype "passive"))
    )
    (net (code "82") (name "Net-(IC5-USBDP)") (class "Default")
      (node (ref "IC5") (pin "15") (pinfunction "USBDP_15") (pintype "bidirectional"))
      (node (ref "J2") (pin "3") (pinfunction "3_3") (pintype "passive"))
    )
    (net (code "83") (name "Net-(IC6A-REFGND{slash}GND2)") (class "Default")
      (node (ref "F7") (pin "2") (pinfunction "2_2") (pintype "passive"))
      (node (ref "IC6") (pin "4") (pinfunction "REFGND/GND2_4") (pintype "input"))
    )
    (net (code "84") (name "Net-(IC6A-VCCA4)") (class "Default")
      (node (ref "F5") (pin "2") (pinfunction "2_2") (pintype "passive"))
      (node (ref "IC6") (pin "143") (pinfunction "VCCA4_143") (pintype "input"))
      (node (ref "IC6") (pin "2") (pinfunction "VCCA6_2") (pintype "input"))
    )
    (net (code "85") (name "Net-(IC6B-VCCIO1A)") (class "Default")
      (node (ref "F4") (pin "2") (pinfunction "2_2") (pintype "passive"))
      (node (ref "IC6") (pin "9") (pinfunction "VCCIO1A_9") (pintype "input"))
    )
    (net (code "86") (name "Net-(IC6G-DIFFIO_RX_R10P{slash}DIFFOUT_R10P)") (class "Default")
      (node (ref "IC6") (pin "85") (pinfunction "DIFFIO_RX_R10P/DIFFOUT_R10P_85") (pintype "bidirectional"))
      (node (ref "SW2") (pin "1") (pinfunction "1_1") (pintype "bidirectional"))
      (node (ref "SW2") (pin "2") (pinfunction "2_2") (pintype "bidirectional"))
    )
    (net (code "87") (name "Net-(IC6H-CLK2P{slash}DIFFIO_RX_R14P{slash}DIFFOUT_R14P)") (class "Default")
      (node (ref "IC6") (pin "88") (pinfunction "CLK2P/DIFFIO_RX_R14P/DIFFOUT_R14P_88") (pintype "bidirectional"))
      (node (ref "IC9") (pin "5") (pinfunction "OUT_5") (pintype "output"))
    )
    (net (code "88") (name "Net-(IC6J-CONFIG_SEL)") (class "Default")
      (node (ref "IC6") (pin "126") (pinfunction "CONFIG_SEL_126") (pintype "bidirectional"))
      (node (ref "JP6") (pin "1") (pinfunction "1_1") (pintype "passive"))
      (node (ref "R40") (pin "P$2") (pinfunction "2_P$2") (pintype "passive"))
    )
    (net (code "89") (name "Net-(IC6J-CONF_DONE{slash}DIFFIO_RX_T24N{slash}DIFFOUT_T24N)") (class "Default")
      (node (ref "IC6") (pin "138") (pinfunction "CONF_DONE/DIFFIO_RX_T24N/DIFFOUT_T24N_138") (pintype "bidirectional"))
      (node (ref "R38") (pin "P$1") (pinfunction "1_P$1") (pintype "passive"))
    )
    (net (code "90") (name "Net-(IC6J-DEV_CLRN{slash}DIFFIO_RX_T16N{slash}DIFFOUT_T16N)") (class "Default")
      (node (ref "IC6") (pin "121") (pinfunction "DEV_CLRN/DIFFIO_RX_T16N/DIFFOUT_T16N_121") (pintype "bidirectional"))
      (node (ref "R41") (pin "P$2") (pinfunction "2_P$2") (pintype "passive"))
    )
    (net (code "91") (name "Net-(IC6J-DIFFIO_RX_T20N{slash}DIFFOUT_T20N)") (class "Default")
      (node (ref "IC6") (pin "131") (pinfunction "DIFFIO_RX_T20N/DIFFOUT_T20N_131") (pintype "bidirectional"))
      (node (ref "LED2") (pin "C") (pinfunction "C_C") (pintype "passive"))
    )
    (net (code "92") (name "Net-(IC6J-DIFFIO_RX_T20P{slash}DIFFOUT_T20P)") (class "Default")
      (node (ref "IC6") (pin "130") (pinfunction "DIFFIO_RX_T20P/DIFFOUT_T20P_130") (pintype "bidirectional"))
      (node (ref "LED1") (pin "C") (pinfunction "C_C") (pintype "passive"))
    )
    (net (code "93") (name "Net-(IC6J-DIFFIO_RX_T22P{slash}DIFFOUT_T22P)") (class "Default")
      (node (ref "IC6") (pin "132") (pinfunction "DIFFIO_RX_T22P/DIFFOUT_T22P_132") (pintype "bidirectional"))
      (node (ref "LED3") (pin "C") (pinfunction "C_C") (pintype "passive"))
    )
    (net (code "94") (name "Net-(IC6J-NCONFIG)") (class "Default")
      (node (ref "IC6") (pin "129") (pinfunction "NCONFIG_129") (pintype "input"))
      (node (ref "R36") (pin "P$2") (pinfunction "2_P$2") (pintype "passive"))
    )
    (net (code "95") (name "Net-(IC6J-NSTATUS{slash}DIFFIO_RX_T24P{slash}DIFFOUT_T24P)") (class "Default")
      (node (ref "IC6") (pin "136") (pinfunction "NSTATUS/DIFFIO_RX_T24P/DIFFOUT_T24P_136") (pintype "bidirectional"))
      (node (ref "R37") (pin "P$1") (pinfunction "1_P$1") (pintype "passive"))
    )
    (net (code "96") (name "Net-(MIC1-1)") (class "Default")
      (node (ref "C3") (pin "2") (pinfunction "2_2") (pintype "passive"))
      (node (ref "MIC1") (pin "2") (pinfunction "1_2") (pintype "input"))
      (node (ref "R5") (pin "P$2") (pinfunction "2_P$2") (pintype "passive"))
    )
    (net (code "97") (name "Net-(R6-1)") (class "Default")
      (node (ref "J4") (pin "1") (pinfunction "1_1") (pintype "passive"))
      (node (ref "R6") (pin "P$1") (pinfunction "1_P$1") (pintype "passive"))
    )
    (net (code "98") (name "Net-(R9-1)") (class "Default")
      (node (ref "R9") (pin "P$1") (pinfunction "1_P$1") (pintype "passive"))
      (node (ref "UART_RX") (pin "A") (pinfunction "A_A") (pintype "passive"))
    )
    (net (code "99") (name "Net-(R10-1)") (class "Default")
      (node (ref "R10") (pin "P$1") (pinfunction "1_P$1") (pintype "passive"))
      (node (ref "UART_TX") (pin "A") (pinfunction "A_A") (pintype "passive"))
    )
    (net (code "100") (name "Net-(R11-2)") (class "Default")
      (node (ref "C12") (pin "1") (pinfunction "1_1") (pintype "passive"))
      (node (ref "IC7") (pin "3") (pinfunction "3_3") (pintype "input"))
      (node (ref "PT1") (pin "1A") (pinfunction "1A_1A") (pintype "passive"))
      (node (ref "R11") (pin "P$2") (pinfunction "2_P$2") (pintype "passive"))
    )
    (net (code "101") (name "Net-(R12-2)") (class "Default")
      (node (ref "C13") (pin "1") (pinfunction "1_1") (pintype "passive"))
      (node (ref "IC7") (pin "5") (pinfunction "5_5") (pintype "input"))
      (node (ref "R12") (pin "P$2") (pinfunction "2_P$2") (pintype "passive"))
      (node (ref "R13") (pin "P$1") (pinfunction "1_P$1") (pintype "passive"))
    )
    (net (code "102") (name "Net-(R14-2)") (class "Default")
      (node (ref "C14") (pin "1") (pinfunction "1_1") (pintype "passive"))
      (node (ref "IC8") (pin "3") (pinfunction "3_3") (pintype "input"))
      (node (ref "R14") (pin "P$2") (pinfunction "2_P$2") (pintype "passive"))
      (node (ref "R15") (pin "P$2") (pinfunction "2_P$2") (pintype "passive"))
    )
    (net (code "103") (name "Net-(R16-2)") (class "Default")
      (node (ref "C15") (pin "1") (pinfunction "1_1") (pintype "passive"))
      (node (ref "IC8") (pin "5") (pinfunction "5_5") (pintype "input"))
      (node (ref "R16") (pin "P$2") (pinfunction "2_P$2") (pintype "passive"))
      (node (ref "R17") (pin "P$2") (pinfunction "2_P$2") (pintype "passive"))
    )
    (net (code "104") (name "Net-(R18-2)") (class "Default")
      (node (ref "C16") (pin "1") (pinfunction "1_1") (pintype "passive"))
      (node (ref "IC8") (pin "10") (pinfunction "10_10") (pintype "input"))
      (node (ref "R18") (pin "P$2") (pinfunction "2_P$2") (pintype "passive"))
      (node (ref "R19") (pin "P$1") (pinfunction "1_P$1") (pintype "passive"))
    )
    (net (code "105") (name "Net-(R20-2)") (class "Default")
      (node (ref "C17") (pin "1") (pinfunction "1_1") (pintype "passive"))
      (node (ref "IC8") (pin "12") (pinfunction "12_12") (pintype "input"))
      (node (ref "R20") (pin "P$2") (pinfunction "2_P$2") (pintype "passive"))
      (node (ref "R21") (pin "P$2") (pinfunction "2_P$2") (pintype "passive"))
    )
    (net (code "106") (name "Net-(R22-1)") (class "Default")
      (node (ref "LED_IOREF") (pin "A") (pinfunction "A_A") (pintype "passive"))
      (node (ref "R22") (pin "P$1") (pinfunction "1_P$1") (pintype "passive"))
    )
    (net (code "107") (name "Net-(R29-1)") (class "Default")
      (node (ref "J4") (pin "4") (pinfunction "4_4") (pintype "passive"))
      (node (ref "R29") (pin "P$1") (pinfunction "1_P$1") (pintype "passive"))
    )
    (net (code "108") (name "Net-(R42-1)") (class "Default")
      (node (ref "LED1") (pin "A") (pinfunction "A_A") (pintype "passive"))
      (node (ref "R42") (pin "P$1") (pinfunction "1_P$1") (pintype "passive"))
    )
    (net (code "109") (name "Net-(R43-1)") (class "Default")
      (node (ref "LED2") (pin "A") (pinfunction "A_A") (pintype "passive"))
      (node (ref "R43") (pin "P$1") (pinfunction "1_P$1") (pintype "passive"))
    )
    (net (code "110") (name "Net-(R47-1)") (class "Default")
      (node (ref "LED3") (pin "A") (pinfunction "A_A") (pintype "passive"))
      (node (ref "R47") (pin "P$1") (pinfunction "1_P$1") (pintype "passive"))
    )
    (net (code "111") (name "PIN0_RX") (class "Default")
      (node (ref "IC12") (pin "20") (pinfunction "20_20") (pintype "bidirectional"))
      (node (ref "J9") (pin "0") (pinfunction "0(RX)_0") (pintype "bidirectional"))
    )
    (net (code "112") (name "PIN1_TX") (class "Default")
      (node (ref "IC12") (pin "18") (pinfunction "18_18") (pintype "bidirectional"))
      (node (ref "J9") (pin "1") (pinfunction "1(TX)_1") (pintype "bidirectional"))
    )
    (net (code "113") (name "PIN2") (class "Default")
      (node (ref "IC12") (pin "17") (pinfunction "17_17") (pintype "bidirectional"))
      (node (ref "J9") (pin "2") (pinfunction "2_2") (pintype "bidirectional"))
    )
    (net (code "114") (name "PIN3~{}") (class "Default")
      (node (ref "IC12") (pin "16") (pinfunction "16_16") (pintype "bidirectional"))
      (node (ref "J9") (pin "3") (pinfunction "3~{}_3") (pintype "bidirectional"))
    )
    (net (code "115") (name "PIN4") (class "Default")
      (node (ref "IC12") (pin "15") (pinfunction "15_15") (pintype "bidirectional"))
      (node (ref "J9") (pin "4") (pinfunction "4_4") (pintype "bidirectional"))
    )
    (net (code "116") (name "PIN5~{}") (class "Default")
      (node (ref "IC12") (pin "14") (pinfunction "14_14") (pintype "bidirectional"))
      (node (ref "J9") (pin "5") (pinfunction "5~{}_5") (pintype "bidirectional"))
    )
    (net (code "117") (name "PIN6~{}") (class "Default")
      (node (ref "IC12") (pin "13") (pinfunction "13_13") (pintype "bidirectional"))
      (node (ref "J9") (pin "6") (pinfunction "6~{}_6") (pintype "bidirectional"))
    )
    (net (code "118") (name "PIN7") (class "Default")
      (node (ref "IC12") (pin "12") (pinfunction "12_12") (pintype "bidirectional"))
      (node (ref "J9") (pin "7") (pinfunction "7_7") (pintype "bidirectional"))
    )
    (net (code "119") (name "PIN8") (class "Default")
      (node (ref "IC13") (pin "20") (pinfunction "20_20") (pintype "bidirectional"))
      (node (ref "J8") (pin "8") (pinfunction "8_8") (pintype "bidirectional"))
    )
    (net (code "120") (name "PIN9~{}") (class "Default")
      (node (ref "IC13") (pin "18") (pinfunction "18_18") (pintype "bidirectional"))
      (node (ref "J8") (pin "9") (pinfunction "9~{}_9") (pintype "bidirectional"))
    )
    (net (code "121") (name "PIN10~{}") (class "Default")
      (node (ref "IC13") (pin "17") (pinfunction "17_17") (pintype "bidirectional"))
      (node (ref "J8") (pin "10") (pinfunction "10~{}_10") (pintype "bidirectional"))
    )
    (net (code "122") (name "PIN11~{}") (class "Default")
      (node (ref "IC13") (pin "16") (pinfunction "16_16") (pintype "bidirectional"))
      (node (ref "J8") (pin "11") (pinfunction "11~{}_11") (pintype "bidirectional"))
    )
    (net (code "123") (name "PIN12") (class "Default")
      (node (ref "IC13") (pin "15") (pinfunction "15_15") (pintype "bidirectional"))
      (node (ref "J8") (pin "12") (pinfunction "12_12") (pintype "bidirectional"))
    )
    (net (code "124") (name "PIN13") (class "Default")
      (node (ref "IC13") (pin "14") (pinfunction "14_14") (pintype "bidirectional"))
      (node (ref "J8") (pin "13") (pinfunction "13_13") (pintype "bidirectional"))
    )
    (net (code "125") (name "RESET_N") (class "Default")
      (node (ref "IC6") (pin "74") (pinfunction "DIFFIO_RX_R2P/DIFFOUT_R2P_74") (pintype "bidirectional"))
      (node (ref "J10") (pin "RESET") (pinfunction "RESET_RESET") (pintype "bidirectional"))
      (node (ref "R32") (pin "P$2") (pinfunction "2_P$2") (pintype "passive"))
      (node (ref "SW1") (pin "1") (pinfunction "1_1") (pintype "bidirectional"))
      (node (ref "SW1") (pin "2") (pinfunction "2_2") (pintype "bidirectional"))
    )
    (net (code "126") (name "SCL") (class "Default")
      (node (ref "IC13") (pin "12") (pinfunction "12_12") (pintype "bidirectional"))
      (node (ref "J8") (pin "SCL") (pinfunction "SCL_SCL") (pintype "bidirectional"))
    )
    (net (code "127") (name "SDA") (class "Default")
      (node (ref "IC13") (pin "13") (pinfunction "13_13") (pintype "bidirectional"))
      (node (ref "J8") (pin "SDA") (pinfunction "SDA_SDA") (pintype "bidirectional"))
    )
    (net (code "128") (name "SRAM_CS_N") (class "Default")
      (node (ref "IC10") (pin "1") (pinfunction "CS_N_1") (pintype "input"))
      (node (ref "IC6") (pin "29") (pinfunction "CLK1P/DIFFIO_RX_L20P/DIFFOUT_L20P_29") (pintype "bidirectional"))
    )
    (net (code "129") (name "SRAM_SCK") (class "Default")
      (node (ref "IC10") (pin "6") (pinfunction "SCK_6") (pintype "input"))
      (node (ref "IC6") (pin "27") (pinfunction "CLK0P/DIFFIO_RX_L18P/DIFFOUT_L18P_27") (pintype "bidirectional"))
    )
    (net (code "130") (name "SRAM_SIO0") (class "Default")
      (node (ref "IC10") (pin "5") (pinfunction "SI/SIO0_5") (pintype "bidirectional"))
      (node (ref "IC6") (pin "28") (pinfunction "CLK1N/DIFFIO_RX_L20N/DIFFOUT_L20N_28") (pintype "bidirectional"))
    )
    (net (code "131") (name "SRAM_SIO1") (class "Default")
      (node (ref "IC10") (pin "2") (pinfunction "SO/SIO1_2") (pintype "bidirectional"))
      (node (ref "IC6") (pin "32") (pinfunction "PLL_L_CLKOUTN/DIFFIO_RX_L27N/DIFFOUT_L27N_32") (pintype "bidirectional"))
    )
    (net (code "132") (name "SRAM_SIO2") (class "Default")
      (node (ref "IC10") (pin "3") (pinfunction "NC/SIO2_3") (pintype "bidirectional"))
      (node (ref "IC6") (pin "33") (pinfunction "PLL_L_CLKOUTP/DIFFIO_RX_L27P/DIFFOUT_L27P_33") (pintype "bidirectional"))
    )
    (net (code "133") (name "SRAM_SIO3") (class "Default")
      (node (ref "IC10") (pin "7") (pinfunction "HOLD_N/SIO3_7") (pintype "bidirectional"))
      (node (ref "IC6") (pin "26") (pinfunction "CLK0N/DIFFIO_RX_L18N/DIFFOUT_L18N_26") (pintype "bidirectional"))
    )
    (net (code "134") (name "TCK") (class "Default")
      (node (ref "IC6") (pin "18") (pinfunction "TCK/DIFFIO_RX_L11P/DIFFOUT_L11P_18") (pintype "bidirectional"))
      (node (ref "J7") (pin "1") (pinfunction "1_1") (pintype "passive"))
      (node (ref "R39") (pin "P$2") (pinfunction "2_P$2") (pintype "passive"))
    )
    (net (code "135") (name "TDI") (class "Default")
      (node (ref "IC6") (pin "19") (pinfunction "TDI/DIFFIO_RX_L12N/DIFFOUT_L12N_19") (pintype "bidirectional"))
      (node (ref "J7") (pin "9") (pinfunction "9_9") (pintype "passive"))
      (node (ref "R34") (pin "P$1") (pinfunction "1_P$1") (pintype "passive"))
    )
    (net (code "136") (name "TDO") (class "Default")
      (node (ref "IC6") (pin "20") (pinfunction "TDO/DIFFIO_RX_L12P/DIFFOUT_L12P_20") (pintype "bidirectional"))
      (node (ref "J7") (pin "3") (pinfunction "3_3") (pintype "passive"))
    )
    (net (code "137") (name "TMS") (class "Default")
      (node (ref "IC6") (pin "16") (pinfunction "TMS/DIFFIO_RX_L11N/DIFFOUT_L11N_16") (pintype "bidirectional"))
      (node (ref "J7") (pin "5") (pinfunction "5_5") (pintype "passive"))
      (node (ref "R35") (pin "P$1") (pinfunction "1_P$1") (pintype "passive"))
    )
    (net (code "138") (name "USBVCC") (class "Default")
      (node (ref "C10") (pin "1") (pinfunction "1_1") (pintype "passive"))
      (node (ref "C9") (pin "+") (pinfunction "+_+") (pintype "passive"))
      (node (ref "F1") (pin "2") (pinfunction "2_2") (pintype "passive"))
      (node (ref "IC5") (pin "20") (pinfunction "VCC_20") (pintype "power_in"))
      (node (ref "PMOS1") (pin "1") (pinfunction "D1_1") (pintype "passive"))
      (node (ref "PMOS1") (pin "2") (pinfunction "D2_2") (pintype "passive"))
      (node (ref "PMOS1") (pin "5") (pinfunction "D3_5") (pintype "passive"))
      (node (ref "PMOS1") (pin "6") (pinfunction "D4_6") (pintype "passive"))
    )
    (net (code "139") (name "VIN") (class "Default")
      (node (ref "C1") (pin "+") (pinfunction "+_+") (pintype "passive"))
      (node (ref "D1") (pin "1") (pinfunction "1_1") (pintype "passive"))
      (node (ref "IC1") (pin "3") (pinfunction "3_3") (pintype "input"))
      (node (ref "J10") (pin "VIN") (pinfunction "VIN_VIN") (pintype "bidirectional"))
      (node (ref "R7") (pin "P$2") (pinfunction "2_P$2") (pintype "passive"))
    )
    (net (code "140") (name "unconnected-(IC3-HDST-Pad3)") (class "Default")
      (node (ref "IC3") (pin "3") (pinfunction "HDST_3") (pintype "output"))
    )
    (net (code "141") (name "unconnected-(IC3-LINEI-Pad11)") (class "Default")
      (node (ref "IC3") (pin "11") (pinfunction "LINEI_11") (pintype "input"))
    )
    (net (code "142") (name "unconnected-(IC3-LINEO-Pad15)") (class "Default")
      (node (ref "IC3") (pin "15") (pinfunction "LINEO_15") (pintype "output"))
    )
    (net (code "143") (name "unconnected-(IC5-CBUS2-Pad13)") (class "Default")
      (node (ref "IC5") (pin "13") (pinfunction "CBUS2_13") (pintype "bidirectional"))
    )
    (net (code "144") (name "unconnected-(IC5-CBUS3-Pad14)") (class "Default")
      (node (ref "IC5") (pin "14") (pinfunction "CBUS3_14") (pintype "bidirectional"))
    )
    (net (code "145") (name "unconnected-(IC5-CBUS4-Pad12)") (class "Default")
      (node (ref "IC5") (pin "12") (pinfunction "CBUS4_12") (pintype "bidirectional"))
    )
    (net (code "146") (name "unconnected-(IC5-OSCI-Pad27)") (class "Default")
      (node (ref "IC5") (pin "27") (pinfunction "OSCI_27") (pintype "input"))
    )
    (net (code "147") (name "unconnected-(IC5-OSCO-Pad28)") (class "Default")
      (node (ref "IC5") (pin "28") (pinfunction "OSCO_28") (pintype "output"))
    )
    (net (code "148") (name "unconnected-(IC5-~{DCD}-Pad10)") (class "Default")
      (node (ref "IC5") (pin "10") (pinfunction "~{DCD}_10") (pintype "input"))
    )
    (net (code "149") (name "unconnected-(IC5-~{DSR}-Pad9)") (class "Default")
      (node (ref "IC5") (pin "9") (pinfunction "~{DSR}_9") (pintype "input"))
    )
    (net (code "150") (name "unconnected-(IC5-~{DTR}-Pad2)") (class "Default")
      (node (ref "IC5") (pin "2") (pinfunction "~{DTR}_2") (pintype "output"))
    )
    (net (code "151") (name "unconnected-(IC5-~{RI}-Pad6)") (class "Default")
      (node (ref "IC5") (pin "6") (pinfunction "~{RI}_6") (pintype "input"))
    )
    (net (code "152") (name "unconnected-(IC6C-DIFFIO_RX_L14N{slash}DIFFOUT_L14N-Pad21)") (class "Default")
      (node (ref "IC6") (pin "21") (pinfunction "DIFFIO_RX_L14N/DIFFOUT_L14N_21") (pintype "bidirectional"))
    )
    (net (code "153") (name "unconnected-(IC6C-DIFFIO_RX_L14P{slash}DIFFOUT_L14P-Pad22)") (class "Default")
      (node (ref "IC6") (pin "22") (pinfunction "DIFFIO_RX_L14P/DIFFOUT_L14P_22") (pintype "bidirectional"))
    )
    (net (code "154") (name "unconnected-(IC6C-DIFFIO_RX_L16N{slash}DIFFOUT_L16N-Pad24)") (class "Default")
      (node (ref "IC6") (pin "24") (pinfunction "DIFFIO_RX_L16N/DIFFOUT_L16N_24") (pintype "bidirectional"))
    )
    (net (code "155") (name "unconnected-(IC6C-DIFFIO_RX_L16P{slash}DIFFOUT_L16P-Pad25)") (class "Default")
      (node (ref "IC6") (pin "25") (pinfunction "DIFFIO_RX_L16P/DIFFOUT_L16P_25") (pintype "bidirectional"))
    )
    (net (code "156") (name "unconnected-(IC6C-VREFB1N0-Pad17)") (class "Default")
      (node (ref "IC6") (pin "17") (pinfunction "VREFB1N0_17") (pintype "input"))
    )
    (net (code "157") (name "unconnected-(IC6D-VREFB2N0-Pad30)") (class "Default")
      (node (ref "IC6") (pin "30") (pinfunction "VREFB2N0_30") (pintype "input"))
    )
    (net (code "158") (name "unconnected-(IC6E-VREFB3N0-Pad48)") (class "Default")
      (node (ref "IC6") (pin "48") (pinfunction "VREFB3N0_48") (pintype "input"))
    )
    (net (code "159") (name "unconnected-(IC6F-VREFB4N0-Pad61)") (class "Default")
      (node (ref "IC6") (pin "61") (pinfunction "VREFB4N0_61") (pintype "input"))
    )
    (net (code "160") (name "unconnected-(IC6G-DIFFIO_RX_R1N{slash}DIFFOUT_R1N-Pad77)") (class "Default")
      (node (ref "IC6") (pin "77") (pinfunction "DIFFIO_RX_R1N/DIFFOUT_R1N_77") (pintype "bidirectional"))
    )
    (net (code "161") (name "unconnected-(IC6G-DIFFIO_RX_R10N{slash}DIFFOUT_R10N-Pad87)") (class "Default")
      (node (ref "IC6") (pin "87") (pinfunction "DIFFIO_RX_R10N/DIFFOUT_R10N_87") (pintype "bidirectional"))
    )
    (net (code "162") (name "unconnected-(IC6G-DIFFIO_RX_R11N{slash}DIFFOUT_R11N-Pad86)") (class "Default")
      (node (ref "IC6") (pin "86") (pinfunction "DIFFIO_RX_R11N/DIFFOUT_R11N_86") (pintype "bidirectional"))
    )
    (net (code "163") (name "unconnected-(IC6G-IO78-Pad78)") (class "Default")
      (node (ref "IC6") (pin "78") (pinfunction "IO78_78") (pintype "bidirectional"))
    )
    (net (code "164") (name "unconnected-(IC6G-VREFB5N0-Pad80)") (class "Default")
      (node (ref "IC6") (pin "80") (pinfunction "VREFB5N0_80") (pintype "input"))
    )
    (net (code "165") (name "unconnected-(IC6H-CLK2N{slash}DIFFIO_RX_R14N{slash}DIFFOUT_R14N-Pad89)") (class "Default")
      (node (ref "IC6") (pin "89") (pinfunction "CLK2N/DIFFIO_RX_R14N/DIFFOUT_R14N_89") (pintype "bidirectional"))
    )
    (net (code "166") (name "unconnected-(IC6H-CLK3N{slash}DIFFIO_RX_R16N{slash}DIFFOUT_R16N-Pad91)") (class "Default")
      (node (ref "IC6") (pin "91") (pinfunction "CLK3N/DIFFIO_RX_R16N/DIFFOUT_R16N_91") (pintype "bidirectional"))
    )
    (net (code "167") (name "unconnected-(IC6H-CLK3P{slash}DIFFIO_RX_R16P{slash}DIFFOUT_R16P-Pad90)") (class "Default")
      (node (ref "IC6") (pin "90") (pinfunction "CLK3P/DIFFIO_RX_R16P/DIFFOUT_R16P_90") (pintype "bidirectional"))
    )
    (net (code "168") (name "unconnected-(IC6H-DIFFIO_RX_R33N{slash}DIFFOUT_R33N-Pad106)") (class "Default")
      (node (ref "IC6") (pin "106") (pinfunction "DIFFIO_RX_R33N/DIFFOUT_R33N_106") (pintype "bidirectional"))
    )
    (net (code "169") (name "unconnected-(IC6H-DIFFIO_RX_R33P{slash}DIFFOUT_R33P-Pad105)") (class "Default")
      (node (ref "IC6") (pin "105") (pinfunction "DIFFIO_RX_R33P/DIFFOUT_R33P_105") (pintype "bidirectional"))
    )
    (net (code "170") (name "unconnected-(IC6H-VREFB6N0-Pad97)") (class "Default")
      (node (ref "IC6") (pin "97") (pinfunction "VREFB6N0_97") (pintype "input"))
    )
    (net (code "171") (name "unconnected-(IC6I-DIFFIO_RX_T1N{slash}DIFFOUT_T1N-Pad111)") (class "Default")
      (node (ref "IC6") (pin "111") (pinfunction "DIFFIO_RX_T1N/DIFFOUT_T1N_111") (pintype "bidirectional"))
    )
    (net (code "172") (name "unconnected-(IC6I-DIFFIO_RX_T1P{slash}DIFFOUT_T1P-Pad110)") (class "Default")
      (node (ref "IC6") (pin "110") (pinfunction "DIFFIO_RX_T1P/DIFFOUT_T1P_110") (pintype "bidirectional"))
    )
    (net (code "173") (name "unconnected-(IC6I-DIFFIO_RX_T10N{slash}DIFFOUT_T10N-Pad119)") (class "Default")
      (node (ref "IC6") (pin "119") (pinfunction "DIFFIO_RX_T10N/DIFFOUT_T10N_119") (pintype "bidirectional"))
    )
    (net (code "174") (name "unconnected-(IC6I-DIFFIO_RX_T10P{slash}DIFFOUT_T10P-Pad118)") (class "Default")
      (node (ref "IC6") (pin "118") (pinfunction "DIFFIO_RX_T10P/DIFFOUT_T10P_118") (pintype "bidirectional"))
    )
    (net (code "175") (name "unconnected-(IC6I-IO113-Pad113)") (class "Default")
      (node (ref "IC6") (pin "113") (pinfunction "IO113_113") (pintype "bidirectional"))
    )
    (net (code "176") (name "unconnected-(IC6I-IO114-Pad114)") (class "Default")
      (node (ref "IC6") (pin "114") (pinfunction "IO114_114") (pintype "bidirectional"))
    )
    (net (code "177") (name "unconnected-(IC6I-VREFB7N0-Pad112)") (class "Default")
      (node (ref "IC6") (pin "112") (pinfunction "VREFB7N0_112") (pintype "input"))
    )
    (net (code "178") (name "unconnected-(IC6J-CRC_ERROR{slash}DIFFIO_RX_T22N{slash}DIFFOUT_T22N-Pad134)") (class "Default")
      (node (ref "IC6") (pin "134") (pinfunction "CRC_ERROR/DIFFIO_RX_T22N/DIFFOUT_T22N_134") (pintype "bidirectional"))
    )
    (net (code "179") (name "unconnected-(IC6J-DEV_OE-Pad122)") (class "Default")
      (node (ref "IC6") (pin "122") (pinfunction "DEV_OE_122") (pintype "bidirectional"))
    )
    (net (code "180") (name "unconnected-(IC6J-DIFFIO_RX_T16P{slash}DIFFOUT_T16P-Pad120)") (class "Default")
      (node (ref "IC6") (pin "120") (pinfunction "DIFFIO_RX_T16P/DIFFOUT_T16P_120") (pintype "bidirectional"))
    )
    (net (code "181") (name "unconnected-(IC6J-DIFFIO_RX_T19N{slash}DIFFOUT_T19N-Pad127)") (class "Default")
      (node (ref "IC6") (pin "127") (pinfunction "DIFFIO_RX_T19N/DIFFOUT_T19N_127") (pintype "bidirectional"))
    )
    (net (code "182") (name "unconnected-(IC6J-DIFFIO_RX_T19P{slash}DIFFOUT_T19P-Pad124)") (class "Default")
      (node (ref "IC6") (pin "124") (pinfunction "DIFFIO_RX_T19P/DIFFOUT_T19P_124") (pintype "bidirectional"))
    )
    (net (code "183") (name "unconnected-(IC6J-DIFFIO_RX_T26N{slash}DIFFOUT_T26N-Pad141)") (class "Default")
      (node (ref "IC6") (pin "141") (pinfunction "DIFFIO_RX_T26N/DIFFOUT_T26N_141") (pintype "bidirectional"))
    )
    (net (code "184") (name "unconnected-(IC6J-DIFFIO_RX_T26P{slash}DIFFOUT_T26P-Pad140)") (class "Default")
      (node (ref "IC6") (pin "140") (pinfunction "DIFFIO_RX_T26P/DIFFOUT_T26P_140") (pintype "bidirectional"))
    )
    (net (code "185") (name "unconnected-(IC6J-IO135-Pad135)") (class "Default")
      (node (ref "IC6") (pin "135") (pinfunction "IO135_135") (pintype "bidirectional"))
    )
    (net (code "186") (name "unconnected-(IC6J-VREFB8N0-Pad123)") (class "Default")
      (node (ref "IC6") (pin "123") (pinfunction "VREFB8N0_123") (pintype "input"))
    )
    (net (code "187") (name "unconnected-(J10-NC-PadN{slash}C)") (class "Default")
      (node (ref "J10") (pin "N/C") (pinfunction "NC_N/C") (pintype "bidirectional"))
    )
  )
)
